# SCH_Scope_1014D_2022-05-10.net
KiCad netlist of a schematic drawn in EasyEDA
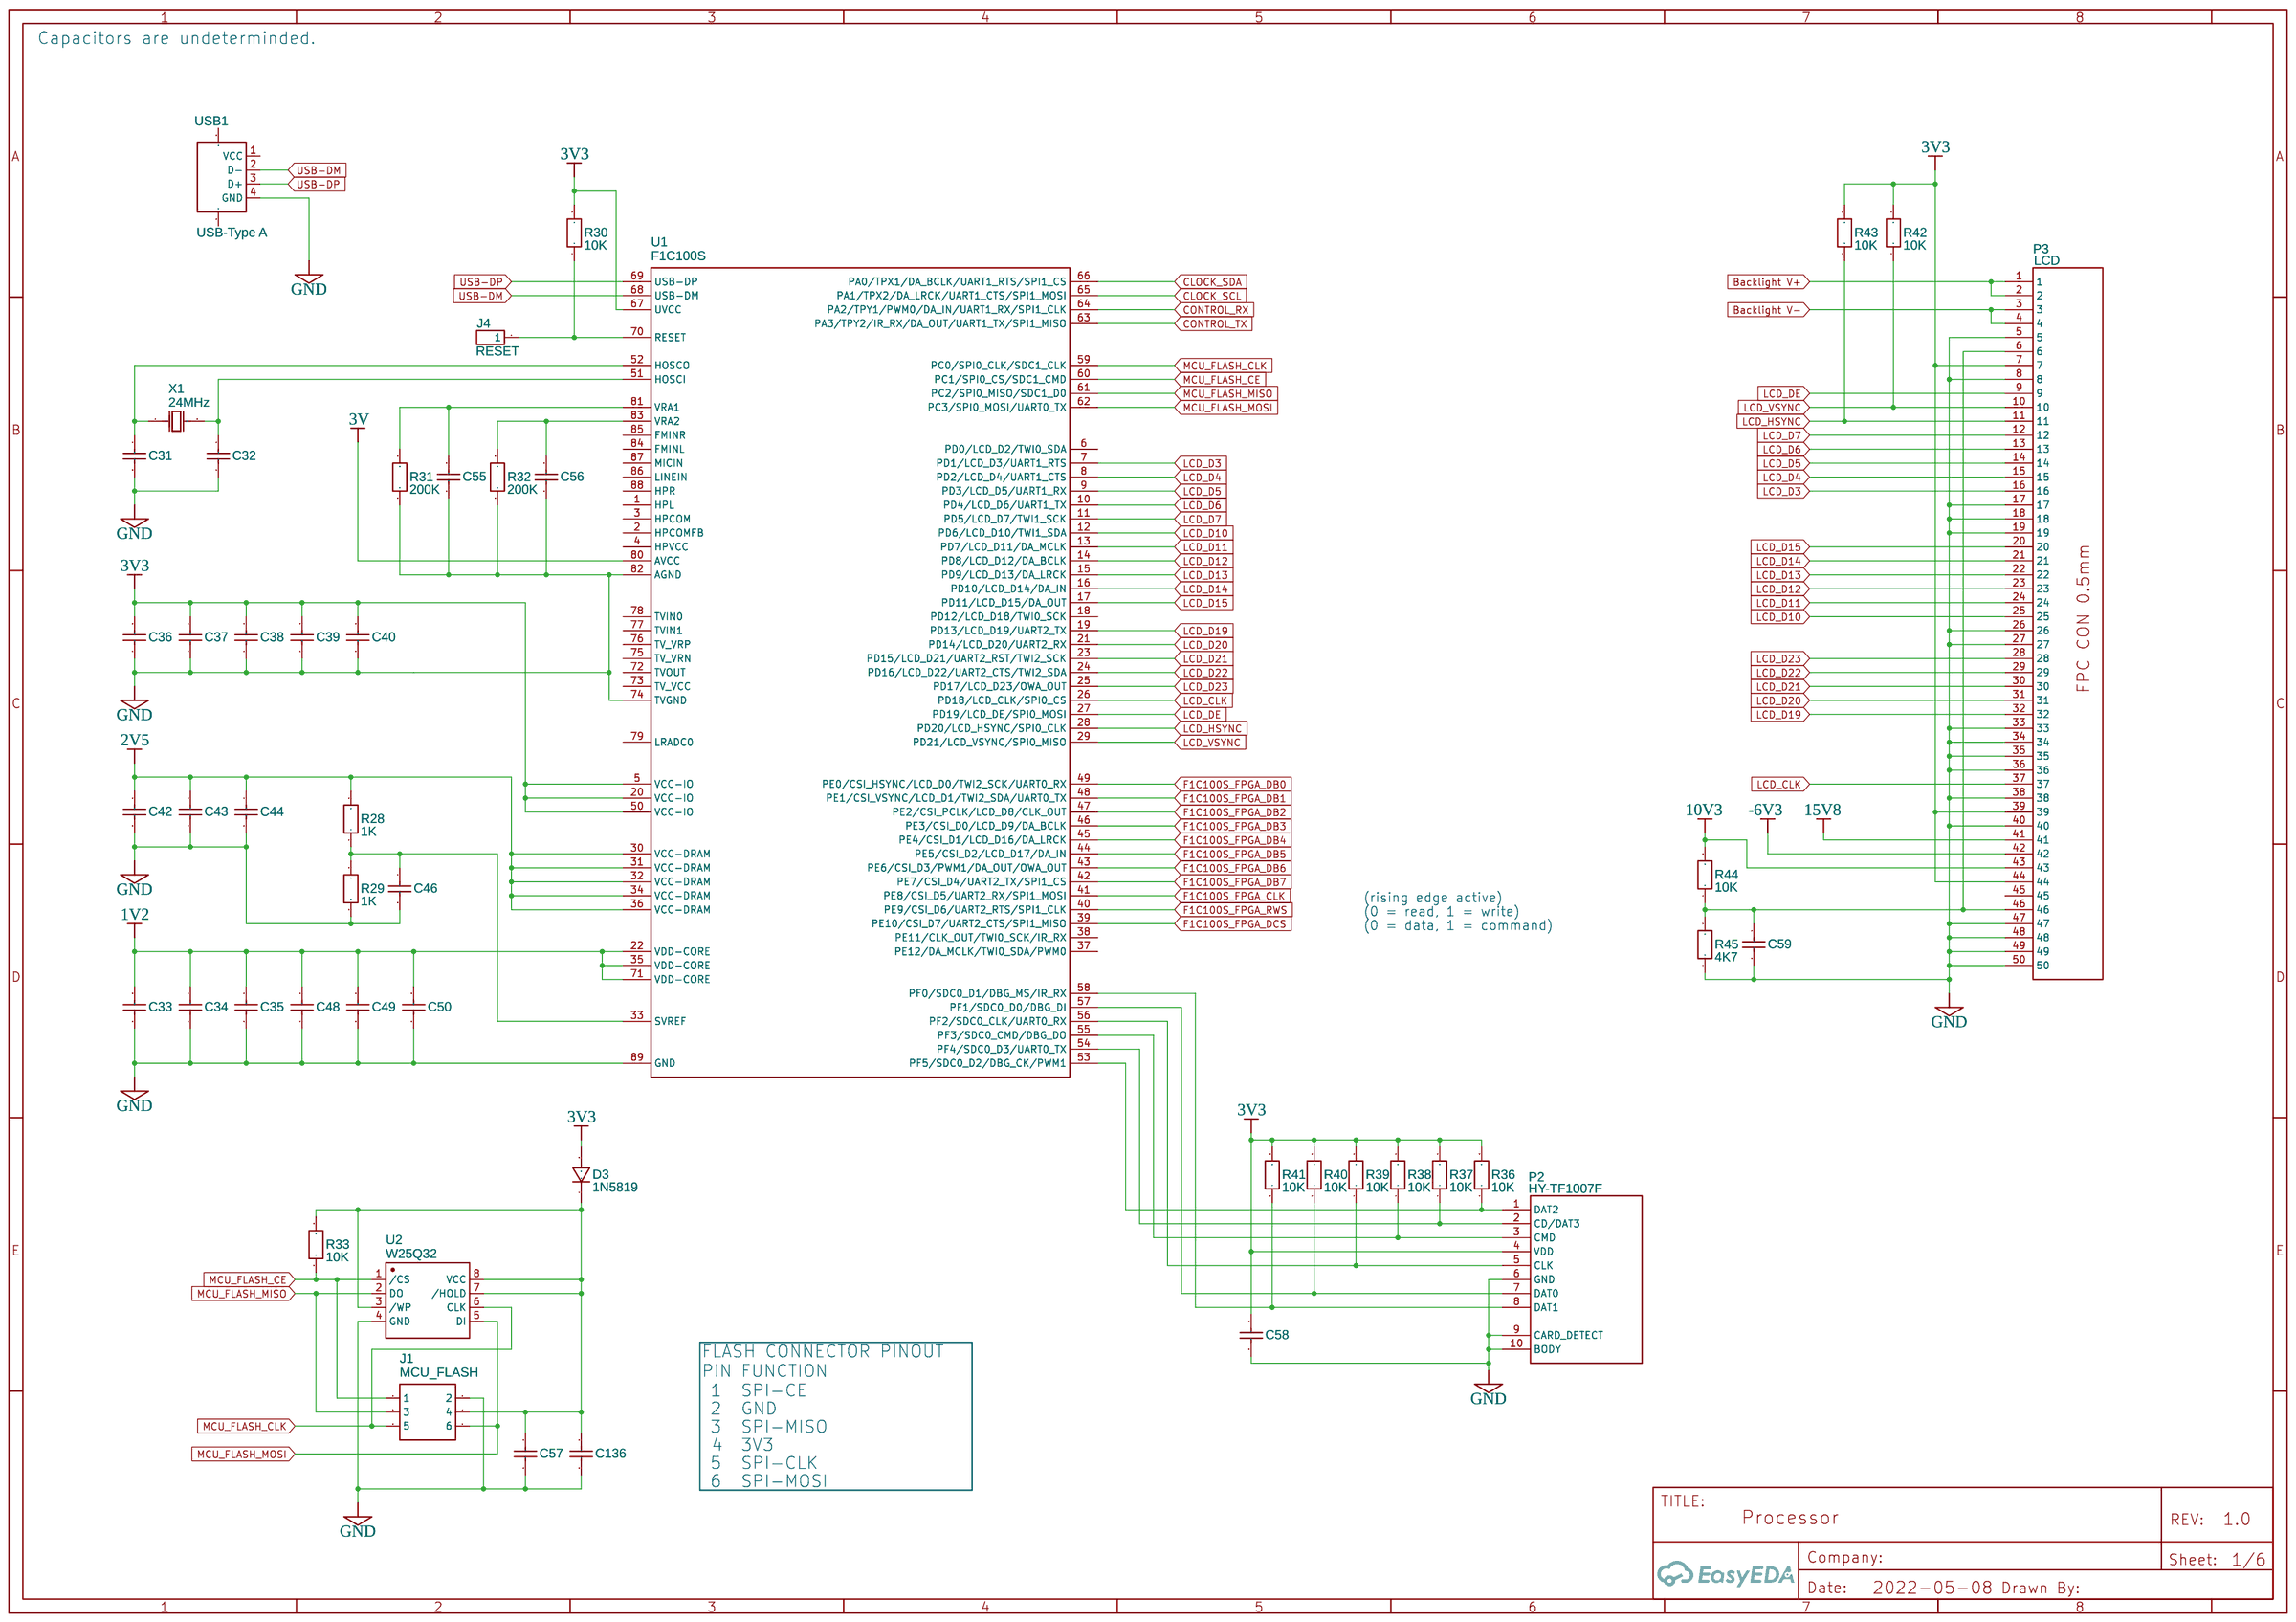
[diagram p0: Scope_1014D_Processor]
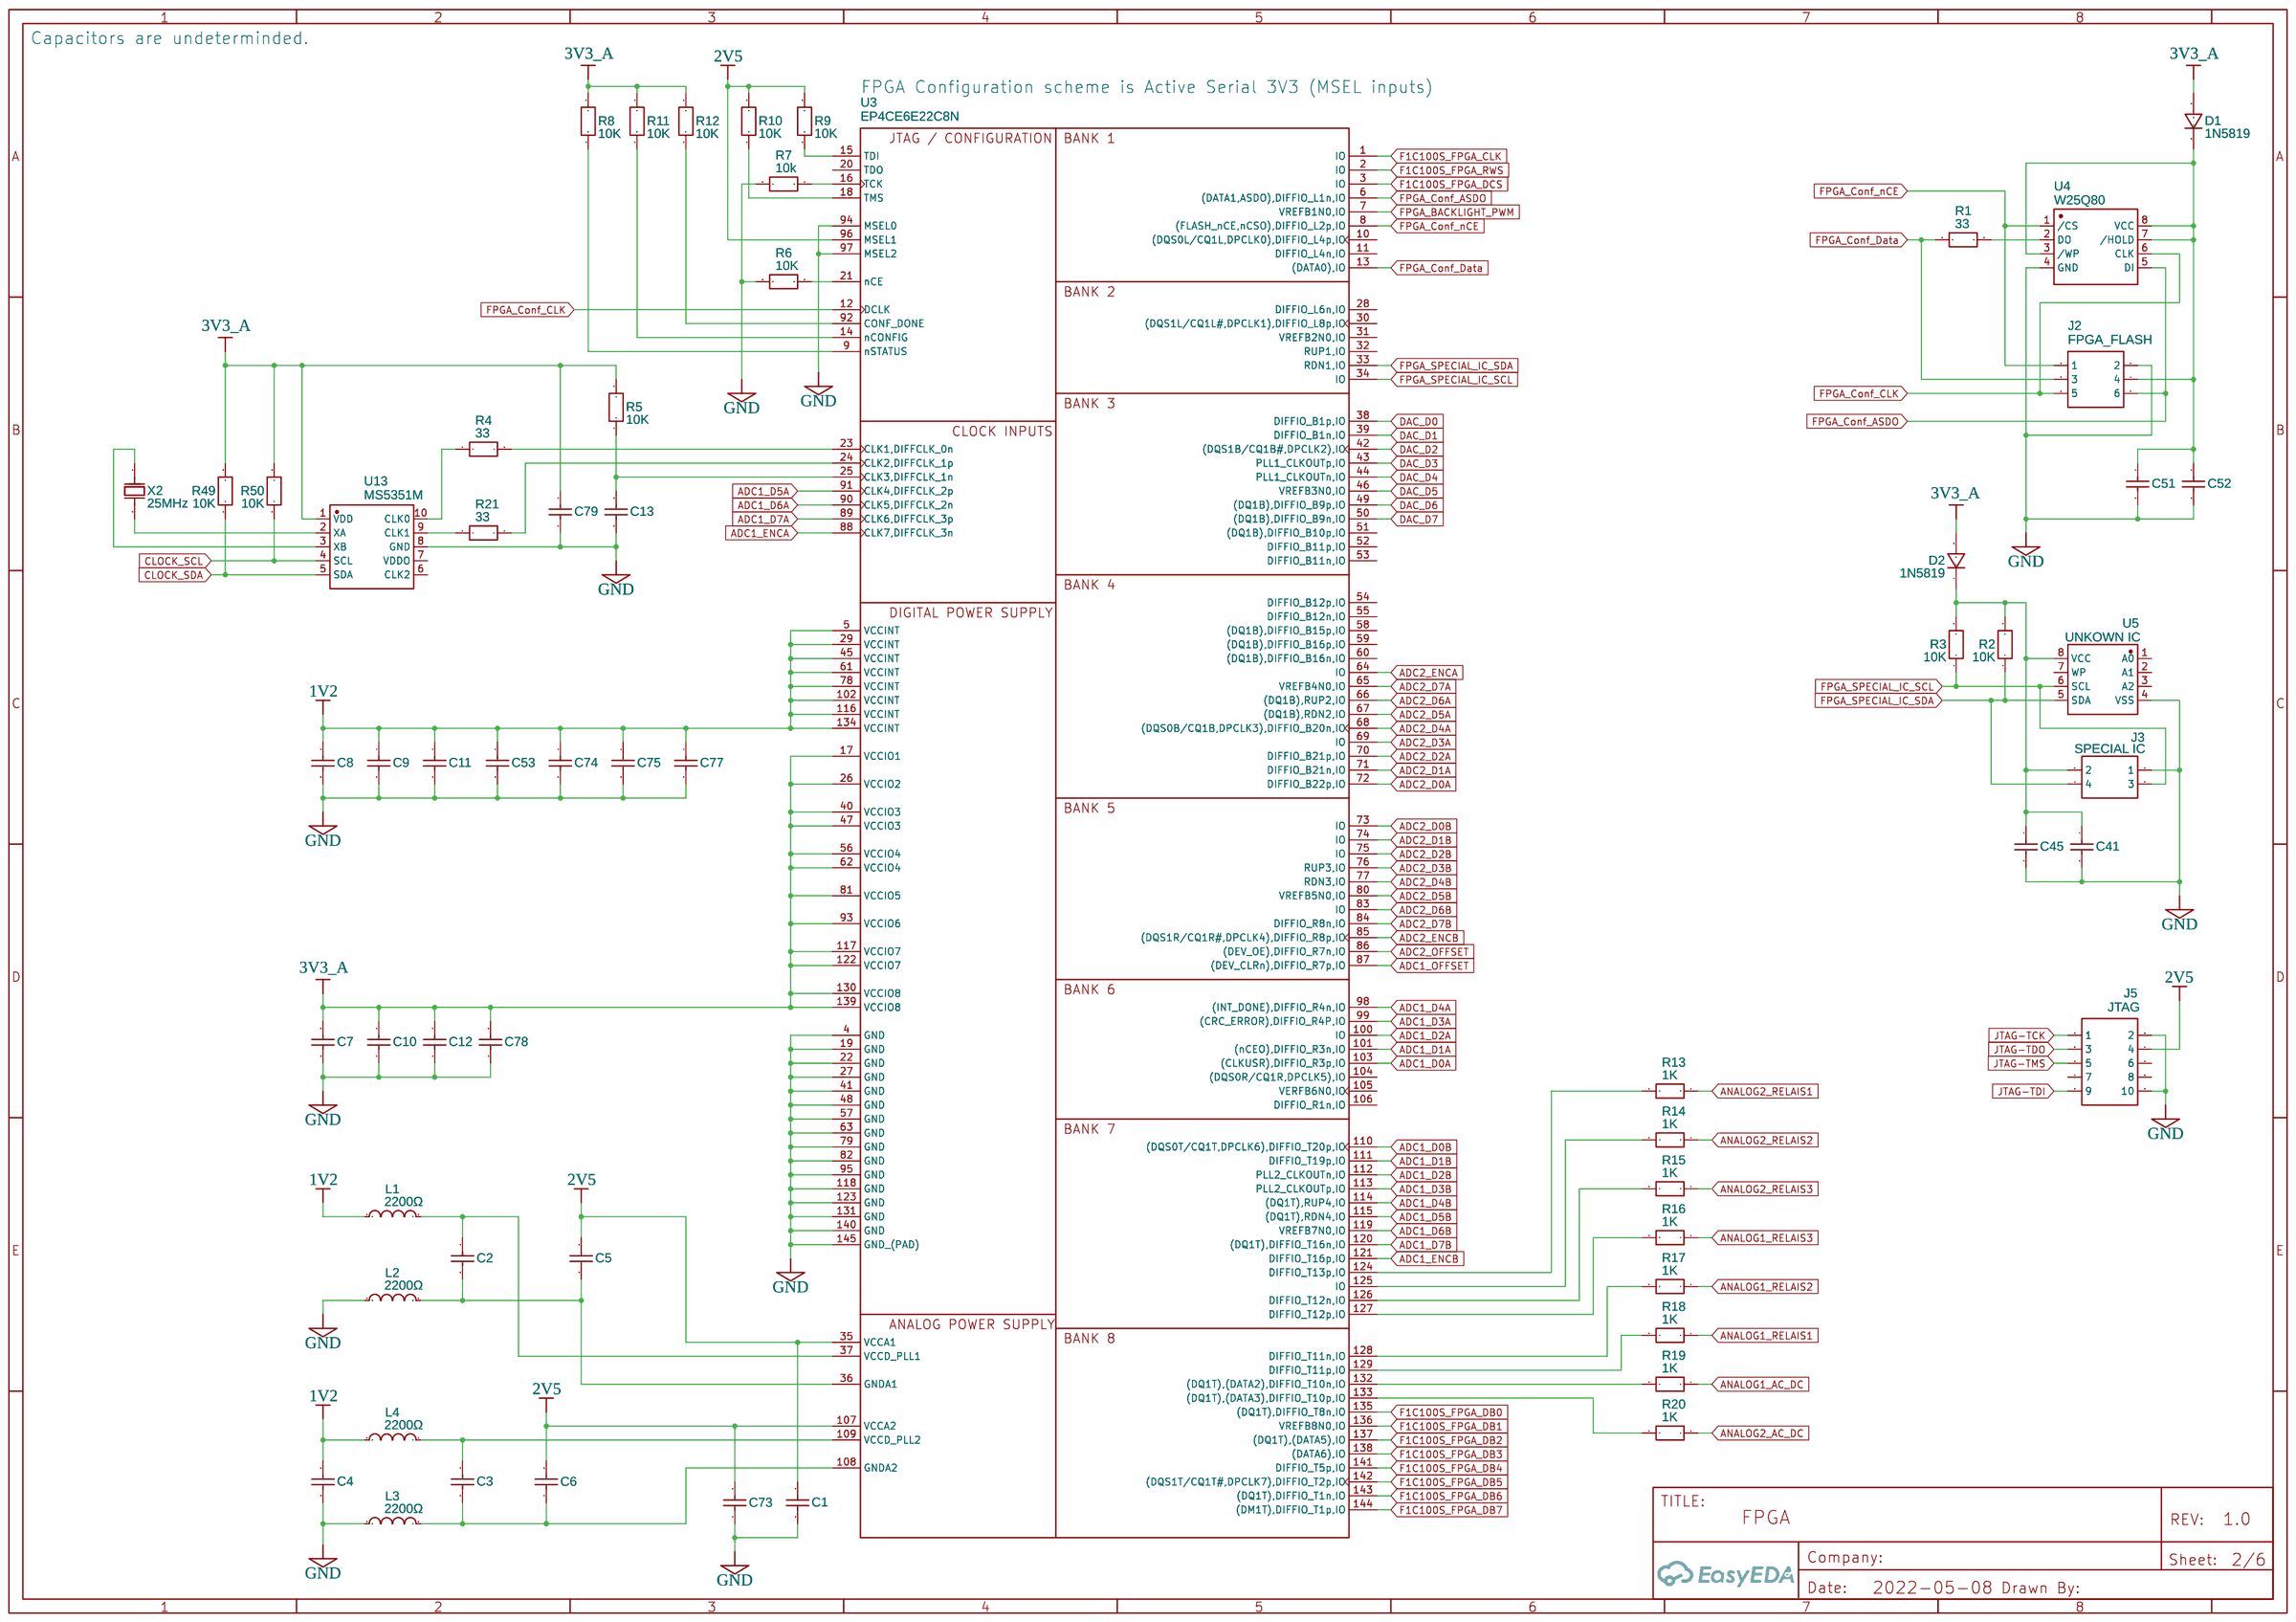
[diagram p1: Scope_1014D_Data_Acquisition]
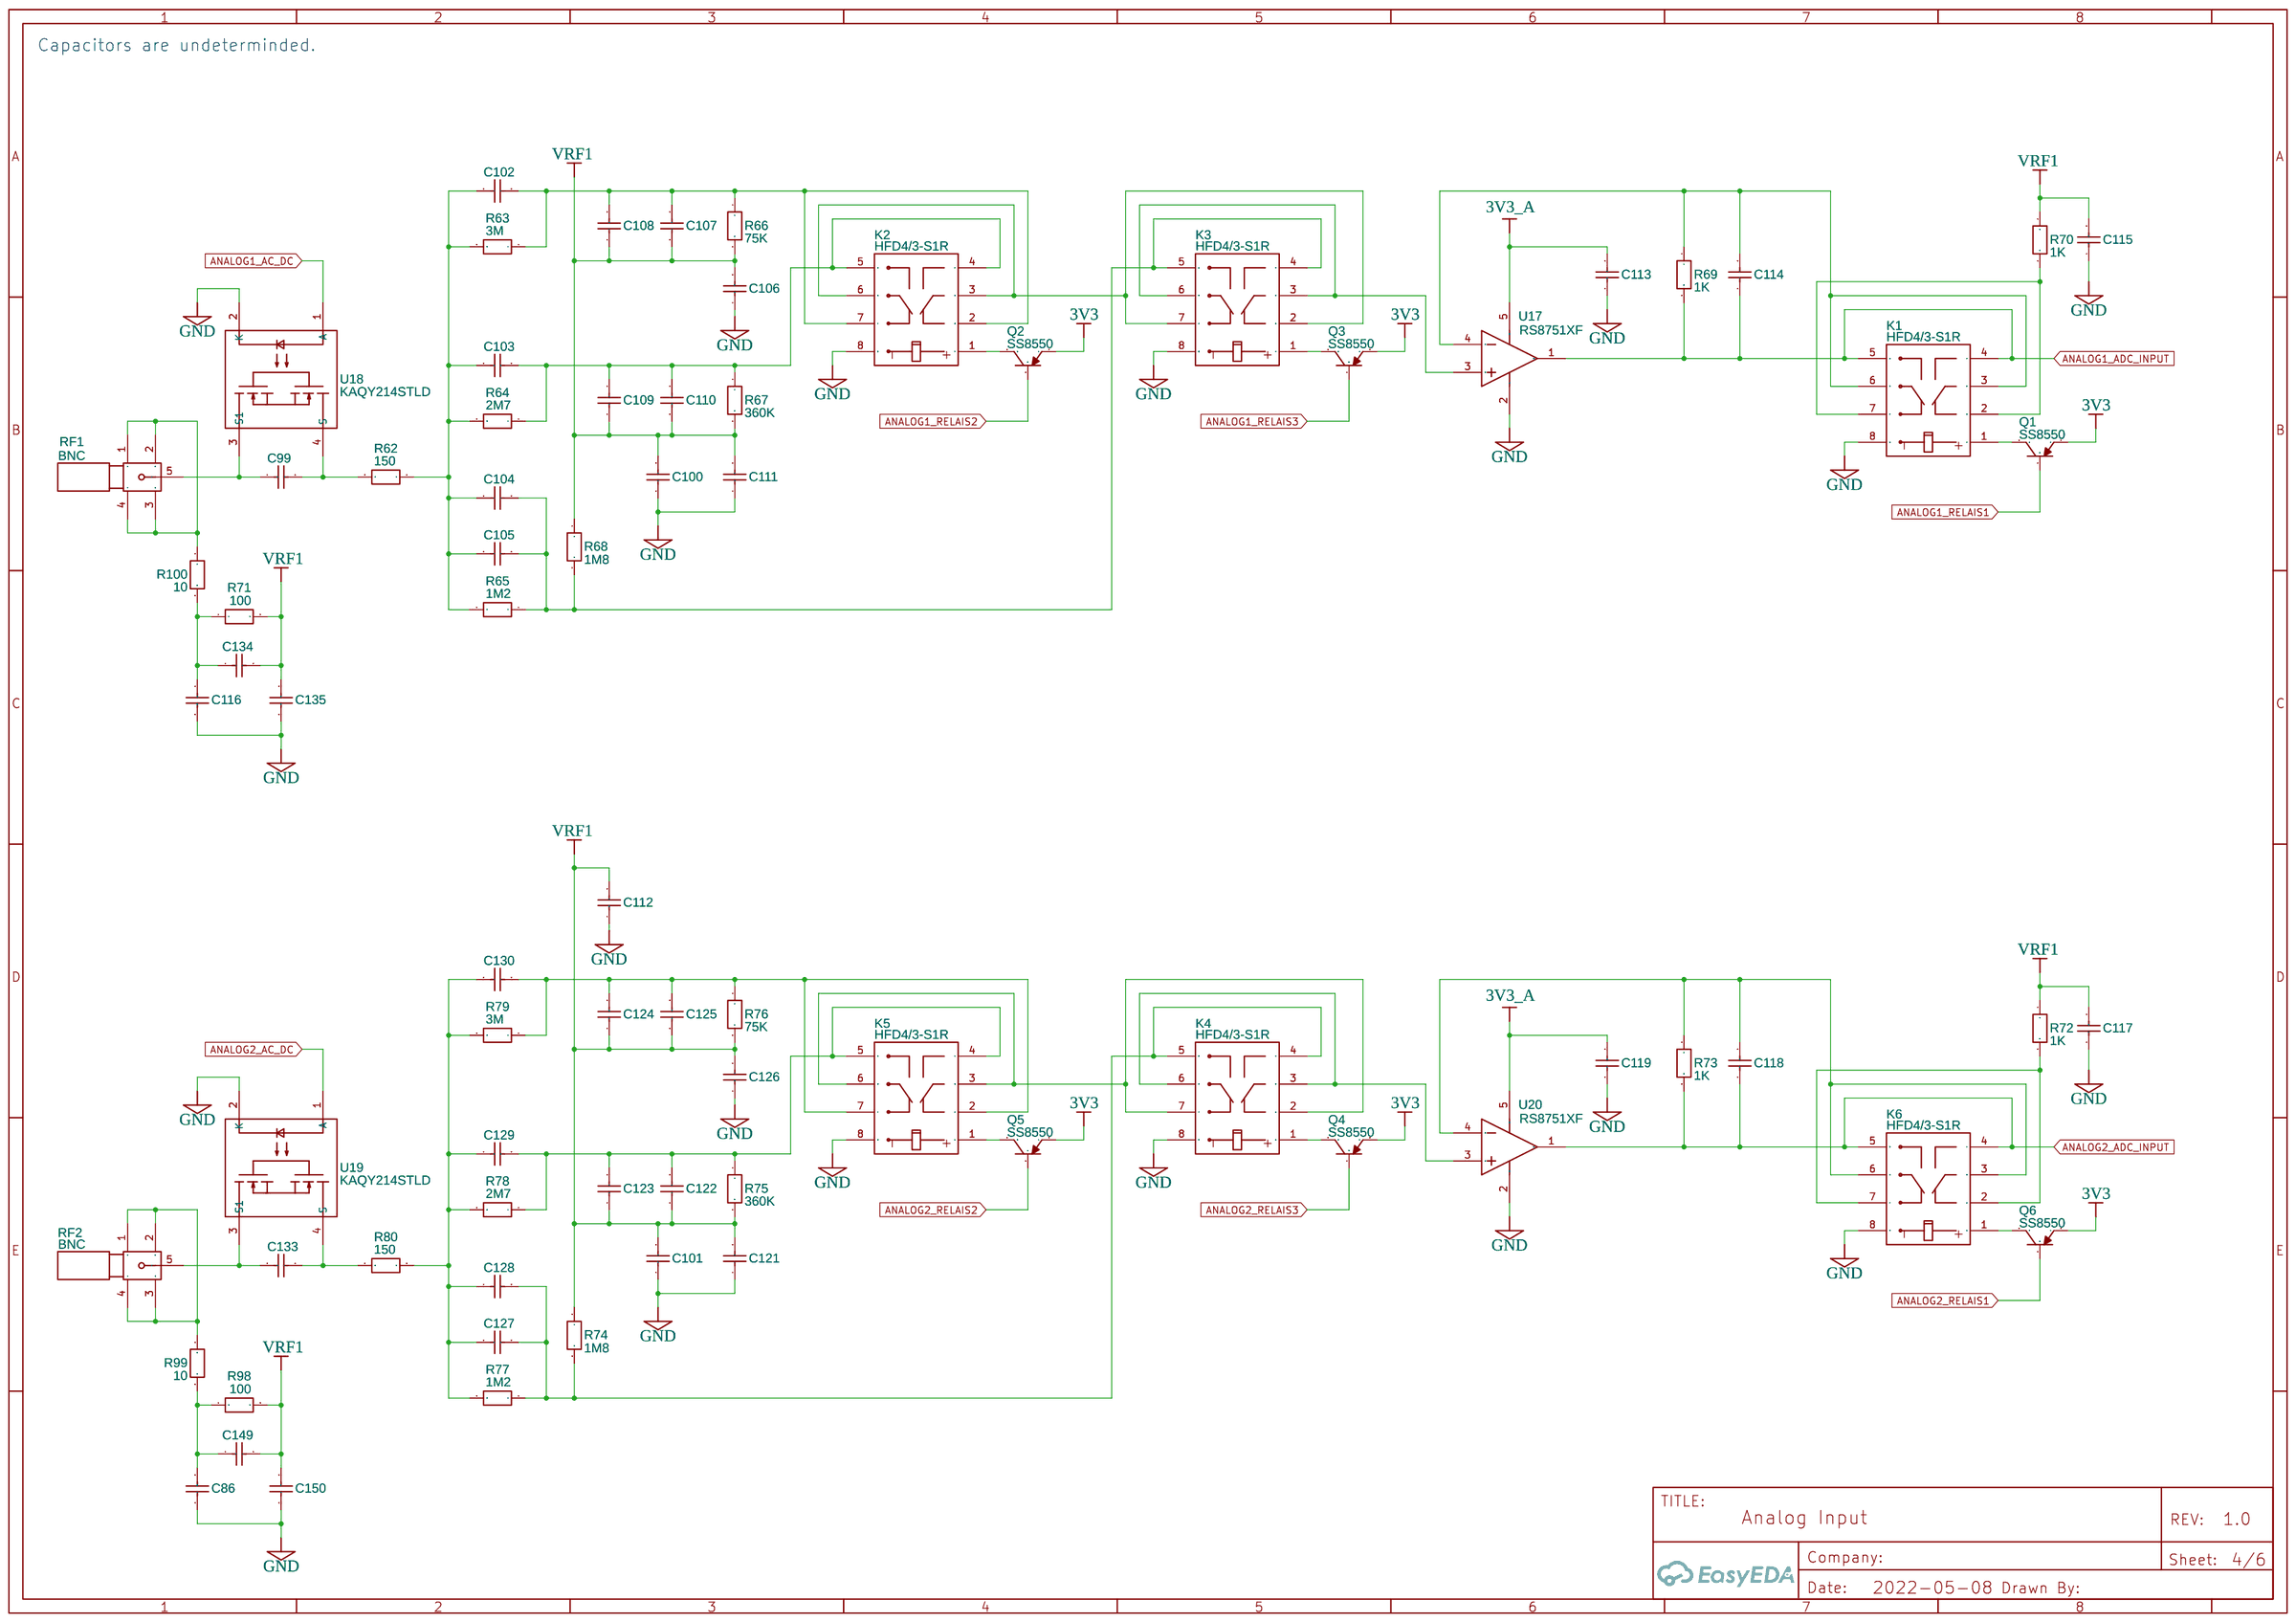
[diagram p2: Scope_1014D_Analog_Input]
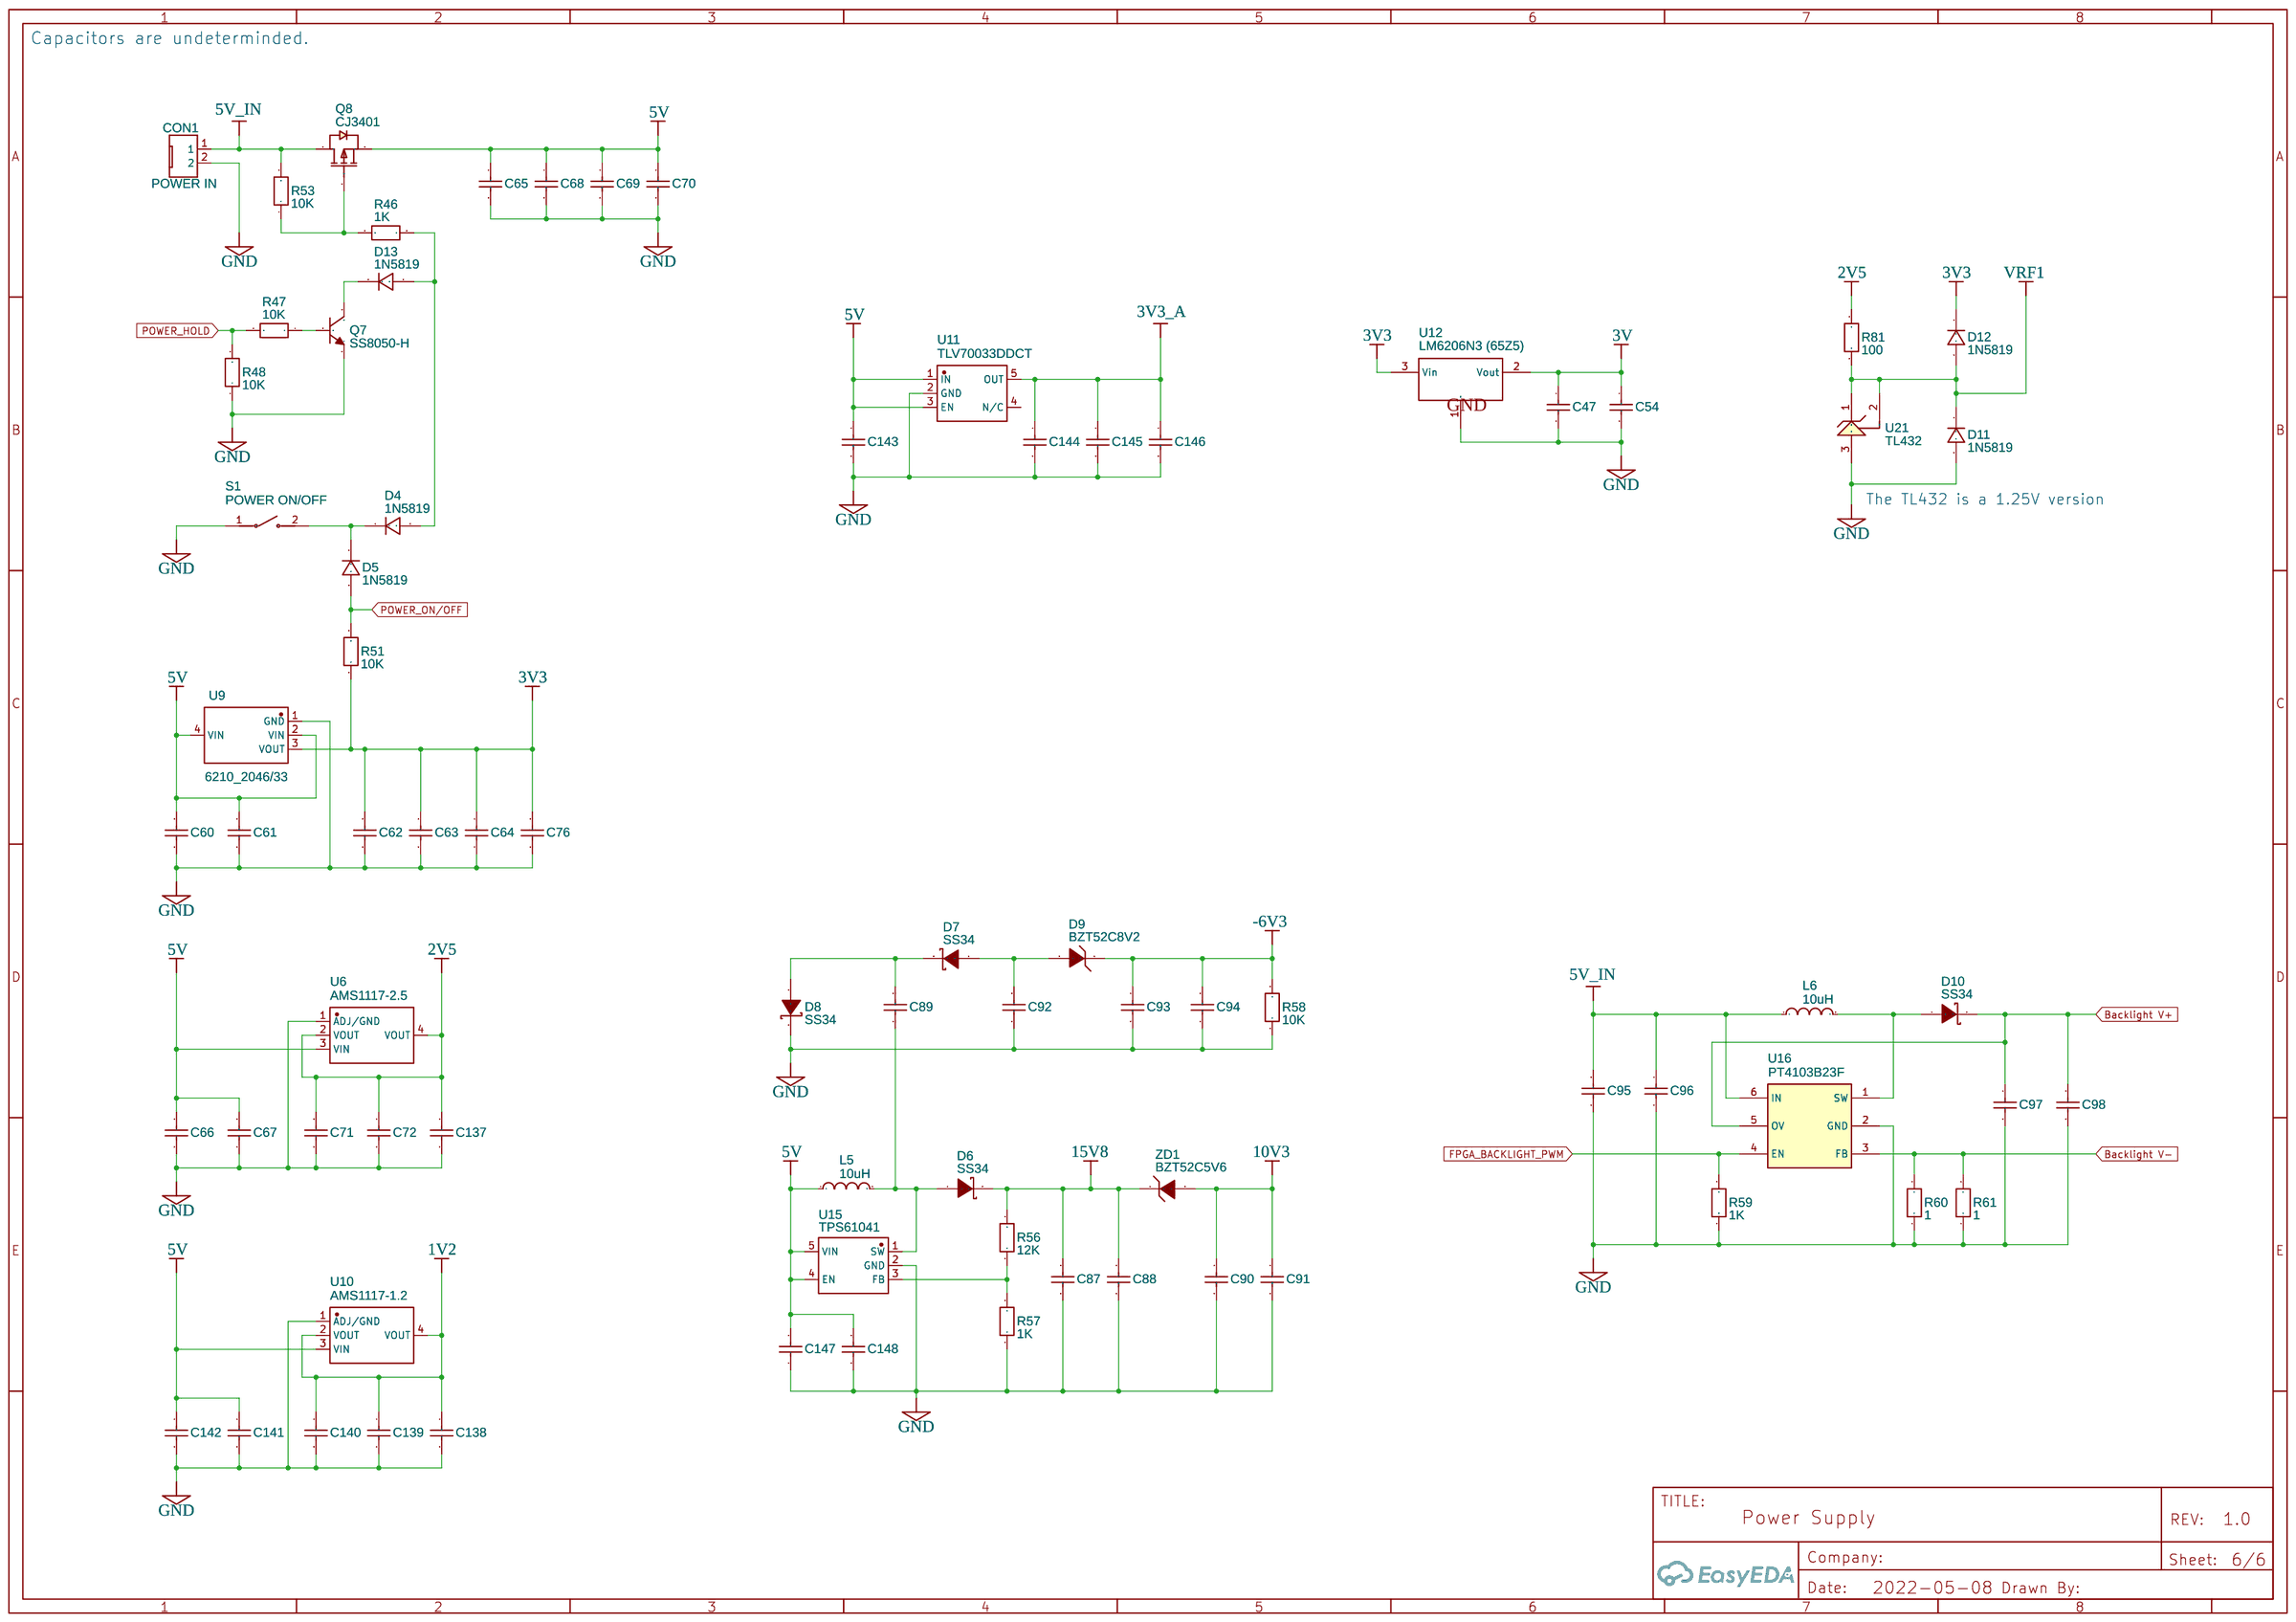
[diagram p3: Scope_1014D_Power_Supply]
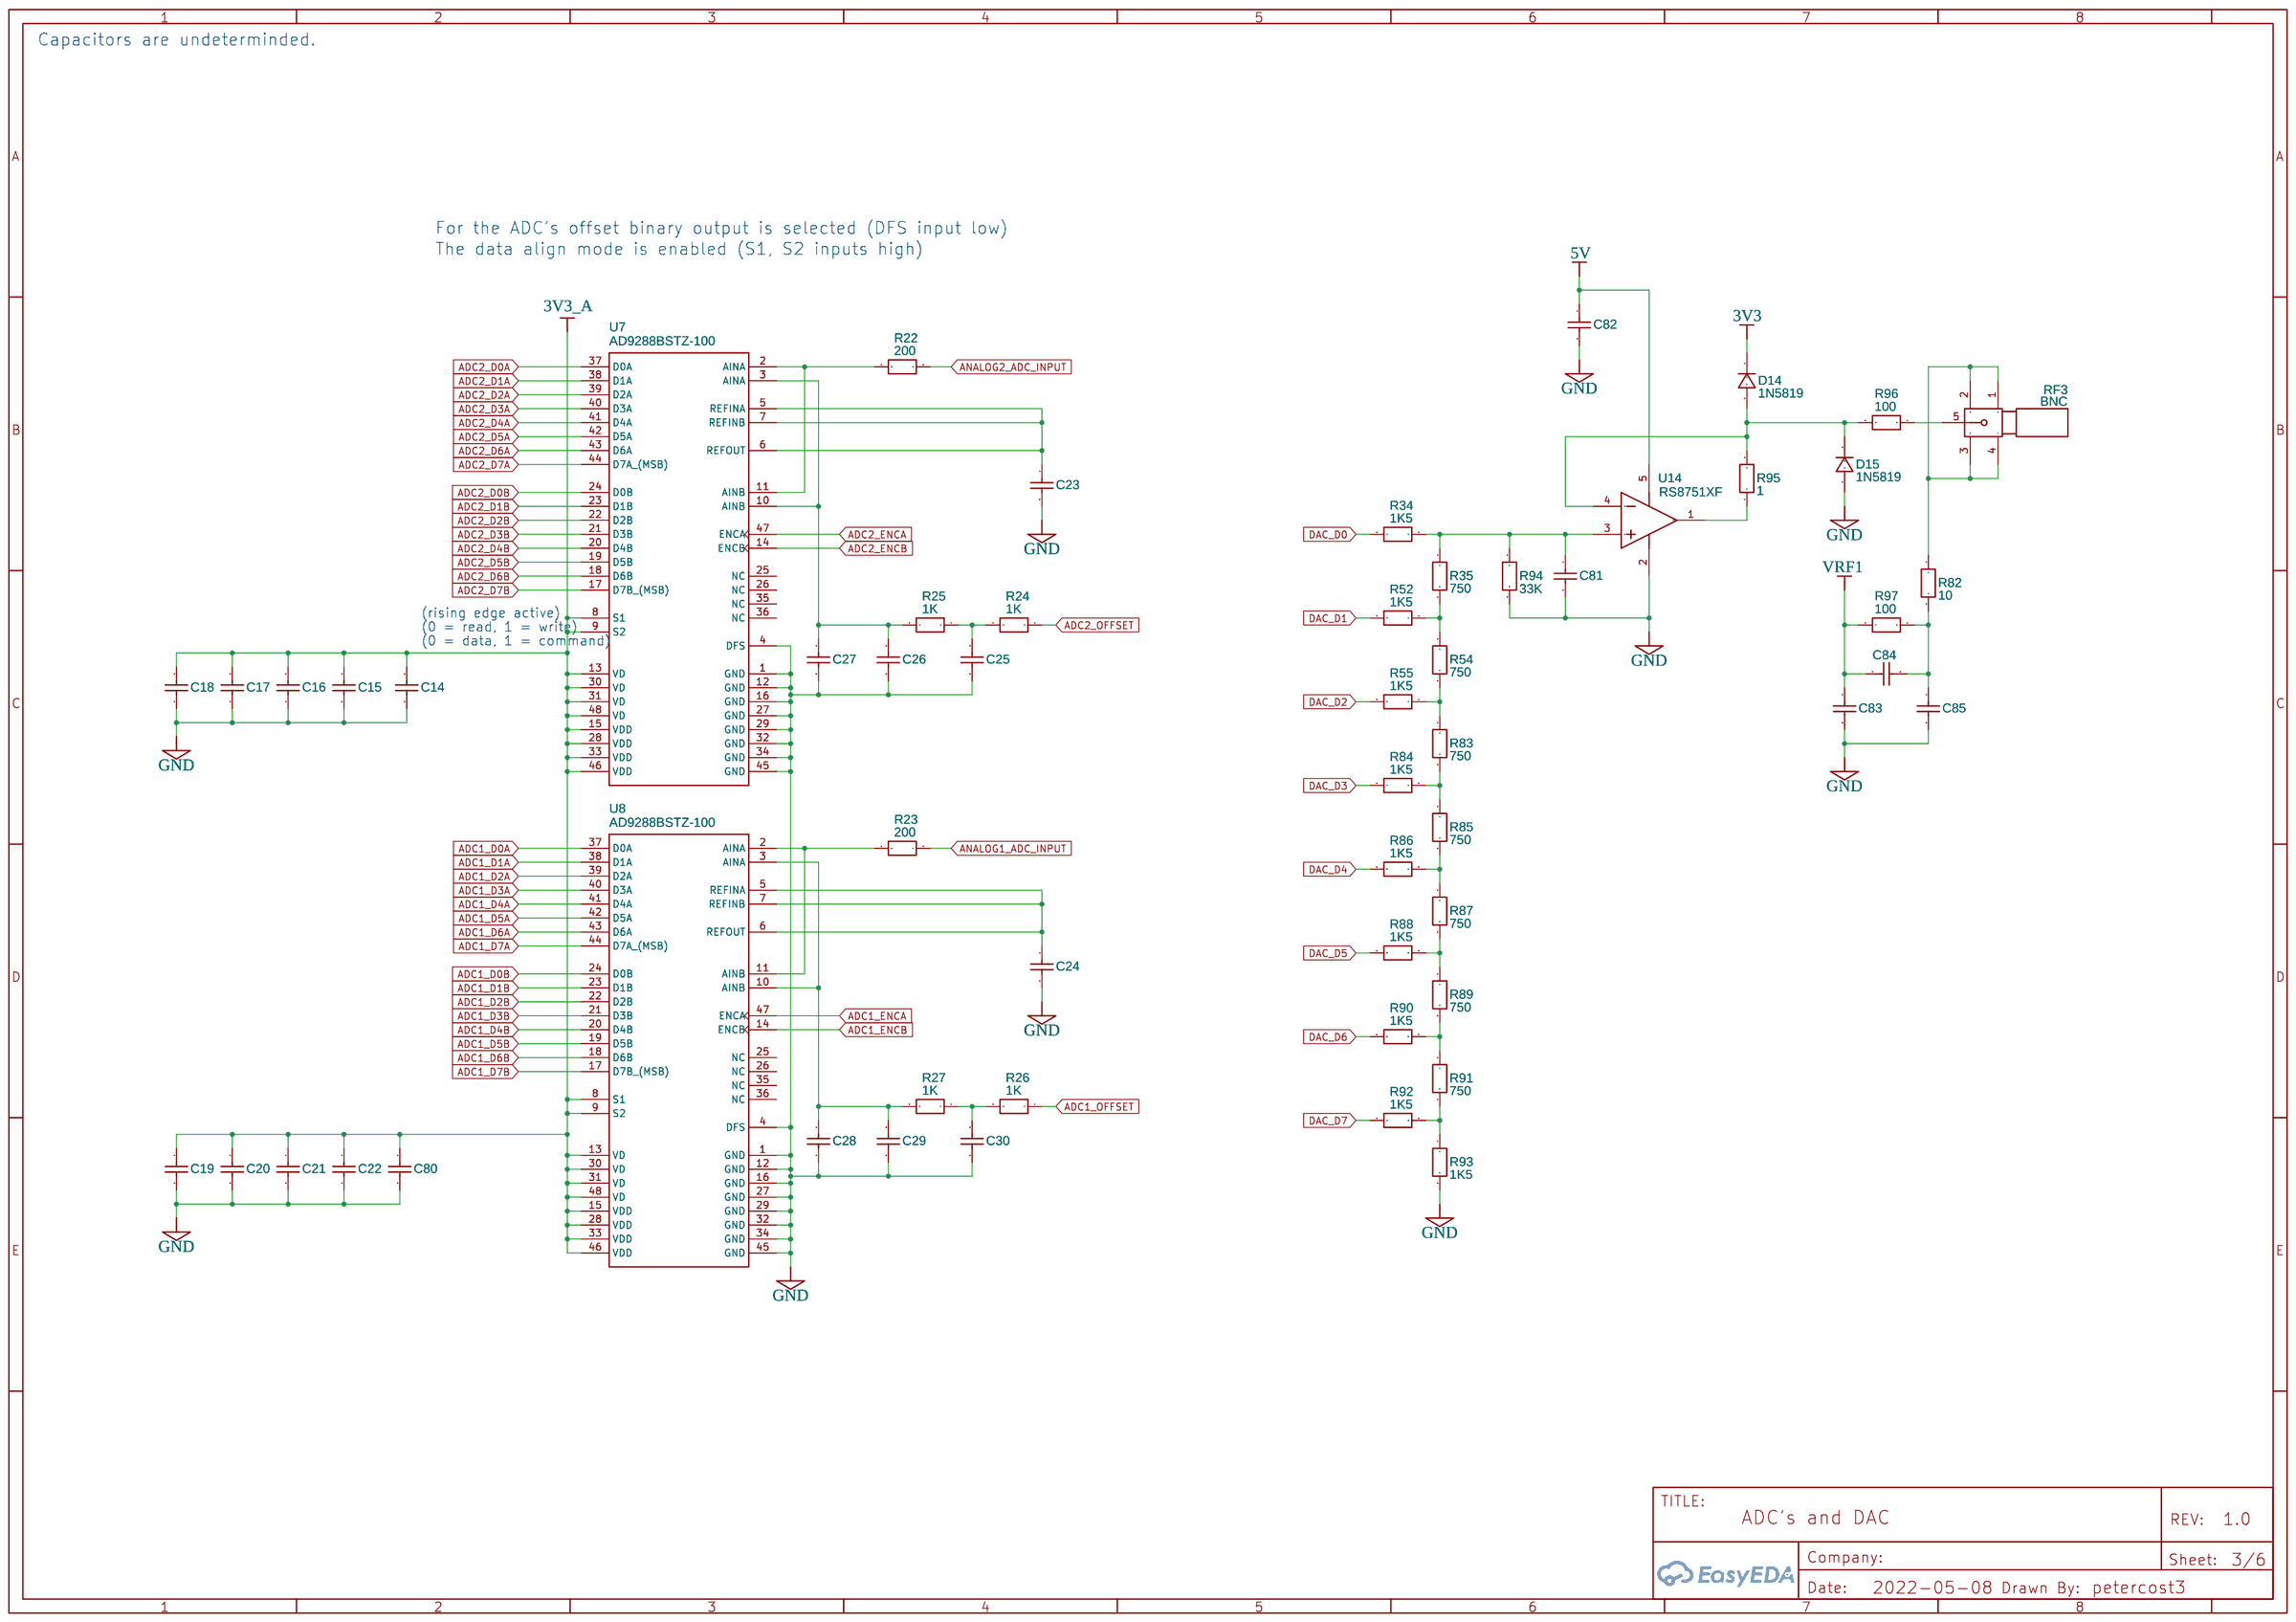
[diagram p4: Scope_1014D_ADC_DAC]
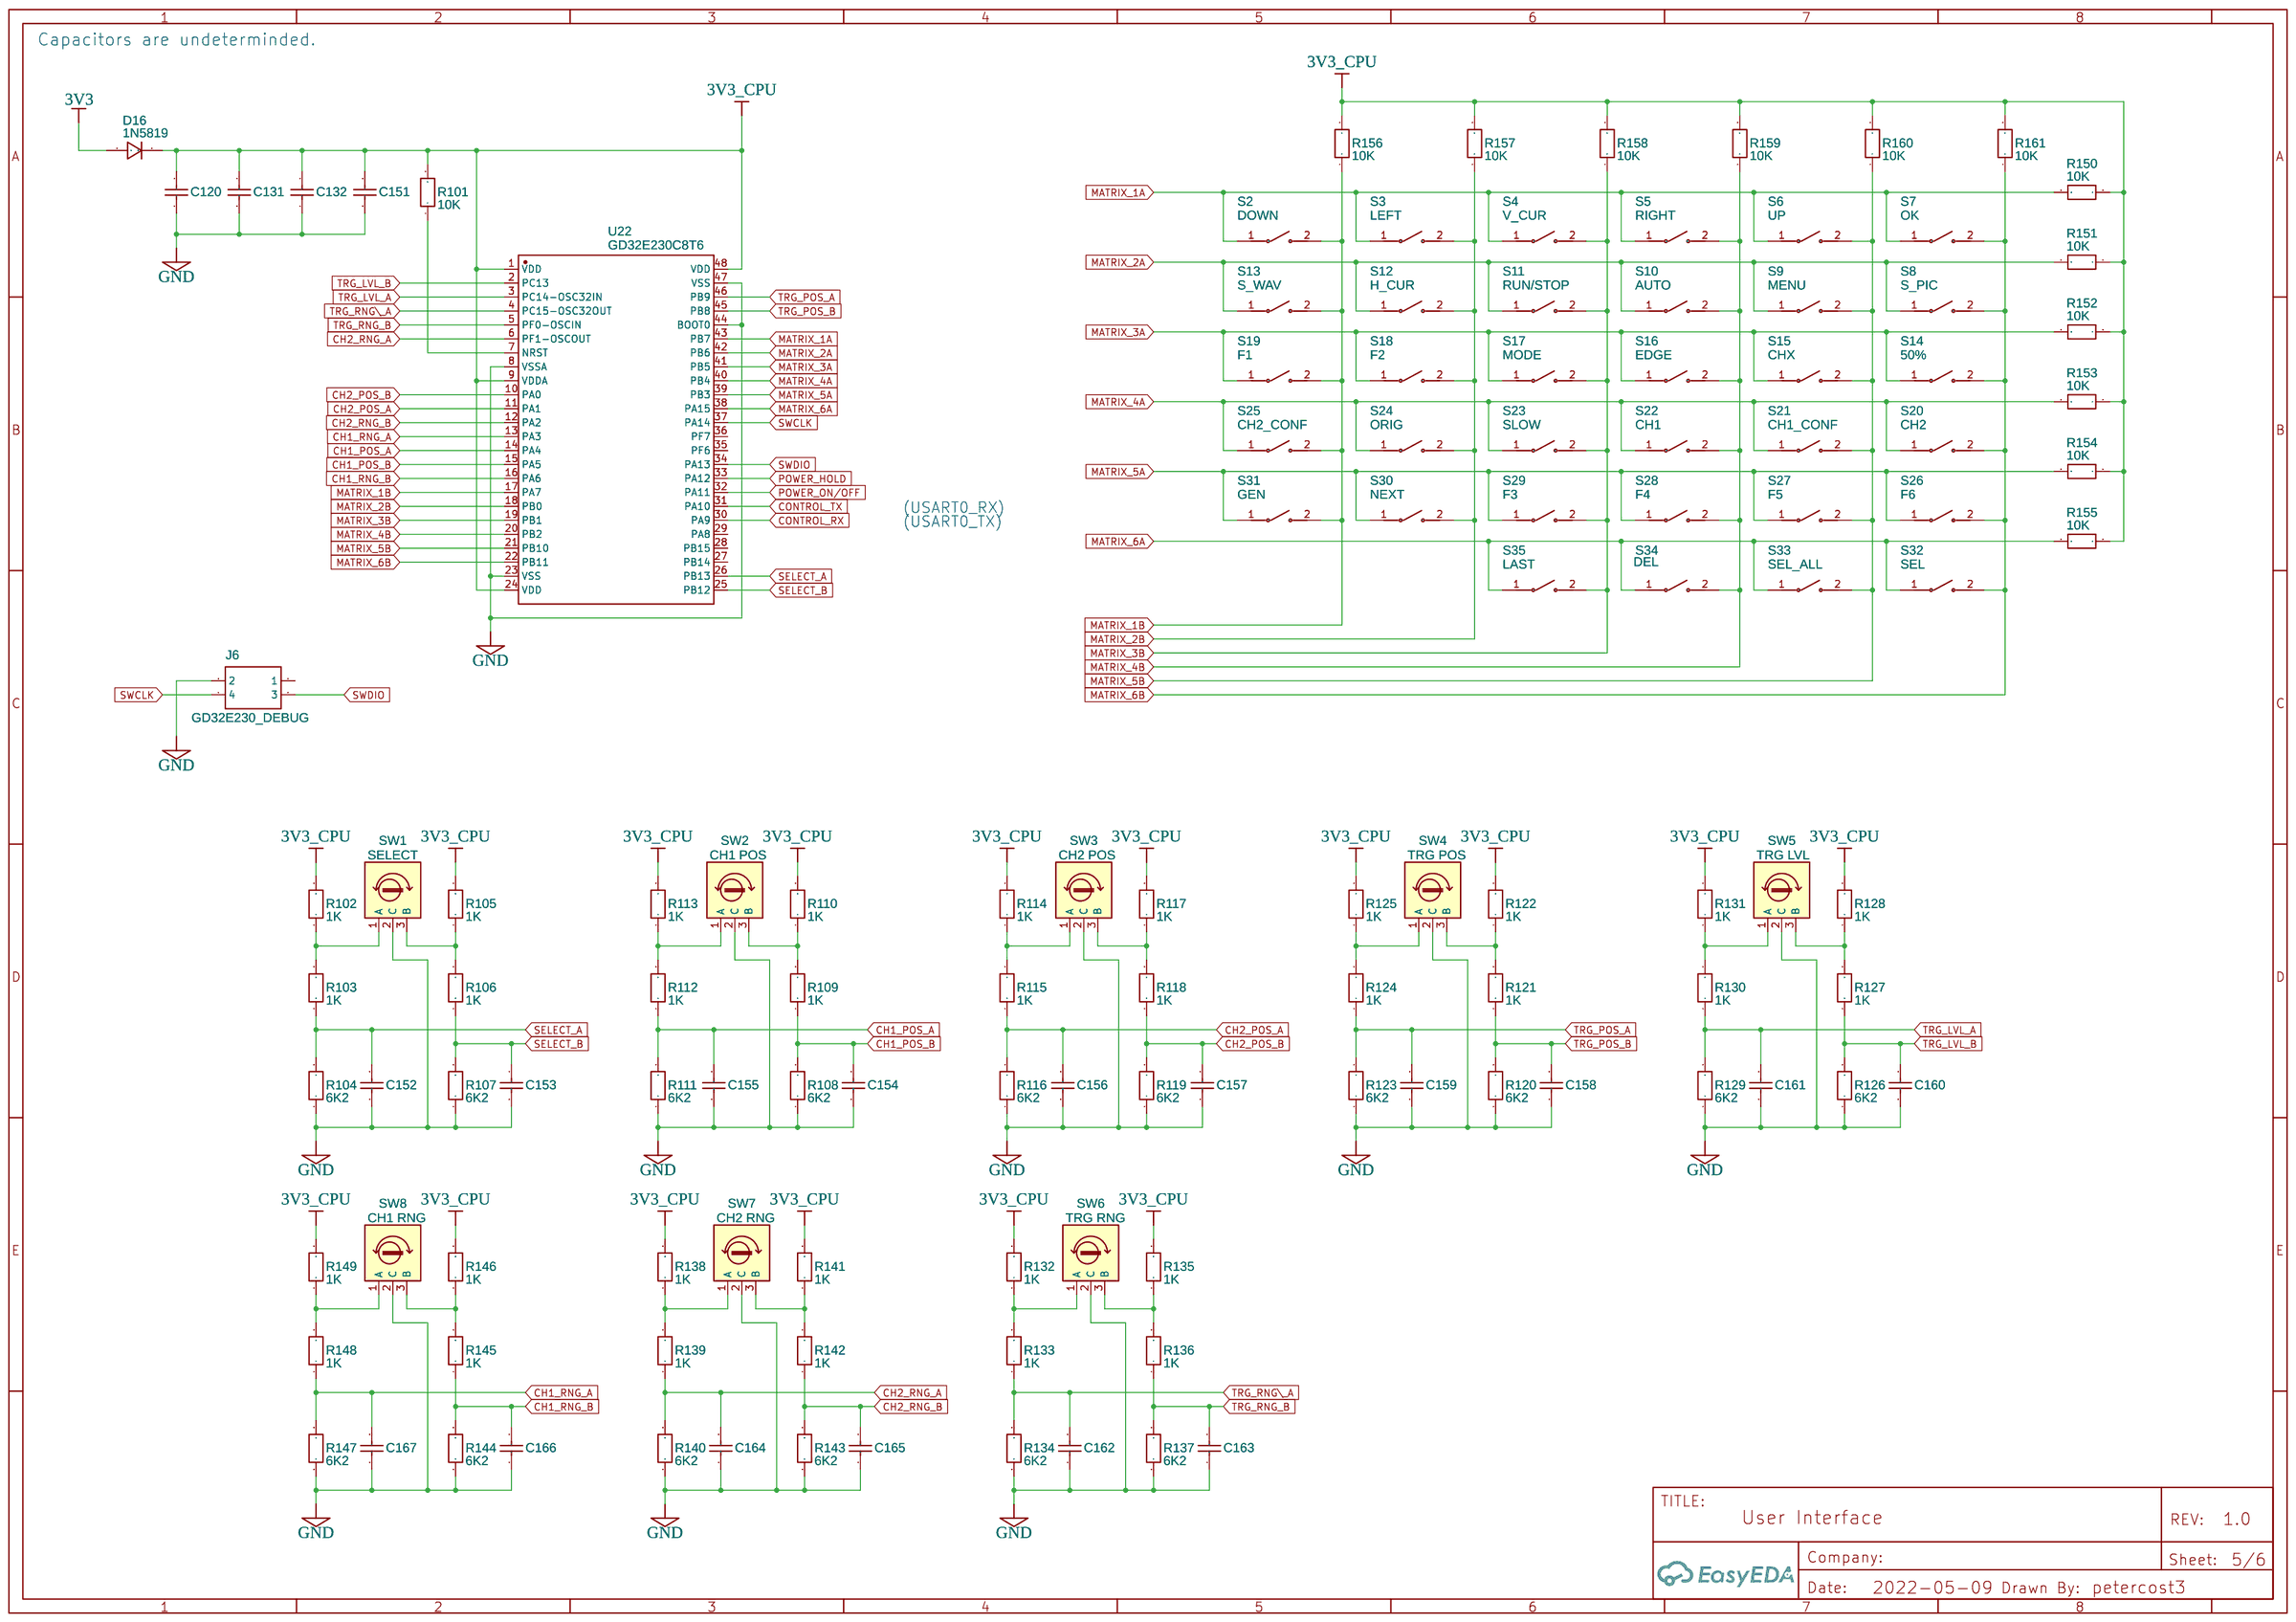
[diagram p5: Scope_1014D_User_Interface]

(export (version "E")
  (design (tool "Eeschema 10.0.6"))
  (components
    (comp (ref "C31")
      (value "1nF")
      (fields
        (field (name "BOM_Manufacturer Part") "GRM31B7U3A471JW31L")
        (field (name "BOM_Supplier Part") "C97936")
      )
      (libsource (lib "") (part "GRM31B7U3A471JW31L"))
    )
    (comp (ref "C32")
      (value "1nF")
      (fields
        (field (name "BOM_Manufacturer Part") "GRM31B7U3A471JW31L")
        (field (name "BOM_Supplier Part") "C97936")
      )
      (libsource (lib "") (part "GRM31B7U3A471JW31L"))
    )
    (comp (ref "C33")
      (value "1nF")
      (fields
        (field (name "BOM_Manufacturer Part") "GRM31B7U3A471JW31L")
        (field (name "BOM_Supplier Part") "C97936")
      )
      (libsource (lib "") (part "GRM31B7U3A471JW31L"))
    )
    (comp (ref "C34")
      (value "1nF")
      (fields
        (field (name "BOM_Manufacturer Part") "GRM31B7U3A471JW31L")
        (field (name "BOM_Supplier Part") "C97936")
      )
      (libsource (lib "") (part "GRM31B7U3A471JW31L"))
    )
    (comp (ref "C35")
      (value "1nF")
      (fields
        (field (name "BOM_Manufacturer Part") "GRM31B7U3A471JW31L")
        (field (name "BOM_Supplier Part") "C97936")
      )
      (libsource (lib "") (part "GRM31B7U3A471JW31L"))
    )
    (comp (ref "C36")
      (value "1nF")
      (fields
        (field (name "BOM_Manufacturer Part") "GRM31B7U3A471JW31L")
        (field (name "BOM_Supplier Part") "C97936")
      )
      (libsource (lib "") (part "GRM31B7U3A471JW31L"))
    )
    (comp (ref "C37")
      (value "1nF")
      (fields
        (field (name "BOM_Manufacturer Part") "GRM31B7U3A471JW31L")
        (field (name "BOM_Supplier Part") "C97936")
      )
      (libsource (lib "") (part "GRM31B7U3A471JW31L"))
    )
    (comp (ref "C38")
      (value "1nF")
      (fields
        (field (name "BOM_Manufacturer Part") "GRM31B7U3A471JW31L")
        (field (name "BOM_Supplier Part") "C97936")
      )
      (libsource (lib "") (part "GRM31B7U3A471JW31L"))
    )
    (comp (ref "C39")
      (value "1nF")
      (fields
        (field (name "BOM_Manufacturer Part") "GRM31B7U3A471JW31L")
        (field (name "BOM_Supplier Part") "C97936")
      )
      (libsource (lib "") (part "GRM31B7U3A471JW31L"))
    )
    (comp (ref "C40")
      (value "1nF")
      (fields
        (field (name "BOM_Manufacturer Part") "GRM31B7U3A471JW31L")
        (field (name "BOM_Supplier Part") "C97936")
      )
      (libsource (lib "") (part "GRM31B7U3A471JW31L"))
    )
    (comp (ref "C42")
      (value "1nF")
      (fields
        (field (name "BOM_Manufacturer Part") "GRM31B7U3A471JW31L")
        (field (name "BOM_Supplier Part") "C97936")
      )
      (libsource (lib "") (part "GRM31B7U3A471JW31L"))
    )
    (comp (ref "C43")
      (value "1nF")
      (fields
        (field (name "BOM_Manufacturer Part") "GRM31B7U3A471JW31L")
        (field (name "BOM_Supplier Part") "C97936")
      )
      (libsource (lib "") (part "GRM31B7U3A471JW31L"))
    )
    (comp (ref "C44")
      (value "1nF")
      (fields
        (field (name "BOM_Manufacturer Part") "GRM31B7U3A471JW31L")
        (field (name "BOM_Supplier Part") "C97936")
      )
      (libsource (lib "") (part "GRM31B7U3A471JW31L"))
    )
    (comp (ref "C46")
      (value "1nF")
      (fields
        (field (name "BOM_Manufacturer Part") "GRM31B7U3A471JW31L")
        (field (name "BOM_Supplier Part") "C97936")
      )
      (libsource (lib "") (part "GRM31B7U3A471JW31L"))
    )
    (comp (ref "C48")
      (value "1nF")
      (fields
        (field (name "BOM_Manufacturer Part") "GRM31B7U3A471JW31L")
        (field (name "BOM_Supplier Part") "C97936")
      )
      (libsource (lib "") (part "GRM31B7U3A471JW31L"))
    )
    (comp (ref "C49")
      (value "1nF")
      (fields
        (field (name "BOM_Manufacturer Part") "GRM31B7U3A471JW31L")
        (field (name "BOM_Supplier Part") "C97936")
      )
      (libsource (lib "") (part "GRM31B7U3A471JW31L"))
    )
    (comp (ref "C50")
      (value "1nF")
      (fields
        (field (name "BOM_Manufacturer Part") "GRM31B7U3A471JW31L")
        (field (name "BOM_Supplier Part") "C97936")
      )
      (libsource (lib "") (part "GRM31B7U3A471JW31L"))
    )
    (comp (ref "C55")
      (value "1nF")
      (fields
        (field (name "BOM_Manufacturer Part") "GRM31B7U3A471JW31L")
        (field (name "BOM_Supplier Part") "C97936")
      )
      (libsource (lib "") (part "GRM31B7U3A471JW31L"))
    )
    (comp (ref "C56")
      (value "1nF")
      (fields
        (field (name "BOM_Manufacturer Part") "GRM31B7U3A471JW31L")
        (field (name "BOM_Supplier Part") "C97936")
      )
      (libsource (lib "") (part "GRM31B7U3A471JW31L"))
    )
    (comp (ref "C57")
      (value "1nF")
      (fields
        (field (name "BOM_Manufacturer Part") "GRM31B7U3A471JW31L")
        (field (name "BOM_Supplier Part") "C97936")
      )
      (libsource (lib "") (part "GRM31B7U3A471JW31L"))
    )
    (comp (ref "C58")
      (value "1nF")
      (fields
        (field (name "BOM_Manufacturer Part") "GRM31B7U3A471JW31L")
        (field (name "BOM_Supplier Part") "C97936")
      )
      (libsource (lib "") (part "GRM31B7U3A471JW31L"))
    )
    (comp (ref "C59")
      (value "1nF")
      (fields
        (field (name "BOM_Manufacturer Part") "GRM31B7U3A471JW31L")
        (field (name "BOM_Supplier Part") "C97936")
      )
      (libsource (lib "") (part "GRM31B7U3A471JW31L"))
    )
    (comp (ref "C136")
      (value "1nF")
      (fields
        (field (name "BOM_Manufacturer Part") "GRM31B7U3A471JW31L")
        (field (name "BOM_Supplier Part") "C97936")
      )
      (libsource (lib "") (part "GRM31B7U3A471JW31L"))
    )
    (comp (ref "D3")
      (value "1N5819")
      (fields (field (name "BOM_Manufacturer Part") "1N4007") (field (name "BOM_Supplier Part") "C106903"))
      (libsource (lib "") (part "1N4007"))
    )
    (comp (ref "J1")
      (value "MCU_FLASH")
      (fields (field (name "BOM_Supplier Part") "C65114"))
      (libsource (lib "") (part "HDR-M-2.54_2x3"))
    )
    (comp (ref "J4")
      (value "RESET")
      (fields (field (name "BOM_Supplier Part") "C81276"))
      (libsource (lib "") (part "HDR-M-2.54_1x1"))
    )
    (comp (ref "P2")
      (value "HY-TF1007F")
      (fields (field (name "BOM_Supplier Part") "undefined"))
      (libsource (lib "") (part "HY-TF1007F"))
    )
    (comp (ref "P3") (value "LCD") (libsource (lib "") (part "FPC CONNECTOR 50P 0.5mm")))
    (comp (ref "R28") (value "1K") (libsource (lib "") (part "R_0805_EU")))
    (comp (ref "R29") (value "1K") (libsource (lib "") (part "R_0805_EU")))
    (comp (ref "R30") (value "10K") (libsource (lib "") (part "R_0805_EU")))
    (comp (ref "R31") (value "200K") (libsource (lib "") (part "R_0805_EU")))
    (comp (ref "R32") (value "200K") (libsource (lib "") (part "R_0805_EU")))
    (comp (ref "R33") (value "10K") (libsource (lib "") (part "R_0805_EU")))
    (comp (ref "R36") (value "10K") (libsource (lib "") (part "R_0805_EU")))
    (comp (ref "R37") (value "10K") (libsource (lib "") (part "R_0805_EU")))
    (comp (ref "R38") (value "10K") (libsource (lib "") (part "R_0805_EU")))
    (comp (ref "R39") (value "10K") (libsource (lib "") (part "R_0805_EU")))
    (comp (ref "R40") (value "10K") (libsource (lib "") (part "R_0805_EU")))
    (comp (ref "R41") (value "10K") (libsource (lib "") (part "R_0805_EU")))
    (comp (ref "R42") (value "10K") (libsource (lib "") (part "R_0805_EU")))
    (comp (ref "R43") (value "10K") (libsource (lib "") (part "R_0805_EU")))
    (comp (ref "R44") (value "10K") (libsource (lib "") (part "R_0805_EU")))
    (comp (ref "R45") (value "4K7") (libsource (lib "") (part "R_0805_EU")))
    (comp (ref "U1") (value "F1C100S") (libsource (lib "") (part "F1C100S")))
    (comp (ref "U2")
      (value "W25Q32")
      (fields
        (field (name "BOM_Manufacturer Part") "W25Q32FVSSIGTR")
        (field (name "BOM_Supplier Part") "C108057")
      )
      (libsource (lib "") (part "W25Q32FVSSIGTR"))
    )
    (comp (ref "USB1")
      (value "USB-Type A")
      (fields (field (name "BOM_Manufacturer Part") "USB-05") (field (name "BOM_Supplier Part") "C112454"))
      (libsource (lib "") (part "USB-Type A_Male"))
    )
    (comp (ref "X1")
      (value "24MHz")
      (fields
        (field (name "BOM_Manufacturer Part") "X503224MSD2GC")
        (field (name "BOM_Supplier Part") "C48304")
      )
      (libsource (lib "") (part "X503224MSD2GC"))
    )
    (comp (ref "C1")
      (value "1nF")
      (fields
        (field (name "BOM_Manufacturer Part") "GRM31B7U3A471JW31L")
        (field (name "BOM_Supplier Part") "C97936")
      )
      (libsource (lib "") (part "GRM31B7U3A471JW31L"))
    )
    (comp (ref "C2")
      (value "1nF")
      (fields
        (field (name "BOM_Manufacturer Part") "GRM31B7U3A471JW31L")
        (field (name "BOM_Supplier Part") "C97936")
      )
      (libsource (lib "") (part "GRM31B7U3A471JW31L"))
    )
    (comp (ref "C3")
      (value "1nF")
      (fields
        (field (name "BOM_Manufacturer Part") "GRM31B7U3A471JW31L")
        (field (name "BOM_Supplier Part") "C97936")
      )
      (libsource (lib "") (part "GRM31B7U3A471JW31L"))
    )
    (comp (ref "C4")
      (value "1nF")
      (fields
        (field (name "BOM_Manufacturer Part") "GRM31B7U3A471JW31L")
        (field (name "BOM_Supplier Part") "C97936")
      )
      (libsource (lib "") (part "GRM31B7U3A471JW31L"))
    )
    (comp (ref "C5")
      (value "1nF")
      (fields
        (field (name "BOM_Manufacturer Part") "GRM31B7U3A471JW31L")
        (field (name "BOM_Supplier Part") "C97936")
      )
      (libsource (lib "") (part "GRM31B7U3A471JW31L"))
    )
    (comp (ref "C6")
      (value "1nF")
      (fields
        (field (name "BOM_Manufacturer Part") "GRM31B7U3A471JW31L")
        (field (name "BOM_Supplier Part") "C97936")
      )
      (libsource (lib "") (part "GRM31B7U3A471JW31L_1"))
    )
    (comp (ref "C7")
      (value "1nF")
      (fields
        (field (name "BOM_Manufacturer Part") "GRM31B7U3A471JW31L")
        (field (name "BOM_Supplier Part") "C97936")
      )
      (libsource (lib "") (part "GRM31B7U3A471JW31L"))
    )
    (comp (ref "C8")
      (value "1nF")
      (fields
        (field (name "BOM_Manufacturer Part") "GRM31B7U3A471JW31L")
        (field (name "BOM_Supplier Part") "C97936")
      )
      (libsource (lib "") (part "GRM31B7U3A471JW31L"))
    )
    (comp (ref "C9")
      (value "1nF")
      (fields
        (field (name "BOM_Manufacturer Part") "GRM31B7U3A471JW31L")
        (field (name "BOM_Supplier Part") "C97936")
      )
      (libsource (lib "") (part "GRM31B7U3A471JW31L"))
    )
    (comp (ref "C10")
      (value "1nF")
      (fields
        (field (name "BOM_Manufacturer Part") "GRM31B7U3A471JW31L")
        (field (name "BOM_Supplier Part") "C97936")
      )
      (libsource (lib "") (part "GRM31B7U3A471JW31L"))
    )
    (comp (ref "C11")
      (value "1nF")
      (fields
        (field (name "BOM_Manufacturer Part") "GRM31B7U3A471JW31L")
        (field (name "BOM_Supplier Part") "C97936")
      )
      (libsource (lib "") (part "GRM31B7U3A471JW31L"))
    )
    (comp (ref "C12")
      (value "1nF")
      (fields
        (field (name "BOM_Manufacturer Part") "GRM31B7U3A471JW31L")
        (field (name "BOM_Supplier Part") "C97936")
      )
      (libsource (lib "") (part "GRM31B7U3A471JW31L"))
    )
    (comp (ref "C13")
      (value "1nF")
      (fields
        (field (name "BOM_Manufacturer Part") "GRM31B7U3A471JW31L")
        (field (name "BOM_Supplier Part") "C97936")
      )
      (libsource (lib "") (part "GRM31B7U3A471JW31L"))
    )
    (comp (ref "C41")
      (value "1nF")
      (fields
        (field (name "BOM_Manufacturer Part") "GRM31B7U3A471JW31L")
        (field (name "BOM_Supplier Part") "C97936")
      )
      (libsource (lib "") (part "GRM31B7U3A471JW31L"))
    )
    (comp (ref "C45")
      (value "1nF")
      (fields
        (field (name "BOM_Manufacturer Part") "GRM31B7U3A471JW31L")
        (field (name "BOM_Supplier Part") "C97936")
      )
      (libsource (lib "") (part "GRM31B7U3A471JW31L"))
    )
    (comp (ref "C51")
      (value "1nF")
      (fields
        (field (name "BOM_Manufacturer Part") "GRM31B7U3A471JW31L")
        (field (name "BOM_Supplier Part") "C97936")
      )
      (libsource (lib "") (part "GRM31B7U3A471JW31L"))
    )
    (comp (ref "C52")
      (value "1nF")
      (fields
        (field (name "BOM_Manufacturer Part") "GRM31B7U3A471JW31L")
        (field (name "BOM_Supplier Part") "C97936")
      )
      (libsource (lib "") (part "GRM31B7U3A471JW31L"))
    )
    (comp (ref "C53")
      (value "1nF")
      (fields
        (field (name "BOM_Manufacturer Part") "GRM31B7U3A471JW31L")
        (field (name "BOM_Supplier Part") "C97936")
      )
      (libsource (lib "") (part "GRM31B7U3A471JW31L"))
    )
    (comp (ref "C73")
      (value "1nF")
      (fields
        (field (name "BOM_Manufacturer Part") "GRM31B7U3A471JW31L")
        (field (name "BOM_Supplier Part") "C97936")
      )
      (libsource (lib "") (part "GRM31B7U3A471JW31L_1"))
    )
    (comp (ref "C74")
      (value "1nF")
      (fields
        (field (name "BOM_Manufacturer Part") "GRM31B7U3A471JW31L")
        (field (name "BOM_Supplier Part") "C97936")
      )
      (libsource (lib "") (part "GRM31B7U3A471JW31L"))
    )
    (comp (ref "C75")
      (value "1nF")
      (fields
        (field (name "BOM_Manufacturer Part") "GRM31B7U3A471JW31L")
        (field (name "BOM_Supplier Part") "C97936")
      )
      (libsource (lib "") (part "GRM31B7U3A471JW31L"))
    )
    (comp (ref "C77")
      (value "1nF")
      (fields
        (field (name "BOM_Manufacturer Part") "GRM31B7U3A471JW31L")
        (field (name "BOM_Supplier Part") "C97936")
      )
      (libsource (lib "") (part "GRM31B7U3A471JW31L"))
    )
    (comp (ref "C78")
      (value "1nF")
      (fields
        (field (name "BOM_Manufacturer Part") "GRM31B7U3A471JW31L")
        (field (name "BOM_Supplier Part") "C97936")
      )
      (libsource (lib "") (part "GRM31B7U3A471JW31L"))
    )
    (comp (ref "C79")
      (value "1nF")
      (fields
        (field (name "BOM_Manufacturer Part") "GRM31B7U3A471JW31L")
        (field (name "BOM_Supplier Part") "C97936")
      )
      (libsource (lib "") (part "GRM31B7U3A471JW31L"))
    )
    (comp (ref "D1")
      (value "1N5819")
      (fields (field (name "BOM_Manufacturer Part") "1N4007") (field (name "BOM_Supplier Part") "C106903"))
      (libsource (lib "") (part "1N4007_1"))
    )
    (comp (ref "D2")
      (value "1N5819")
      (fields (field (name "BOM_Manufacturer Part") "1N4007") (field (name "BOM_Supplier Part") "C106903"))
      (libsource (lib "") (part "1N4007"))
    )
    (comp (ref "J2")
      (value "FPGA_FLASH")
      (fields (field (name "BOM_Supplier Part") "C65114"))
      (libsource (lib "") (part "HDR-M-2.54_2x3"))
    )
    (comp (ref "J3")
      (value "SPECIAL IC")
      (fields (field (name "BOM_Supplier Part") "C66690"))
      (libsource (lib "") (part "HDR-M-2.54_2x2"))
    )
    (comp (ref "J5")
      (value "JTAG")
      (fields (field (name "BOM_Supplier Part") "C178292"))
      (libsource (lib "") (part "HDR-M-2.54_2x5"))
    )
    (comp (ref "L1")
      (value "2200Ω")
      (fields
        (field (name "BOM_Manufacturer Part") "BLM21PG221SN1D")
        (field (name "BOM_Supplier Part") "C85840")
      )
      (libsource (lib "") (part "BLM21PG221SN1D"))
    )
    (comp (ref "L2")
      (value "2200Ω")
      (fields
        (field (name "BOM_Manufacturer Part") "BLM21PG221SN1D")
        (field (name "BOM_Supplier Part") "C85840")
      )
      (libsource (lib "") (part "BLM21PG221SN1D"))
    )
    (comp (ref "L3")
      (value "2200Ω")
      (fields
        (field (name "BOM_Manufacturer Part") "BLM21PG221SN1D")
        (field (name "BOM_Supplier Part") "C85840")
      )
      (libsource (lib "") (part "BLM21PG221SN1D"))
    )
    (comp (ref "L4")
      (value "2200Ω")
      (fields
        (field (name "BOM_Manufacturer Part") "BLM21PG221SN1D")
        (field (name "BOM_Supplier Part") "C85840")
      )
      (libsource (lib "") (part "BLM21PG221SN1D"))
    )
    (comp (ref "R1") (value "33") (libsource (lib "") (part "R_0805_EU_3")))
    (comp (ref "R2") (value "10K") (libsource (lib "") (part "R_0805_EU")))
    (comp (ref "R3") (value "10K") (libsource (lib "") (part "R_0805_EU")))
    (comp (ref "R4") (value "33") (libsource (lib "") (part "R_0805_EU_1")))
    (comp (ref "R5") (value "10K") (libsource (lib "") (part "R_0805_EU")))
    (comp (ref "R6") (value "10K") (libsource (lib "") (part "R_0805_EU_1")))
    (comp (ref "R7") (value "10k") (libsource (lib "") (part "R_0805_EU_1")))
    (comp (ref "R8") (value "10K") (libsource (lib "") (part "R_0805_EU_2")))
    (comp (ref "R9") (value "10K") (libsource (lib "") (part "R_0805_EU_2")))
    (comp (ref "R10") (value "10K") (libsource (lib "") (part "R_0805_EU_2")))
    (comp (ref "R11") (value "10K") (libsource (lib "") (part "R_0805_EU_2")))
    (comp (ref "R12") (value "10K") (libsource (lib "") (part "R_0805_EU_2")))
    (comp (ref "R13") (value "1K") (libsource (lib "") (part "R_0805_EU_1")))
    (comp (ref "R14") (value "1K") (libsource (lib "") (part "R_0805_EU_1")))
    (comp (ref "R15") (value "1K") (libsource (lib "") (part "R_0805_EU_1")))
    (comp (ref "R16") (value "1K") (libsource (lib "") (part "R_0805_EU_1")))
    (comp (ref "R17") (value "1K") (libsource (lib "") (part "R_0805_EU_1")))
    (comp (ref "R18") (value "1K") (libsource (lib "") (part "R_0805_EU_1")))
    (comp (ref "R19") (value "1K") (libsource (lib "") (part "R_0805_EU_1")))
    (comp (ref "R20") (value "1K") (libsource (lib "") (part "R_0805_EU_1")))
    (comp (ref "R21") (value "33") (libsource (lib "") (part "R_0805_EU_1")))
    (comp (ref "R49") (value "10K") (libsource (lib "") (part "R_0805_EU")))
    (comp (ref "R50") (value "10K") (libsource (lib "") (part "R_0805_EU")))
    (comp (ref "U3") (value "EP4CE6E22C8N") (libsource (lib "") (part "EP4CE6E22C8N")))
    (comp (ref "U4")
      (value "W25Q80")
      (fields
        (field (name "BOM_Manufacturer Part") "W25Q32FVSSIGTR")
        (field (name "BOM_Supplier Part") "C108057")
      )
      (libsource (lib "") (part "W25Q32FVSSIGTR"))
    )
    (comp (ref "U5")
      (value "UNKOWN IC")
      (fields
        (field (name "BOM_Manufacturer Part") "24LC04BT-I/SN")
        (field (name "BOM_Supplier Part") "C511263")
      )
      (libsource (lib "") (part "24LC04BT-I/SN"))
    )
    (comp (ref "U13")
      (value "MS5351M")
      (fields (field (name "BOM_Supplier Part") "C1509083"))
      (libsource (lib "") (part "MS5351M"))
    )
    (comp (ref "X2")
      (value "25MHz")
      (fields
        (field (name "BOM_Manufacturer Part") "X503224MSD2GC")
        (field (name "BOM_Supplier Part") "C48304")
      )
      (libsource (lib "") (part "X503224MSD2GC"))
    )
    (comp (ref "C86")
      (value "1nF")
      (fields
        (field (name "BOM_Manufacturer Part") "GRM31B7U3A471JW31L")
        (field (name "BOM_Supplier Part") "C97936")
      )
      (libsource (lib "") (part "GRM31B7U3A471JW31L_2"))
    )
    (comp (ref "C99")
      (value "1nF")
      (fields
        (field (name "BOM_Manufacturer Part") "GRM31B7U3A471JW31L")
        (field (name "BOM_Supplier Part") "C97936")
      )
      (libsource (lib "") (part "GRM31B7U3A471JW31L_1"))
    )
    (comp (ref "C100")
      (value "1nF")
      (fields
        (field (name "BOM_Manufacturer Part") "GRM31B7U3A471JW31L")
        (field (name "BOM_Supplier Part") "C97936")
      )
      (libsource (lib "") (part "GRM31B7U3A471JW31L"))
    )
    (comp (ref "C101")
      (value "1nF")
      (fields
        (field (name "BOM_Manufacturer Part") "GRM31B7U3A471JW31L")
        (field (name "BOM_Supplier Part") "C97936")
      )
      (libsource (lib "") (part "GRM31B7U3A471JW31L"))
    )
    (comp (ref "C102")
      (value "1nF")
      (fields
        (field (name "BOM_Manufacturer Part") "GRM31B7U3A471JW31L")
        (field (name "BOM_Supplier Part") "C97936")
      )
      (libsource (lib "") (part "GRM31B7U3A471JW31L_1"))
    )
    (comp (ref "C103")
      (value "1nF")
      (fields
        (field (name "BOM_Manufacturer Part") "GRM31B7U3A471JW31L")
        (field (name "BOM_Supplier Part") "C97936")
      )
      (libsource (lib "") (part "GRM31B7U3A471JW31L_1"))
    )
    (comp (ref "C104")
      (value "1nF")
      (fields
        (field (name "BOM_Manufacturer Part") "GRM31B7U3A471JW31L")
        (field (name "BOM_Supplier Part") "C97936")
      )
      (libsource (lib "") (part "GRM31B7U3A471JW31L_1"))
    )
    (comp (ref "C105")
      (value "1nF")
      (fields
        (field (name "BOM_Manufacturer Part") "GRM31B7U3A471JW31L")
        (field (name "BOM_Supplier Part") "C97936")
      )
      (libsource (lib "") (part "GRM31B7U3A471JW31L_1"))
    )
    (comp (ref "C106")
      (value "1nF")
      (fields
        (field (name "BOM_Manufacturer Part") "GRM31B7U3A471JW31L")
        (field (name "BOM_Supplier Part") "C97936")
      )
      (libsource (lib "") (part "GRM31B7U3A471JW31L"))
    )
    (comp (ref "C107")
      (value "1nF")
      (fields
        (field (name "BOM_Manufacturer Part") "GRM31B7U3A471JW31L")
        (field (name "BOM_Supplier Part") "C97936")
      )
      (libsource (lib "") (part "GRM31B7U3A471JW31L"))
    )
    (comp (ref "C108")
      (value "1nF")
      (fields
        (field (name "BOM_Manufacturer Part") "GRM31B7U3A471JW31L")
        (field (name "BOM_Supplier Part") "C97936")
      )
      (libsource (lib "") (part "GRM31B7U3A471JW31L"))
    )
    (comp (ref "C109")
      (value "1nF")
      (fields
        (field (name "BOM_Manufacturer Part") "GRM31B7U3A471JW31L")
        (field (name "BOM_Supplier Part") "C97936")
      )
      (libsource (lib "") (part "GRM31B7U3A471JW31L"))
    )
    (comp (ref "C110")
      (value "1nF")
      (fields
        (field (name "BOM_Manufacturer Part") "GRM31B7U3A471JW31L")
        (field (name "BOM_Supplier Part") "C97936")
      )
      (libsource (lib "") (part "GRM31B7U3A471JW31L"))
    )
    (comp (ref "C111")
      (value "1nF")
      (fields
        (field (name "BOM_Manufacturer Part") "GRM31B7U3A471JW31L")
        (field (name "BOM_Supplier Part") "C97936")
      )
      (libsource (lib "") (part "GRM31B7U3A471JW31L"))
    )
    (comp (ref "C112")
      (value "1nF")
      (fields
        (field (name "BOM_Manufacturer Part") "GRM31B7U3A471JW31L")
        (field (name "BOM_Supplier Part") "C97936")
      )
      (libsource (lib "") (part "GRM31B7U3A471JW31L"))
    )
    (comp (ref "C113")
      (value "1nF")
      (fields
        (field (name "BOM_Manufacturer Part") "GRM31B7U3A471JW31L")
        (field (name "BOM_Supplier Part") "C97936")
      )
      (libsource (lib "") (part "GRM31B7U3A471JW31L"))
    )
    (comp (ref "C114")
      (value "1nF")
      (fields
        (field (name "BOM_Manufacturer Part") "GRM31B7U3A471JW31L")
        (field (name "BOM_Supplier Part") "C97936")
      )
      (libsource (lib "") (part "GRM31B7U3A471JW31L"))
    )
    (comp (ref "C115")
      (value "1nF")
      (fields
        (field (name "BOM_Manufacturer Part") "GRM31B7U3A471JW31L")
        (field (name "BOM_Supplier Part") "C97936")
      )
      (libsource (lib "") (part "GRM31B7U3A471JW31L"))
    )
    (comp (ref "C116")
      (value "1nF")
      (fields
        (field (name "BOM_Manufacturer Part") "GRM31B7U3A471JW31L")
        (field (name "BOM_Supplier Part") "C97936")
      )
      (libsource (lib "") (part "GRM31B7U3A471JW31L_2"))
    )
    (comp (ref "C117")
      (value "1nF")
      (fields
        (field (name "BOM_Manufacturer Part") "GRM31B7U3A471JW31L")
        (field (name "BOM_Supplier Part") "C97936")
      )
      (libsource (lib "") (part "GRM31B7U3A471JW31L"))
    )
    (comp (ref "C118")
      (value "1nF")
      (fields
        (field (name "BOM_Manufacturer Part") "GRM31B7U3A471JW31L")
        (field (name "BOM_Supplier Part") "C97936")
      )
      (libsource (lib "") (part "GRM31B7U3A471JW31L"))
    )
    (comp (ref "C119")
      (value "1nF")
      (fields
        (field (name "BOM_Manufacturer Part") "GRM31B7U3A471JW31L")
        (field (name "BOM_Supplier Part") "C97936")
      )
      (libsource (lib "") (part "GRM31B7U3A471JW31L"))
    )
    (comp (ref "C121")
      (value "1nF")
      (fields
        (field (name "BOM_Manufacturer Part") "GRM31B7U3A471JW31L")
        (field (name "BOM_Supplier Part") "C97936")
      )
      (libsource (lib "") (part "GRM31B7U3A471JW31L"))
    )
    (comp (ref "C122")
      (value "1nF")
      (fields
        (field (name "BOM_Manufacturer Part") "GRM31B7U3A471JW31L")
        (field (name "BOM_Supplier Part") "C97936")
      )
      (libsource (lib "") (part "GRM31B7U3A471JW31L"))
    )
    (comp (ref "C123")
      (value "1nF")
      (fields
        (field (name "BOM_Manufacturer Part") "GRM31B7U3A471JW31L")
        (field (name "BOM_Supplier Part") "C97936")
      )
      (libsource (lib "") (part "GRM31B7U3A471JW31L"))
    )
    (comp (ref "C124")
      (value "1nF")
      (fields
        (field (name "BOM_Manufacturer Part") "GRM31B7U3A471JW31L")
        (field (name "BOM_Supplier Part") "C97936")
      )
      (libsource (lib "") (part "GRM31B7U3A471JW31L"))
    )
    (comp (ref "C125")
      (value "1nF")
      (fields
        (field (name "BOM_Manufacturer Part") "GRM31B7U3A471JW31L")
        (field (name "BOM_Supplier Part") "C97936")
      )
      (libsource (lib "") (part "GRM31B7U3A471JW31L"))
    )
    (comp (ref "C126")
      (value "1nF")
      (fields
        (field (name "BOM_Manufacturer Part") "GRM31B7U3A471JW31L")
        (field (name "BOM_Supplier Part") "C97936")
      )
      (libsource (lib "") (part "GRM31B7U3A471JW31L"))
    )
    (comp (ref "C127")
      (value "1nF")
      (fields
        (field (name "BOM_Manufacturer Part") "GRM31B7U3A471JW31L")
        (field (name "BOM_Supplier Part") "C97936")
      )
      (libsource (lib "") (part "GRM31B7U3A471JW31L_1"))
    )
    (comp (ref "C128")
      (value "1nF")
      (fields
        (field (name "BOM_Manufacturer Part") "GRM31B7U3A471JW31L")
        (field (name "BOM_Supplier Part") "C97936")
      )
      (libsource (lib "") (part "GRM31B7U3A471JW31L_1"))
    )
    (comp (ref "C129")
      (value "1nF")
      (fields
        (field (name "BOM_Manufacturer Part") "GRM31B7U3A471JW31L")
        (field (name "BOM_Supplier Part") "C97936")
      )
      (libsource (lib "") (part "GRM31B7U3A471JW31L_1"))
    )
    (comp (ref "C130")
      (value "1nF")
      (fields
        (field (name "BOM_Manufacturer Part") "GRM31B7U3A471JW31L")
        (field (name "BOM_Supplier Part") "C97936")
      )
      (libsource (lib "") (part "GRM31B7U3A471JW31L_1"))
    )
    (comp (ref "C133")
      (value "1nF")
      (fields
        (field (name "BOM_Manufacturer Part") "GRM31B7U3A471JW31L")
        (field (name "BOM_Supplier Part") "C97936")
      )
      (libsource (lib "") (part "GRM31B7U3A471JW31L_1"))
    )
    (comp (ref "C134")
      (value "1nF")
      (fields
        (field (name "BOM_Manufacturer Part") "GRM31B7U3A471JW31L")
        (field (name "BOM_Supplier Part") "C97936")
      )
      (libsource (lib "") (part "GRM31B7U3A471JW31L_3"))
    )
    (comp (ref "C135")
      (value "1nF")
      (fields
        (field (name "BOM_Manufacturer Part") "GRM31B7U3A471JW31L")
        (field (name "BOM_Supplier Part") "C97936")
      )
      (libsource (lib "") (part "GRM31B7U3A471JW31L_2"))
    )
    (comp (ref "C149")
      (value "1nF")
      (fields
        (field (name "BOM_Manufacturer Part") "GRM31B7U3A471JW31L")
        (field (name "BOM_Supplier Part") "C97936")
      )
      (libsource (lib "") (part "GRM31B7U3A471JW31L_3"))
    )
    (comp (ref "C150")
      (value "1nF")
      (fields
        (field (name "BOM_Manufacturer Part") "GRM31B7U3A471JW31L")
        (field (name "BOM_Supplier Part") "C97936")
      )
      (libsource (lib "") (part "GRM31B7U3A471JW31L_2"))
    )
    (comp (ref "K1")
      (value "HFD4/3-S1R")
      (fields (field (name "BOM_Supplier Part") "C143232"))
      (libsource (lib "") (part "HFD4/3-S1R"))
    )
    (comp (ref "K2")
      (value "HFD4/3-S1R")
      (fields (field (name "BOM_Supplier Part") "C143232"))
      (libsource (lib "") (part "HFD4/3-S1R"))
    )
    (comp (ref "K3")
      (value "HFD4/3-S1R")
      (fields (field (name "BOM_Supplier Part") "C143232"))
      (libsource (lib "") (part "HFD4/3-S1R"))
    )
    (comp (ref "K4")
      (value "HFD4/3-S1R")
      (fields (field (name "BOM_Supplier Part") "C143232"))
      (libsource (lib "") (part "HFD4/3-S1R"))
    )
    (comp (ref "K5")
      (value "HFD4/3-S1R")
      (fields (field (name "BOM_Supplier Part") "C143232"))
      (libsource (lib "") (part "HFD4/3-S1R"))
    )
    (comp (ref "K6")
      (value "HFD4/3-S1R")
      (fields (field (name "BOM_Supplier Part") "C143232"))
      (libsource (lib "") (part "HFD4/3-S1R"))
    )
    (comp (ref "Q1")
      (value "SS8550")
      (fields (field (name "BOM_Supplier Part") "C909745"))
      (libsource (lib "") (part "SS8550"))
    )
    (comp (ref "Q2")
      (value "SS8550")
      (fields (field (name "BOM_Supplier Part") "C909745"))
      (libsource (lib "") (part "SS8550"))
    )
    (comp (ref "Q3")
      (value "SS8550")
      (fields (field (name "BOM_Supplier Part") "C909745"))
      (libsource (lib "") (part "SS8550"))
    )
    (comp (ref "Q4")
      (value "SS8550")
      (fields (field (name "BOM_Supplier Part") "C909745"))
      (libsource (lib "") (part "SS8550"))
    )
    (comp (ref "Q5")
      (value "SS8550")
      (fields (field (name "BOM_Supplier Part") "C909745"))
      (libsource (lib "") (part "SS8550"))
    )
    (comp (ref "Q6")
      (value "SS8550")
      (fields (field (name "BOM_Supplier Part") "C909745"))
      (libsource (lib "") (part "SS8550"))
    )
    (comp (ref "R62") (value "150") (libsource (lib "") (part "R_0805_EU")))
    (comp (ref "R63") (value "3M") (libsource (lib "") (part "R_0805_EU")))
    (comp (ref "R64") (value "2M7") (libsource (lib "") (part "R_0805_EU")))
    (comp (ref "R65") (value "1M2") (libsource (lib "") (part "R_0805_EU")))
    (comp (ref "R66") (value "75K") (libsource (lib "") (part "R_0805_EU_1")))
    (comp (ref "R67") (value "360K") (libsource (lib "") (part "R_0805_EU_1")))
    (comp (ref "R68") (value "1M8") (libsource (lib "") (part "R_0805_EU_1")))
    (comp (ref "R69") (value "1K") (libsource (lib "") (part "R_0805_EU_1")))
    (comp (ref "R70") (value "1K") (libsource (lib "") (part "R_0805_EU_1")))
    (comp (ref "R71") (value "100") (libsource (lib "") (part "R_0805_EU_2")))
    (comp (ref "R72") (value "1K") (libsource (lib "") (part "R_0805_EU_1")))
    (comp (ref "R73") (value "1K") (libsource (lib "") (part "R_0805_EU_1")))
    (comp (ref "R74") (value "1M8") (libsource (lib "") (part "R_0805_EU_1")))
    (comp (ref "R75") (value "360K") (libsource (lib "") (part "R_0805_EU_1")))
    (comp (ref "R76") (value "75K") (libsource (lib "") (part "R_0805_EU_1")))
    (comp (ref "R77") (value "1M2") (libsource (lib "") (part "R_0805_EU")))
    (comp (ref "R78") (value "2M7") (libsource (lib "") (part "R_0805_EU")))
    (comp (ref "R79") (value "3M") (libsource (lib "") (part "R_0805_EU")))
    (comp (ref "R80") (value "150") (libsource (lib "") (part "R_0805_EU")))
    (comp (ref "R98") (value "100") (libsource (lib "") (part "R_0805_EU_2")))
    (comp (ref "R99") (value "10") (libsource (lib "") (part "R_0805_EU_1")))
    (comp (ref "R100") (value "10") (libsource (lib "") (part "R_0805_EU_1")))
    (comp (ref "RF1")
      (value "BNC")
      (fields
        (field (name "BOM_Manufacturer Part") "DOSIN-801-0080")
        (field (name "BOM_Supplier Part") "C521219")
      )
      (libsource (lib "") (part "DOSIN-801-0080"))
    )
    (comp (ref "RF2")
      (value "BNC")
      (fields
        (field (name "BOM_Manufacturer Part") "DOSIN-801-0080")
        (field (name "BOM_Supplier Part") "C521219")
      )
      (libsource (lib "") (part "DOSIN-801-0080"))
    )
    (comp (ref "U17")
      (value "RS8751XF")
      (fields (field (name "BOM_Supplier Part") "C236995"))
      (libsource (lib "") (part "RS8751XF"))
    )
    (comp (ref "U18")
      (value "KAQY214STLD")
      (fields (field (name "BOM_Supplier Part") "C113331"))
      (libsource (lib "") (part "KAQY214STLD"))
    )
    (comp (ref "U19")
      (value "KAQY214STLD")
      (fields (field (name "BOM_Supplier Part") "C113331"))
      (libsource (lib "") (part "KAQY214STLD"))
    )
    (comp (ref "U20")
      (value "RS8751XF")
      (fields (field (name "BOM_Supplier Part") "C236995"))
      (libsource (lib "") (part "RS8751XF"))
    )
    (comp (ref "C47")
      (value "1nF")
      (fields
        (field (name "BOM_Manufacturer Part") "GRM31B7U3A471JW31L")
        (field (name "BOM_Supplier Part") "C97936")
      )
      (libsource (lib "") (part "GRM31B7U3A471JW31L"))
    )
    (comp (ref "C54")
      (value "1nF")
      (fields
        (field (name "BOM_Manufacturer Part") "GRM31B7U3A471JW31L")
        (field (name "BOM_Supplier Part") "C97936")
      )
      (libsource (lib "") (part "GRM31B7U3A471JW31L"))
    )
    (comp (ref "C60")
      (value "1nF")
      (fields
        (field (name "BOM_Manufacturer Part") "GRM31B7U3A471JW31L")
        (field (name "BOM_Supplier Part") "C97936")
      )
      (libsource (lib "") (part "GRM31B7U3A471JW31L"))
    )
    (comp (ref "C61")
      (value "1nF")
      (fields
        (field (name "BOM_Manufacturer Part") "GRM31B7U3A471JW31L")
        (field (name "BOM_Supplier Part") "C97936")
      )
      (libsource (lib "") (part "GRM31B7U3A471JW31L"))
    )
    (comp (ref "C62")
      (value "1nF")
      (fields
        (field (name "BOM_Manufacturer Part") "GRM31B7U3A471JW31L")
        (field (name "BOM_Supplier Part") "C97936")
      )
      (libsource (lib "") (part "GRM31B7U3A471JW31L"))
    )
    (comp (ref "C63")
      (value "1nF")
      (fields
        (field (name "BOM_Manufacturer Part") "GRM31B7U3A471JW31L")
        (field (name "BOM_Supplier Part") "C97936")
      )
      (libsource (lib "") (part "GRM31B7U3A471JW31L"))
    )
    (comp (ref "C64")
      (value "1nF")
      (fields
        (field (name "BOM_Manufacturer Part") "GRM31B7U3A471JW31L")
        (field (name "BOM_Supplier Part") "C97936")
      )
      (libsource (lib "") (part "GRM31B7U3A471JW31L"))
    )
    (comp (ref "C65")
      (value "1nF")
      (fields
        (field (name "BOM_Manufacturer Part") "GRM31B7U3A471JW31L")
        (field (name "BOM_Supplier Part") "C97936")
      )
      (libsource (lib "") (part "GRM31B7U3A471JW31L"))
    )
    (comp (ref "C66")
      (value "1nF")
      (fields
        (field (name "BOM_Manufacturer Part") "GRM31B7U3A471JW31L")
        (field (name "BOM_Supplier Part") "C97936")
      )
      (libsource (lib "") (part "GRM31B7U3A471JW31L"))
    )
    (comp (ref "C67")
      (value "1nF")
      (fields
        (field (name "BOM_Manufacturer Part") "GRM31B7U3A471JW31L")
        (field (name "BOM_Supplier Part") "C97936")
      )
      (libsource (lib "") (part "GRM31B7U3A471JW31L"))
    )
    (comp (ref "C68")
      (value "1nF")
      (fields
        (field (name "BOM_Manufacturer Part") "GRM31B7U3A471JW31L")
        (field (name "BOM_Supplier Part") "C97936")
      )
      (libsource (lib "") (part "GRM31B7U3A471JW31L"))
    )
    (comp (ref "C69")
      (value "1nF")
      (fields
        (field (name "BOM_Manufacturer Part") "GRM31B7U3A471JW31L")
        (field (name "BOM_Supplier Part") "C97936")
      )
      (libsource (lib "") (part "GRM31B7U3A471JW31L"))
    )
    (comp (ref "C70")
      (value "1nF")
      (fields
        (field (name "BOM_Manufacturer Part") "GRM31B7U3A471JW31L")
        (field (name "BOM_Supplier Part") "C97936")
      )
      (libsource (lib "") (part "GRM31B7U3A471JW31L"))
    )
    (comp (ref "C71")
      (value "1nF")
      (fields
        (field (name "BOM_Manufacturer Part") "GRM31B7U3A471JW31L")
        (field (name "BOM_Supplier Part") "C97936")
      )
      (libsource (lib "") (part "GRM31B7U3A471JW31L"))
    )
    (comp (ref "C72")
      (value "1nF")
      (fields
        (field (name "BOM_Manufacturer Part") "GRM31B7U3A471JW31L")
        (field (name "BOM_Supplier Part") "C97936")
      )
      (libsource (lib "") (part "GRM31B7U3A471JW31L"))
    )
    (comp (ref "C76")
      (value "1nF")
      (fields
        (field (name "BOM_Manufacturer Part") "GRM31B7U3A471JW31L")
        (field (name "BOM_Supplier Part") "C97936")
      )
      (libsource (lib "") (part "GRM31B7U3A471JW31L"))
    )
    (comp (ref "C87")
      (value "1nF")
      (fields
        (field (name "BOM_Manufacturer Part") "GRM31B7U3A471JW31L")
        (field (name "BOM_Supplier Part") "C97936")
      )
      (libsource (lib "") (part "GRM31B7U3A471JW31L"))
    )
    (comp (ref "C88")
      (value "1nF")
      (fields
        (field (name "BOM_Manufacturer Part") "GRM31B7U3A471JW31L")
        (field (name "BOM_Supplier Part") "C97936")
      )
      (libsource (lib "") (part "GRM31B7U3A471JW31L"))
    )
    (comp (ref "C89")
      (value "1nF")
      (fields
        (field (name "BOM_Manufacturer Part") "GRM31B7U3A471JW31L")
        (field (name "BOM_Supplier Part") "C97936")
      )
      (libsource (lib "") (part "GRM31B7U3A471JW31L"))
    )
    (comp (ref "C90")
      (value "1nF")
      (fields
        (field (name "BOM_Manufacturer Part") "GRM31B7U3A471JW31L")
        (field (name "BOM_Supplier Part") "C97936")
      )
      (libsource (lib "") (part "GRM31B7U3A471JW31L"))
    )
    (comp (ref "C91")
      (value "1nF")
      (fields
        (field (name "BOM_Manufacturer Part") "GRM31B7U3A471JW31L")
        (field (name "BOM_Supplier Part") "C97936")
      )
      (libsource (lib "") (part "GRM31B7U3A471JW31L"))
    )
    (comp (ref "C92")
      (value "1nF")
      (fields
        (field (name "BOM_Manufacturer Part") "GRM31B7U3A471JW31L")
        (field (name "BOM_Supplier Part") "C97936")
      )
      (libsource (lib "") (part "GRM31B7U3A471JW31L"))
    )
    (comp (ref "C93")
      (value "1nF")
      (fields
        (field (name "BOM_Manufacturer Part") "GRM31B7U3A471JW31L")
        (field (name "BOM_Supplier Part") "C97936")
      )
      (libsource (lib "") (part "GRM31B7U3A471JW31L"))
    )
    (comp (ref "C94")
      (value "1nF")
      (fields
        (field (name "BOM_Manufacturer Part") "GRM31B7U3A471JW31L")
        (field (name "BOM_Supplier Part") "C97936")
      )
      (libsource (lib "") (part "GRM31B7U3A471JW31L"))
    )
    (comp (ref "C95")
      (value "1nF")
      (fields
        (field (name "BOM_Manufacturer Part") "GRM31B7U3A471JW31L")
        (field (name "BOM_Supplier Part") "C97936")
      )
      (libsource (lib "") (part "GRM31B7U3A471JW31L"))
    )
    (comp (ref "C96")
      (value "1nF")
      (fields
        (field (name "BOM_Manufacturer Part") "GRM31B7U3A471JW31L")
        (field (name "BOM_Supplier Part") "C97936")
      )
      (libsource (lib "") (part "GRM31B7U3A471JW31L"))
    )
    (comp (ref "C97")
      (value "1nF")
      (fields
        (field (name "BOM_Manufacturer Part") "GRM31B7U3A471JW31L")
        (field (name "BOM_Supplier Part") "C97936")
      )
      (libsource (lib "") (part "GRM31B7U3A471JW31L"))
    )
    (comp (ref "C98")
      (value "1nF")
      (fields
        (field (name "BOM_Manufacturer Part") "GRM31B7U3A471JW31L")
        (field (name "BOM_Supplier Part") "C97936")
      )
      (libsource (lib "") (part "GRM31B7U3A471JW31L"))
    )
    (comp (ref "C137")
      (value "1nF")
      (fields
        (field (name "BOM_Manufacturer Part") "GRM31B7U3A471JW31L")
        (field (name "BOM_Supplier Part") "C97936")
      )
      (libsource (lib "") (part "GRM31B7U3A471JW31L"))
    )
    (comp (ref "C138")
      (value "1nF")
      (fields
        (field (name "BOM_Manufacturer Part") "GRM31B7U3A471JW31L")
        (field (name "BOM_Supplier Part") "C97936")
      )
      (libsource (lib "") (part "GRM31B7U3A471JW31L"))
    )
    (comp (ref "C139")
      (value "1nF")
      (fields
        (field (name "BOM_Manufacturer Part") "GRM31B7U3A471JW31L")
        (field (name "BOM_Supplier Part") "C97936")
      )
      (libsource (lib "") (part "GRM31B7U3A471JW31L"))
    )
    (comp (ref "C140")
      (value "1nF")
      (fields
        (field (name "BOM_Manufacturer Part") "GRM31B7U3A471JW31L")
        (field (name "BOM_Supplier Part") "C97936")
      )
      (libsource (lib "") (part "GRM31B7U3A471JW31L"))
    )
    (comp (ref "C141")
      (value "1nF")
      (fields
        (field (name "BOM_Manufacturer Part") "GRM31B7U3A471JW31L")
        (field (name "BOM_Supplier Part") "C97936")
      )
      (libsource (lib "") (part "GRM31B7U3A471JW31L"))
    )
    (comp (ref "C142")
      (value "1nF")
      (fields
        (field (name "BOM_Manufacturer Part") "GRM31B7U3A471JW31L")
        (field (name "BOM_Supplier Part") "C97936")
      )
      (libsource (lib "") (part "GRM31B7U3A471JW31L"))
    )
    (comp (ref "C143")
      (value "1nF")
      (fields
        (field (name "BOM_Manufacturer Part") "GRM31B7U3A471JW31L")
        (field (name "BOM_Supplier Part") "C97936")
      )
      (libsource (lib "") (part "GRM31B7U3A471JW31L"))
    )
    (comp (ref "C144")
      (value "1nF")
      (fields
        (field (name "BOM_Manufacturer Part") "GRM31B7U3A471JW31L")
        (field (name "BOM_Supplier Part") "C97936")
      )
      (libsource (lib "") (part "GRM31B7U3A471JW31L"))
    )
    (comp (ref "C145")
      (value "1nF")
      (fields
        (field (name "BOM_Manufacturer Part") "GRM31B7U3A471JW31L")
        (field (name "BOM_Supplier Part") "C97936")
      )
      (libsource (lib "") (part "GRM31B7U3A471JW31L"))
    )
    (comp (ref "C146")
      (value "1nF")
      (fields
        (field (name "BOM_Manufacturer Part") "GRM31B7U3A471JW31L")
        (field (name "BOM_Supplier Part") "C97936")
      )
      (libsource (lib "") (part "GRM31B7U3A471JW31L"))
    )
    (comp (ref "C147")
      (value "1nF")
      (fields
        (field (name "BOM_Manufacturer Part") "GRM31B7U3A471JW31L")
        (field (name "BOM_Supplier Part") "C97936")
      )
      (libsource (lib "") (part "GRM31B7U3A471JW31L"))
    )
    (comp (ref "C148")
      (value "1nF")
      (fields
        (field (name "BOM_Manufacturer Part") "GRM31B7U3A471JW31L")
        (field (name "BOM_Supplier Part") "C97936")
      )
      (libsource (lib "") (part "GRM31B7U3A471JW31L"))
    )
    (comp (ref "CON1") (value "POWER IN") (libsource (lib "") (part "XH2.54-2P")))
    (comp (ref "D4")
      (value "1N5819")
      (fields (field (name "BOM_Manufacturer Part") "1N4007") (field (name "BOM_Supplier Part") "C106903"))
      (libsource (lib "") (part "1N4007_1"))
    )
    (comp (ref "D5")
      (value "1N5819")
      (fields (field (name "BOM_Manufacturer Part") "1N4007") (field (name "BOM_Supplier Part") "C106903"))
      (libsource (lib "") (part "1N4007"))
    )
    (comp (ref "D6")
      (value "SS34")
      (fields (field (name "BOM_Supplier Part") "C13763"))
      (libsource (lib "") (part "SS34_1"))
    )
    (comp (ref "D7")
      (value "SS34")
      (fields (field (name "BOM_Supplier Part") "C13763"))
      (libsource (lib "") (part "SS34"))
    )
    (comp (ref "D8")
      (value "SS34")
      (fields (field (name "BOM_Supplier Part") "C13763"))
      (libsource (lib "") (part "SS34_2"))
    )
    (comp (ref "D9")
      (value "BZT52C8V2")
      (fields (field (name "BOM_Supplier Part") "C2122"))
      (libsource (lib "") (part "BZT52C8V2"))
    )
    (comp (ref "D10")
      (value "SS34")
      (fields (field (name "BOM_Supplier Part") "C13763"))
      (libsource (lib "") (part "SS34_1"))
    )
    (comp (ref "D11")
      (value "1N5819")
      (fields (field (name "BOM_Manufacturer Part") "1N4007") (field (name "BOM_Supplier Part") "C106903"))
      (libsource (lib "") (part "1N4007"))
    )
    (comp (ref "D12")
      (value "1N5819")
      (fields (field (name "BOM_Manufacturer Part") "1N4007") (field (name "BOM_Supplier Part") "C106903"))
      (libsource (lib "") (part "1N4007"))
    )
    (comp (ref "D13")
      (value "1N5819")
      (fields (field (name "BOM_Manufacturer Part") "1N4007") (field (name "BOM_Supplier Part") "C106903"))
      (libsource (lib "") (part "1N4007_1"))
    )
    (comp (ref "L5")
      (value "10uH")
      (fields
        (field (name "BOM_Manufacturer Part") "SMDRI74-101MT")
        (field (name "BOM_Supplier Part") "C36970")
      )
      (libsource (lib "") (part "SMDRI74-101MT_1"))
    )
    (comp (ref "L6")
      (value "10uH")
      (fields
        (field (name "BOM_Manufacturer Part") "SMDRI74-101MT")
        (field (name "BOM_Supplier Part") "C36970")
      )
      (libsource (lib "") (part "SMDRI74-101MT"))
    )
    (comp (ref "Q7")
      (value "SS8050-H")
      (fields (field (name "BOM_Supplier Part") "C699255"))
      (libsource (lib "") (part "SS8050-H"))
    )
    (comp (ref "Q8")
      (value "CJ3401")
      (fields (field (name "BOM_Supplier Part") "C13799"))
      (libsource (lib "") (part "CJ3401"))
    )
    (comp (ref "R46") (value "1K") (libsource (lib "") (part "R_0805_EU_1")))
    (comp (ref "R47") (value "10K") (libsource (lib "") (part "R_0805_EU_3")))
    (comp (ref "R48") (value "10K") (libsource (lib "") (part "R_0805_EU")))
    (comp (ref "R51") (value "10K") (libsource (lib "") (part "R_0805_EU")))
    (comp (ref "R53") (value "10K") (libsource (lib "") (part "R_0805_EU")))
    (comp (ref "R56") (value "12K") (libsource (lib "") (part "R_0805_EU")))
    (comp (ref "R57") (value "1K") (libsource (lib "") (part "R_0805_EU")))
    (comp (ref "R58") (value "10K") (libsource (lib "") (part "R_0805_EU")))
    (comp (ref "R59") (value "1K") (libsource (lib "") (part "R_0805_EU")))
    (comp (ref "R60") (value "1") (libsource (lib "") (part "R_0805_EU")))
    (comp (ref "R61") (value "1") (libsource (lib "") (part "R_0805_EU")))
    (comp (ref "R81") (value "100") (libsource (lib "") (part "R_0805_EU_2")))
    (comp (ref "S1")
      (value "POWER ON/OFF")
      (fields
        (field (name "BOM_Manufacturer Part") "BUTTON")
        (field (name "BOM_Supplier Part") "C9900015607")
      )
      (libsource (lib "") (part "BUTTON"))
    )
    (comp (ref "U6")
      (value "AMS1117-2.5")
      (fields (field (name "BOM_Supplier Part") "C963405"))
      (libsource (lib "") (part "AMS1117-2.5_C963405"))
    )
    (comp (ref "U9")
      (value "6210_2046/33")
      (fields
        (field (name "BOM_Manufacturer Part") "TC1108-3.3VDBTR")
        (field (name "BOM_Supplier Part") "C622711")
      )
      (libsource (lib "") (part "6210_2046/33"))
    )
    (comp (ref "U10")
      (value "AMS1117-1.2")
      (fields
        (field (name "BOM_Manufacturer Part") "AMS1117-2.5")
        (field (name "BOM_Supplier Part") "C963405")
      )
      (libsource (lib "") (part "AMS1117-2.5_C963405"))
    )
    (comp (ref "U11")
      (value "TLV70033DDCT")
      (fields (field (name "BOM_Supplier Part") "C2877582"))
      (libsource (lib "") (part "TLV70033DDCT"))
    )
    (comp (ref "U12")
      (value "LM6206N3 (65Z5)")
      (fields
        (field (name "BOM_Manufacturer Part") "LM6206N3")
        (field (name "BOM_Supplier Part") "LM6206N3 (662K)")
      )
      (libsource (lib "") (part "LM6206N3"))
    )
    (comp (ref "U15")
      (value "TPS61041")
      (fields
        (field (name "BOM_Manufacturer Part") "TPS61040DBVR")
        (field (name "BOM_Supplier Part") "C7722")
      )
      (libsource (lib "") (part "TPS61040DBVR"))
    )
    (comp (ref "U16")
      (value "PT4103B23F")
      (fields (field (name "BOM_Supplier Part") "C19861"))
      (libsource (lib "") (part "PT4103B23F"))
    )
    (comp (ref "U21") (value "TL432") (libsource (lib "") (part "TL431AIDBZTG4")))
    (comp (ref "ZD1")
      (value "BZT52C5V6")
      (fields (field (name "BOM_Supplier Part") "C2119"))
      (libsource (lib "") (part "BZT52C5V6"))
    )
    (comp (ref "C14")
      (value "1nF")
      (fields
        (field (name "BOM_Manufacturer Part") "GRM31B7U3A471JW31L")
        (field (name "BOM_Supplier Part") "C97936")
      )
      (libsource (lib "") (part "GRM31B7U3A471JW31L"))
    )
    (comp (ref "C15")
      (value "1nF")
      (fields
        (field (name "BOM_Manufacturer Part") "GRM31B7U3A471JW31L")
        (field (name "BOM_Supplier Part") "C97936")
      )
      (libsource (lib "") (part "GRM31B7U3A471JW31L"))
    )
    (comp (ref "C16")
      (value "1nF")
      (fields
        (field (name "BOM_Manufacturer Part") "GRM31B7U3A471JW31L")
        (field (name "BOM_Supplier Part") "C97936")
      )
      (libsource (lib "") (part "GRM31B7U3A471JW31L"))
    )
    (comp (ref "C17")
      (value "1nF")
      (fields
        (field (name "BOM_Manufacturer Part") "GRM31B7U3A471JW31L")
        (field (name "BOM_Supplier Part") "C97936")
      )
      (libsource (lib "") (part "GRM31B7U3A471JW31L"))
    )
    (comp (ref "C18")
      (value "1nF")
      (fields
        (field (name "BOM_Manufacturer Part") "GRM31B7U3A471JW31L")
        (field (name "BOM_Supplier Part") "C97936")
      )
      (libsource (lib "") (part "GRM31B7U3A471JW31L"))
    )
    (comp (ref "C19")
      (value "1nF")
      (fields
        (field (name "BOM_Manufacturer Part") "GRM31B7U3A471JW31L")
        (field (name "BOM_Supplier Part") "C97936")
      )
      (libsource (lib "") (part "GRM31B7U3A471JW31L"))
    )
    (comp (ref "C20")
      (value "1nF")
      (fields
        (field (name "BOM_Manufacturer Part") "GRM31B7U3A471JW31L")
        (field (name "BOM_Supplier Part") "C97936")
      )
      (libsource (lib "") (part "GRM31B7U3A471JW31L"))
    )
    (comp (ref "C21")
      (value "1nF")
      (fields
        (field (name "BOM_Manufacturer Part") "GRM31B7U3A471JW31L")
        (field (name "BOM_Supplier Part") "C97936")
      )
      (libsource (lib "") (part "GRM31B7U3A471JW31L"))
    )
    (comp (ref "C22")
      (value "1nF")
      (fields
        (field (name "BOM_Manufacturer Part") "GRM31B7U3A471JW31L")
        (field (name "BOM_Supplier Part") "C97936")
      )
      (libsource (lib "") (part "GRM31B7U3A471JW31L"))
    )
    (comp (ref "C23")
      (value "1nF")
      (fields
        (field (name "BOM_Manufacturer Part") "GRM31B7U3A471JW31L")
        (field (name "BOM_Supplier Part") "C97936")
      )
      (libsource (lib "") (part "GRM31B7U3A471JW31L"))
    )
    (comp (ref "C24")
      (value "1nF")
      (fields
        (field (name "BOM_Manufacturer Part") "GRM31B7U3A471JW31L")
        (field (name "BOM_Supplier Part") "C97936")
      )
      (libsource (lib "") (part "GRM31B7U3A471JW31L"))
    )
    (comp (ref "C25")
      (value "1nF")
      (fields
        (field (name "BOM_Manufacturer Part") "GRM31B7U3A471JW31L")
        (field (name "BOM_Supplier Part") "C97936")
      )
      (libsource (lib "") (part "GRM31B7U3A471JW31L"))
    )
    (comp (ref "C26")
      (value "1nF")
      (fields
        (field (name "BOM_Manufacturer Part") "GRM31B7U3A471JW31L")
        (field (name "BOM_Supplier Part") "C97936")
      )
      (libsource (lib "") (part "GRM31B7U3A471JW31L"))
    )
    (comp (ref "C27")
      (value "1nF")
      (fields
        (field (name "BOM_Manufacturer Part") "GRM31B7U3A471JW31L")
        (field (name "BOM_Supplier Part") "C97936")
      )
      (libsource (lib "") (part "GRM31B7U3A471JW31L"))
    )
    (comp (ref "C28")
      (value "1nF")
      (fields
        (field (name "BOM_Manufacturer Part") "GRM31B7U3A471JW31L")
        (field (name "BOM_Supplier Part") "C97936")
      )
      (libsource (lib "") (part "GRM31B7U3A471JW31L"))
    )
    (comp (ref "C29")
      (value "1nF")
      (fields
        (field (name "BOM_Manufacturer Part") "GRM31B7U3A471JW31L")
        (field (name "BOM_Supplier Part") "C97936")
      )
      (libsource (lib "") (part "GRM31B7U3A471JW31L"))
    )
    (comp (ref "C30")
      (value "1nF")
      (fields
        (field (name "BOM_Manufacturer Part") "GRM31B7U3A471JW31L")
        (field (name "BOM_Supplier Part") "C97936")
      )
      (libsource (lib "") (part "GRM31B7U3A471JW31L"))
    )
    (comp (ref "C80")
      (value "1nF")
      (fields
        (field (name "BOM_Manufacturer Part") "GRM31B7U3A471JW31L")
        (field (name "BOM_Supplier Part") "C97936")
      )
      (libsource (lib "") (part "GRM31B7U3A471JW31L"))
    )
    (comp (ref "C81")
      (value "1nF")
      (fields
        (field (name "BOM_Manufacturer Part") "GRM31B7U3A471JW31L")
        (field (name "BOM_Supplier Part") "C97936")
      )
      (libsource (lib "") (part "GRM31B7U3A471JW31L"))
    )
    (comp (ref "C82")
      (value "1nF")
      (fields
        (field (name "BOM_Manufacturer Part") "GRM31B7U3A471JW31L")
        (field (name "BOM_Supplier Part") "C97936")
      )
      (libsource (lib "") (part "GRM31B7U3A471JW31L"))
    )
    (comp (ref "C83")
      (value "1nF")
      (fields
        (field (name "BOM_Manufacturer Part") "GRM31B7U3A471JW31L")
        (field (name "BOM_Supplier Part") "C97936")
      )
      (libsource (lib "") (part "GRM31B7U3A471JW31L"))
    )
    (comp (ref "C84")
      (value "1nF")
      (fields
        (field (name "BOM_Manufacturer Part") "GRM31B7U3A471JW31L")
        (field (name "BOM_Supplier Part") "C97936")
      )
      (libsource (lib "") (part "GRM31B7U3A471JW31L_1"))
    )
    (comp (ref "C85")
      (value "1nF")
      (fields
        (field (name "BOM_Manufacturer Part") "GRM31B7U3A471JW31L")
        (field (name "BOM_Supplier Part") "C97936")
      )
      (libsource (lib "") (part "GRM31B7U3A471JW31L"))
    )
    (comp (ref "D14")
      (value "1N5819")
      (fields (field (name "BOM_Manufacturer Part") "1N4007") (field (name "BOM_Supplier Part") "C106903"))
      (libsource (lib "") (part "1N4007"))
    )
    (comp (ref "D15")
      (value "1N5819")
      (fields (field (name "BOM_Manufacturer Part") "1N4007") (field (name "BOM_Supplier Part") "C106903"))
      (libsource (lib "") (part "1N4007"))
    )
    (comp (ref "R22") (value "200") (libsource (lib "") (part "R_0805_EU_1")))
    (comp (ref "R23") (value "200") (libsource (lib "") (part "R_0805_EU_1")))
    (comp (ref "R24") (value "1K") (libsource (lib "") (part "R_0805_EU_1")))
    (comp (ref "R25") (value "1K") (libsource (lib "") (part "R_0805_EU_1")))
    (comp (ref "R26") (value "1K") (libsource (lib "") (part "R_0805_EU_1")))
    (comp (ref "R27") (value "1K") (libsource (lib "") (part "R_0805_EU_1")))
    (comp (ref "R34") (value "1K5") (libsource (lib "") (part "R_0805_EU_1")))
    (comp (ref "R35") (value "750") (libsource (lib "") (part "R_0805_EU")))
    (comp (ref "R52") (value "1K5") (libsource (lib "") (part "R_0805_EU_1")))
    (comp (ref "R54") (value "750") (libsource (lib "") (part "R_0805_EU")))
    (comp (ref "R55") (value "1K5") (libsource (lib "") (part "R_0805_EU_1")))
    (comp (ref "R82") (value "10") (libsource (lib "") (part "R_0805_EU")))
    (comp (ref "R83") (value "750") (libsource (lib "") (part "R_0805_EU")))
    (comp (ref "R84") (value "1K5") (libsource (lib "") (part "R_0805_EU_1")))
    (comp (ref "R85") (value "750") (libsource (lib "") (part "R_0805_EU")))
    (comp (ref "R86") (value "1K5") (libsource (lib "") (part "R_0805_EU_1")))
    (comp (ref "R87") (value "750") (libsource (lib "") (part "R_0805_EU")))
    (comp (ref "R88") (value "1K5") (libsource (lib "") (part "R_0805_EU_1")))
    (comp (ref "R89") (value "750") (libsource (lib "") (part "R_0805_EU")))
    (comp (ref "R90") (value "1K5") (libsource (lib "") (part "R_0805_EU_1")))
    (comp (ref "R91") (value "750") (libsource (lib "") (part "R_0805_EU")))
    (comp (ref "R92") (value "1K5") (libsource (lib "") (part "R_0805_EU_1")))
    (comp (ref "R93") (value "1K5") (libsource (lib "") (part "R_0805_EU")))
    (comp (ref "R94") (value "33K") (libsource (lib "") (part "R_0805_EU")))
    (comp (ref "R95") (value "1") (libsource (lib "") (part "R_0805_EU_2")))
    (comp (ref "R96") (value "100") (libsource (lib "") (part "R_0805_EU_1")))
    (comp (ref "R97") (value "100") (libsource (lib "") (part "R_0805_EU_1")))
    (comp (ref "RF3")
      (value "BNC")
      (fields
        (field (name "BOM_Manufacturer Part") "DOSIN-801-0080")
        (field (name "BOM_Supplier Part") "C521219")
      )
      (libsource (lib "") (part "DOSIN-801-0080"))
    )
    (comp (ref "U7") (value "AD9288BSTZ-100") (libsource (lib "") (part "AD9288BSTZ-100")))
    (comp (ref "U8") (value "AD9288BSTZ-100") (libsource (lib "") (part "AD9288BSTZ-100")))
    (comp (ref "U14")
      (value "RS8751XF")
      (fields (field (name "BOM_Supplier Part") "C236995"))
      (libsource (lib "") (part "RS8751XF"))
    )
    (comp (ref "C120")
      (value "1nF")
      (fields
        (field (name "BOM_Manufacturer Part") "GRM31B7U3A471JW31L")
        (field (name "BOM_Supplier Part") "C97936")
      )
      (libsource (lib "") (part "GRM31B7U3A471JW31L"))
    )
    (comp (ref "C131")
      (value "1nF")
      (fields
        (field (name "BOM_Manufacturer Part") "GRM31B7U3A471JW31L")
        (field (name "BOM_Supplier Part") "C97936")
      )
      (libsource (lib "") (part "GRM31B7U3A471JW31L"))
    )
    (comp (ref "C132")
      (value "1nF")
      (fields
        (field (name "BOM_Manufacturer Part") "GRM31B7U3A471JW31L")
        (field (name "BOM_Supplier Part") "C97936")
      )
      (libsource (lib "") (part "GRM31B7U3A471JW31L"))
    )
    (comp (ref "C151")
      (value "1nF")
      (fields
        (field (name "BOM_Manufacturer Part") "GRM31B7U3A471JW31L")
        (field (name "BOM_Supplier Part") "C97936")
      )
      (libsource (lib "") (part "GRM31B7U3A471JW31L"))
    )
    (comp (ref "C152")
      (value "1nF")
      (fields
        (field (name "BOM_Manufacturer Part") "GRM31B7U3A471JW31L")
        (field (name "BOM_Supplier Part") "C97936")
      )
      (libsource (lib "") (part "GRM31B7U3A471JW31L"))
    )
    (comp (ref "C153")
      (value "1nF")
      (fields
        (field (name "BOM_Manufacturer Part") "GRM31B7U3A471JW31L")
        (field (name "BOM_Supplier Part") "C97936")
      )
      (libsource (lib "") (part "GRM31B7U3A471JW31L"))
    )
    (comp (ref "C154")
      (value "1nF")
      (fields
        (field (name "BOM_Manufacturer Part") "GRM31B7U3A471JW31L")
        (field (name "BOM_Supplier Part") "C97936")
      )
      (libsource (lib "") (part "GRM31B7U3A471JW31L"))
    )
    (comp (ref "C155")
      (value "1nF")
      (fields
        (field (name "BOM_Manufacturer Part") "GRM31B7U3A471JW31L")
        (field (name "BOM_Supplier Part") "C97936")
      )
      (libsource (lib "") (part "GRM31B7U3A471JW31L"))
    )
    (comp (ref "C156")
      (value "1nF")
      (fields
        (field (name "BOM_Manufacturer Part") "GRM31B7U3A471JW31L")
        (field (name "BOM_Supplier Part") "C97936")
      )
      (libsource (lib "") (part "GRM31B7U3A471JW31L"))
    )
    (comp (ref "C157")
      (value "1nF")
      (fields
        (field (name "BOM_Manufacturer Part") "GRM31B7U3A471JW31L")
        (field (name "BOM_Supplier Part") "C97936")
      )
      (libsource (lib "") (part "GRM31B7U3A471JW31L"))
    )
    (comp (ref "C158")
      (value "1nF")
      (fields
        (field (name "BOM_Manufacturer Part") "GRM31B7U3A471JW31L")
        (field (name "BOM_Supplier Part") "C97936")
      )
      (libsource (lib "") (part "GRM31B7U3A471JW31L"))
    )
    (comp (ref "C159")
      (value "1nF")
      (fields
        (field (name "BOM_Manufacturer Part") "GRM31B7U3A471JW31L")
        (field (name "BOM_Supplier Part") "C97936")
      )
      (libsource (lib "") (part "GRM31B7U3A471JW31L"))
    )
    (comp (ref "C160")
      (value "1nF")
      (fields
        (field (name "BOM_Manufacturer Part") "GRM31B7U3A471JW31L")
        (field (name "BOM_Supplier Part") "C97936")
      )
      (libsource (lib "") (part "GRM31B7U3A471JW31L"))
    )
    (comp (ref "C161")
      (value "1nF")
      (fields
        (field (name "BOM_Manufacturer Part") "GRM31B7U3A471JW31L")
        (field (name "BOM_Supplier Part") "C97936")
      )
      (libsource (lib "") (part "GRM31B7U3A471JW31L"))
    )
    (comp (ref "C162")
      (value "1nF")
      (fields
        (field (name "BOM_Manufacturer Part") "GRM31B7U3A471JW31L")
        (field (name "BOM_Supplier Part") "C97936")
      )
      (libsource (lib "") (part "GRM31B7U3A471JW31L"))
    )
    (comp (ref "C163")
      (value "1nF")
      (fields
        (field (name "BOM_Manufacturer Part") "GRM31B7U3A471JW31L")
        (field (name "BOM_Supplier Part") "C97936")
      )
      (libsource (lib "") (part "GRM31B7U3A471JW31L"))
    )
    (comp (ref "C164")
      (value "1nF")
      (fields
        (field (name "BOM_Manufacturer Part") "GRM31B7U3A471JW31L")
        (field (name "BOM_Supplier Part") "C97936")
      )
      (libsource (lib "") (part "GRM31B7U3A471JW31L"))
    )
    (comp (ref "C165")
      (value "1nF")
      (fields
        (field (name "BOM_Manufacturer Part") "GRM31B7U3A471JW31L")
        (field (name "BOM_Supplier Part") "C97936")
      )
      (libsource (lib "") (part "GRM31B7U3A471JW31L"))
    )
    (comp (ref "C166")
      (value "1nF")
      (fields
        (field (name "BOM_Manufacturer Part") "GRM31B7U3A471JW31L")
        (field (name "BOM_Supplier Part") "C97936")
      )
      (libsource (lib "") (part "GRM31B7U3A471JW31L"))
    )
    (comp (ref "C167")
      (value "1nF")
      (fields
        (field (name "BOM_Manufacturer Part") "GRM31B7U3A471JW31L")
        (field (name "BOM_Supplier Part") "C97936")
      )
      (libsource (lib "") (part "GRM31B7U3A471JW31L"))
    )
    (comp (ref "D16")
      (value "1N5819")
      (fields (field (name "BOM_Manufacturer Part") "1N4007") (field (name "BOM_Supplier Part") "C106903"))
      (libsource (lib "") (part "1N4007"))
    )
    (comp (ref "J6")
      (value "GD32E230_DEBUG")
      (fields (field (name "BOM_Supplier Part") "C66690"))
      (libsource (lib "") (part "HDR-M-2.54_2x2"))
    )
    (comp (ref "R101") (value "10K") (libsource (lib "") (part "R_0805_EU")))
    (comp (ref "R102") (value "1K") (libsource (lib "") (part "R_0805_EU")))
    (comp (ref "R103") (value "1K") (libsource (lib "") (part "R_0805_EU")))
    (comp (ref "R104") (value "6K2") (libsource (lib "") (part "R_0805_EU")))
    (comp (ref "R105") (value "1K") (libsource (lib "") (part "R_0805_EU")))
    (comp (ref "R106") (value "1K") (libsource (lib "") (part "R_0805_EU")))
    (comp (ref "R107") (value "6K2") (libsource (lib "") (part "R_0805_EU")))
    (comp (ref "R108") (value "6K2") (libsource (lib "") (part "R_0805_EU")))
    (comp (ref "R109") (value "1K") (libsource (lib "") (part "R_0805_EU")))
    (comp (ref "R110") (value "1K") (libsource (lib "") (part "R_0805_EU")))
    (comp (ref "R111") (value "6K2") (libsource (lib "") (part "R_0805_EU")))
    (comp (ref "R112") (value "1K") (libsource (lib "") (part "R_0805_EU")))
    (comp (ref "R113") (value "1K") (libsource (lib "") (part "R_0805_EU")))
    (comp (ref "R114") (value "1K") (libsource (lib "") (part "R_0805_EU")))
    (comp (ref "R115") (value "1K") (libsource (lib "") (part "R_0805_EU")))
    (comp (ref "R116") (value "6K2") (libsource (lib "") (part "R_0805_EU")))
    (comp (ref "R117") (value "1K") (libsource (lib "") (part "R_0805_EU")))
    (comp (ref "R118") (value "1K") (libsource (lib "") (part "R_0805_EU")))
    (comp (ref "R119") (value "6K2") (libsource (lib "") (part "R_0805_EU")))
    (comp (ref "R120") (value "6K2") (libsource (lib "") (part "R_0805_EU")))
    (comp (ref "R121") (value "1K") (libsource (lib "") (part "R_0805_EU")))
    (comp (ref "R122") (value "1K") (libsource (lib "") (part "R_0805_EU")))
    (comp (ref "R123") (value "6K2") (libsource (lib "") (part "R_0805_EU")))
    (comp (ref "R124") (value "1K") (libsource (lib "") (part "R_0805_EU")))
    (comp (ref "R125") (value "1K") (libsource (lib "") (part "R_0805_EU")))
    (comp (ref "R126") (value "6K2") (libsource (lib "") (part "R_0805_EU")))
    (comp (ref "R127") (value "1K") (libsource (lib "") (part "R_0805_EU")))
    (comp (ref "R128") (value "1K") (libsource (lib "") (part "R_0805_EU")))
    (comp (ref "R129") (value "6K2") (libsource (lib "") (part "R_0805_EU")))
    (comp (ref "R130") (value "1K") (libsource (lib "") (part "R_0805_EU")))
    (comp (ref "R131") (value "1K") (libsource (lib "") (part "R_0805_EU")))
    (comp (ref "R132") (value "1K") (libsource (lib "") (part "R_0805_EU")))
    (comp (ref "R133") (value "1K") (libsource (lib "") (part "R_0805_EU")))
    (comp (ref "R134") (value "6K2") (libsource (lib "") (part "R_0805_EU")))
    (comp (ref "R135") (value "1K") (libsource (lib "") (part "R_0805_EU")))
    (comp (ref "R136") (value "1K") (libsource (lib "") (part "R_0805_EU")))
    (comp (ref "R137") (value "6K2") (libsource (lib "") (part "R_0805_EU")))
    (comp (ref "R138") (value "1K") (libsource (lib "") (part "R_0805_EU")))
    (comp (ref "R139") (value "1K") (libsource (lib "") (part "R_0805_EU")))
    (comp (ref "R140") (value "6K2") (libsource (lib "") (part "R_0805_EU")))
    (comp (ref "R141") (value "1K") (libsource (lib "") (part "R_0805_EU")))
    (comp (ref "R142") (value "1K") (libsource (lib "") (part "R_0805_EU")))
    (comp (ref "R143") (value "6K2") (libsource (lib "") (part "R_0805_EU")))
    (comp (ref "R144") (value "6K2") (libsource (lib "") (part "R_0805_EU")))
    (comp (ref "R145") (value "1K") (libsource (lib "") (part "R_0805_EU")))
    (comp (ref "R146") (value "1K") (libsource (lib "") (part "R_0805_EU")))
    (comp (ref "R147") (value "6K2") (libsource (lib "") (part "R_0805_EU")))
    (comp (ref "R148") (value "1K") (libsource (lib "") (part "R_0805_EU")))
    (comp (ref "R149") (value "1K") (libsource (lib "") (part "R_0805_EU")))
    (comp (ref "R150") (value "10K") (libsource (lib "") (part "R_0805_EU_1")))
    (comp (ref "R151") (value "10K") (libsource (lib "") (part "R_0805_EU_1")))
    (comp (ref "R152") (value "10K") (libsource (lib "") (part "R_0805_EU_1")))
    (comp (ref "R153") (value "10K") (libsource (lib "") (part "R_0805_EU_1")))
    (comp (ref "R154") (value "10K") (libsource (lib "") (part "R_0805_EU_1")))
    (comp (ref "R155") (value "10K") (libsource (lib "") (part "R_0805_EU_1")))
    (comp (ref "R156") (value "10K") (libsource (lib "") (part "R_0805_EU")))
    (comp (ref "R157") (value "10K") (libsource (lib "") (part "R_0805_EU")))
    (comp (ref "R158") (value "10K") (libsource (lib "") (part "R_0805_EU")))
    (comp (ref "R159") (value "10K") (libsource (lib "") (part "R_0805_EU")))
    (comp (ref "R160") (value "10K") (libsource (lib "") (part "R_0805_EU")))
    (comp (ref "R161") (value "10K") (libsource (lib "") (part "R_0805_EU")))
    (comp (ref "S2")
      (value "DOWN")
      (fields
        (field (name "BOM_Manufacturer Part") "BUTTON")
        (field (name "BOM_Supplier Part") "C9900015607")
      )
      (libsource (lib "") (part "BUTTON"))
    )
    (comp (ref "S3")
      (value "LEFT")
      (fields
        (field (name "BOM_Manufacturer Part") "BUTTON")
        (field (name "BOM_Supplier Part") "C9900015607")
      )
      (libsource (lib "") (part "BUTTON"))
    )
    (comp (ref "S4")
      (value "V_CUR")
      (fields
        (field (name "BOM_Manufacturer Part") "BUTTON")
        (field (name "BOM_Supplier Part") "C9900015607")
      )
      (libsource (lib "") (part "BUTTON"))
    )
    (comp (ref "S5")
      (value "RIGHT")
      (fields
        (field (name "BOM_Manufacturer Part") "BUTTON")
        (field (name "BOM_Supplier Part") "C9900015607")
      )
      (libsource (lib "") (part "BUTTON"))
    )
    (comp (ref "S6")
      (value "UP")
      (fields
        (field (name "BOM_Manufacturer Part") "BUTTON")
        (field (name "BOM_Supplier Part") "C9900015607")
      )
      (libsource (lib "") (part "BUTTON"))
    )
    (comp (ref "S7")
      (value "OK")
      (fields
        (field (name "BOM_Manufacturer Part") "BUTTON")
        (field (name "BOM_Supplier Part") "C9900015607")
      )
      (libsource (lib "") (part "BUTTON"))
    )
    (comp (ref "S8")
      (value "S_PIC")
      (fields
        (field (name "BOM_Manufacturer Part") "BUTTON")
        (field (name "BOM_Supplier Part") "C9900015607")
      )
      (libsource (lib "") (part "BUTTON"))
    )
    (comp (ref "S9")
      (value "MENU")
      (fields
        (field (name "BOM_Manufacturer Part") "BUTTON")
        (field (name "BOM_Supplier Part") "C9900015607")
      )
      (libsource (lib "") (part "BUTTON"))
    )
    (comp (ref "S10")
      (value "AUTO")
      (fields
        (field (name "BOM_Manufacturer Part") "BUTTON")
        (field (name "BOM_Supplier Part") "C9900015607")
      )
      (libsource (lib "") (part "BUTTON"))
    )
    (comp (ref "S11")
      (value "RUN/STOP")
      (fields
        (field (name "BOM_Manufacturer Part") "BUTTON")
        (field (name "BOM_Supplier Part") "C9900015607")
      )
      (libsource (lib "") (part "BUTTON"))
    )
    (comp (ref "S12")
      (value "H_CUR")
      (fields
        (field (name "BOM_Manufacturer Part") "BUTTON")
        (field (name "BOM_Supplier Part") "C9900015607")
      )
      (libsource (lib "") (part "BUTTON"))
    )
    (comp (ref "S13")
      (value "S_WAV")
      (fields
        (field (name "BOM_Manufacturer Part") "BUTTON")
        (field (name "BOM_Supplier Part") "C9900015607")
      )
      (libsource (lib "") (part "BUTTON"))
    )
    (comp (ref "S14")
      (value "50%")
      (fields
        (field (name "BOM_Manufacturer Part") "BUTTON")
        (field (name "BOM_Supplier Part") "C9900015607")
      )
      (libsource (lib "") (part "BUTTON"))
    )
    (comp (ref "S15")
      (value "CHX")
      (fields
        (field (name "BOM_Manufacturer Part") "BUTTON")
        (field (name "BOM_Supplier Part") "C9900015607")
      )
      (libsource (lib "") (part "BUTTON"))
    )
    (comp (ref "S16")
      (value "EDGE")
      (fields
        (field (name "BOM_Manufacturer Part") "BUTTON")
        (field (name "BOM_Supplier Part") "C9900015607")
      )
      (libsource (lib "") (part "BUTTON"))
    )
    (comp (ref "S17")
      (value "MODE")
      (fields
        (field (name "BOM_Manufacturer Part") "BUTTON")
        (field (name "BOM_Supplier Part") "C9900015607")
      )
      (libsource (lib "") (part "BUTTON"))
    )
    (comp (ref "S18")
      (value "F2")
      (fields
        (field (name "BOM_Manufacturer Part") "BUTTON")
        (field (name "BOM_Supplier Part") "C9900015607")
      )
      (libsource (lib "") (part "BUTTON"))
    )
    (comp (ref "S19")
      (value "F1")
      (fields
        (field (name "BOM_Manufacturer Part") "BUTTON")
        (field (name "BOM_Supplier Part") "C9900015607")
      )
      (libsource (lib "") (part "BUTTON"))
    )
    (comp (ref "S20")
      (value "CH2")
      (fields
        (field (name "BOM_Manufacturer Part") "BUTTON")
        (field (name "BOM_Supplier Part") "C9900015607")
      )
      (libsource (lib "") (part "BUTTON"))
    )
    (comp (ref "S21")
      (value "CH1_CONF")
      (fields
        (field (name "BOM_Manufacturer Part") "BUTTON")
        (field (name "BOM_Supplier Part") "C9900015607")
      )
      (libsource (lib "") (part "BUTTON"))
    )
    (comp (ref "S22")
      (value "CH1")
      (fields
        (field (name "BOM_Manufacturer Part") "BUTTON")
        (field (name "BOM_Supplier Part") "C9900015607")
      )
      (libsource (lib "") (part "BUTTON"))
    )
    (comp (ref "S23")
      (value "SLOW")
      (fields
        (field (name "BOM_Manufacturer Part") "BUTTON")
        (field (name "BOM_Supplier Part") "C9900015607")
      )
      (libsource (lib "") (part "BUTTON"))
    )
    (comp (ref "S24")
      (value "ORIG")
      (fields
        (field (name "BOM_Manufacturer Part") "BUTTON")
        (field (name "BOM_Supplier Part") "C9900015607")
      )
      (libsource (lib "") (part "BUTTON"))
    )
    (comp (ref "S25")
      (value "CH2_CONF")
      (fields
        (field (name "BOM_Manufacturer Part") "BUTTON")
        (field (name "BOM_Supplier Part") "C9900015607")
      )
      (libsource (lib "") (part "BUTTON"))
    )
    (comp (ref "S26")
      (value "F6")
      (fields
        (field (name "BOM_Manufacturer Part") "BUTTON")
        (field (name "BOM_Supplier Part") "C9900015607")
      )
      (libsource (lib "") (part "BUTTON"))
    )
    (comp (ref "S27")
      (value "F5")
      (fields
        (field (name "BOM_Manufacturer Part") "BUTTON")
        (field (name "BOM_Supplier Part") "C9900015607")
      )
      (libsource (lib "") (part "BUTTON"))
    )
    (comp (ref "S28")
      (value "F4")
      (fields
        (field (name "BOM_Manufacturer Part") "BUTTON")
        (field (name "BOM_Supplier Part") "C9900015607")
      )
      (libsource (lib "") (part "BUTTON"))
    )
    (comp (ref "S29")
      (value "F3")
      (fields
        (field (name "BOM_Manufacturer Part") "BUTTON")
        (field (name "BOM_Supplier Part") "C9900015607")
      )
      (libsource (lib "") (part "BUTTON"))
    )
    (comp (ref "S30")
      (value "NEXT")
      (fields
        (field (name "BOM_Manufacturer Part") "BUTTON")
        (field (name "BOM_Supplier Part") "C9900015607")
      )
      (libsource (lib "") (part "BUTTON"))
    )
    (comp (ref "S31")
      (value "GEN")
      (fields
        (field (name "BOM_Manufacturer Part") "BUTTON")
        (field (name "BOM_Supplier Part") "C9900015607")
      )
      (libsource (lib "") (part "BUTTON"))
    )
    (comp (ref "S32")
      (value "SEL")
      (fields
        (field (name "BOM_Manufacturer Part") "BUTTON")
        (field (name "BOM_Supplier Part") "C9900015607")
      )
      (libsource (lib "") (part "BUTTON"))
    )
    (comp (ref "S33")
      (value "SEL_ALL")
      (fields
        (field (name "BOM_Manufacturer Part") "BUTTON")
        (field (name "BOM_Supplier Part") "C9900015607")
      )
      (libsource (lib "") (part "BUTTON"))
    )
    (comp (ref "S34")
      (value "DEL")
      (fields
        (field (name "BOM_Manufacturer Part") "BUTTON")
        (field (name "BOM_Supplier Part") "C9900015607")
      )
      (libsource (lib "") (part "BUTTON"))
    )
    (comp (ref "S35")
      (value "LAST")
      (fields
        (field (name "BOM_Manufacturer Part") "BUTTON")
        (field (name "BOM_Supplier Part") "C9900015607")
      )
      (libsource (lib "") (part "BUTTON"))
    )
    (comp (ref "SW1") (value "SELECT") (libsource (lib "") (part "Rotary_Encoder")))
    (comp (ref "SW2") (value "CH1 POS") (libsource (lib "") (part "Rotary_Encoder")))
    (comp (ref "SW3") (value "CH2 POS") (libsource (lib "") (part "Rotary_Encoder")))
    (comp (ref "SW4") (value "TRG POS") (libsource (lib "") (part "Rotary_Encoder")))
    (comp (ref "SW5") (value "TRG LVL") (libsource (lib "") (part "Rotary_Encoder")))
    (comp (ref "SW6") (value "TRG RNG") (libsource (lib "") (part "Rotary_Encoder")))
    (comp (ref "SW7") (value "CH2 RNG") (libsource (lib "") (part "Rotary_Encoder")))
    (comp (ref "SW8") (value "CH1 RNG") (libsource (lib "") (part "Rotary_Encoder")))
    (comp (ref "U22")
      (value "GD32E230C8T6")
      (fields (field (name "BOM_Supplier Part") "C380535"))
      (libsource (lib "") (part "GD32E230C8T6"))
    )
  )
  (nets
    (net (code "1") (name "-6V3") (class "Default")
      (node (ref "C93") (pin "1") (pinfunction "1_1") (pintype "input"))
      (node (ref "C94") (pin "1") (pinfunction "1_1") (pintype "input"))
      (node (ref "D9") (pin "1") (pinfunction "K_1") (pintype "unspecified"))
      (node (ref "P3") (pin "42") (pinfunction "42_42") (pintype "unspecified"))
      (node (ref "R58") (pin "2") (pinfunction "2_2") (pintype "unspecified"))
    )
    (net (code "2") (name "1V2") (class "Default")
      (node (ref "C11") (pin "1") (pinfunction "1_1") (pintype "input"))
      (node (ref "C138") (pin "1") (pinfunction "1_1") (pintype "input"))
      (node (ref "C139") (pin "1") (pinfunction "1_1") (pintype "input"))
      (node (ref "C140") (pin "1") (pinfunction "1_1") (pintype "input"))
      (node (ref "C33") (pin "1") (pinfunction "1_1") (pintype "input"))
      (node (ref "C34") (pin "1") (pinfunction "1_1") (pintype "input"))
      (node (ref "C35") (pin "1") (pinfunction "1_1") (pintype "input"))
      (node (ref "C4") (pin "1") (pinfunction "1_1") (pintype "input"))
      (node (ref "C48") (pin "1") (pinfunction "1_1") (pintype "input"))
      (node (ref "C49") (pin "1") (pinfunction "1_1") (pintype "input"))
      (node (ref "C50") (pin "1") (pinfunction "1_1") (pintype "input"))
      (node (ref "C53") (pin "1") (pinfunction "1_1") (pintype "input"))
      (node (ref "C74") (pin "1") (pinfunction "1_1") (pintype "input"))
      (node (ref "C75") (pin "1") (pinfunction "1_1") (pintype "input"))
      (node (ref "C77") (pin "1") (pinfunction "1_1") (pintype "input"))
      (node (ref "C8") (pin "1") (pinfunction "1_1") (pintype "input"))
      (node (ref "C9") (pin "1") (pinfunction "1_1") (pintype "input"))
      (node (ref "L1") (pin "1") (pinfunction "1_1") (pintype "unspecified"))
      (node (ref "L4") (pin "1") (pinfunction "1_1") (pintype "unspecified"))
      (node (ref "U1") (pin "22") (pinfunction "VDD-CORE_22") (pintype "unspecified"))
      (node (ref "U1") (pin "35") (pinfunction "VDD-CORE_35") (pintype "unspecified"))
      (node (ref "U1") (pin "71") (pinfunction "VDD-CORE_71") (pintype "unspecified"))
      (node (ref "U10") (pin "2") (pinfunction "VOUT_2") (pintype "unspecified"))
      (node (ref "U10") (pin "4") (pinfunction "VOUT_4") (pintype "unspecified"))
      (node (ref "U3") (pin "102") (pinfunction "VCCINT_102") (pintype "input"))
      (node (ref "U3") (pin "116") (pinfunction "VCCINT_116") (pintype "input"))
      (node (ref "U3") (pin "134") (pinfunction "VCCINT_134") (pintype "input"))
      (node (ref "U3") (pin "29") (pinfunction "VCCINT_29") (pintype "input"))
      (node (ref "U3") (pin "45") (pinfunction "VCCINT_45") (pintype "input"))
      (node (ref "U3") (pin "5") (pinfunction "VCCINT_5") (pintype "input"))
      (node (ref "U3") (pin "61") (pinfunction "VCCINT_61") (pintype "input"))
      (node (ref "U3") (pin "78") (pinfunction "VCCINT_78") (pintype "input"))
    )
    (net (code "3") (name "2V5") (class "Default")
      (node (ref "C1") (pin "1") (pinfunction "1_1") (pintype "input"))
      (node (ref "C137") (pin "1") (pinfunction "1_1") (pintype "input"))
      (node (ref "C42") (pin "1") (pinfunction "1_1") (pintype "input"))
      (node (ref "C43") (pin "1") (pinfunction "1_1") (pintype "input"))
      (node (ref "C44") (pin "1") (pinfunction "1_1") (pintype "input"))
      (node (ref "C5") (pin "1") (pinfunction "1_1") (pintype "input"))
      (node (ref "C6") (pin "2") (pinfunction "2_2") (pintype "input"))
      (node (ref "C71") (pin "1") (pinfunction "1_1") (pintype "input"))
      (node (ref "C72") (pin "1") (pinfunction "1_1") (pintype "input"))
      (node (ref "C73") (pin "2") (pinfunction "2_2") (pintype "input"))
      (node (ref "J5") (pin "4") (pinfunction "4_4") (pintype "unspecified"))
      (node (ref "R10") (pin "1") (pinfunction "1_1") (pintype "unspecified"))
      (node (ref "R28") (pin "2") (pinfunction "2_2") (pintype "unspecified"))
      (node (ref "R81") (pin "1") (pinfunction "1_1") (pintype "unspecified"))
      (node (ref "R9") (pin "1") (pinfunction "1_1") (pintype "unspecified"))
      (node (ref "U1") (pin "30") (pinfunction "VCC-DRAM_30") (pintype "unspecified"))
      (node (ref "U1") (pin "31") (pinfunction "VCC-DRAM_31") (pintype "unspecified"))
      (node (ref "U1") (pin "32") (pinfunction "VCC-DRAM_32") (pintype "unspecified"))
      (node (ref "U1") (pin "34") (pinfunction "VCC-DRAM_34") (pintype "unspecified"))
      (node (ref "U1") (pin "36") (pinfunction "VCC-DRAM_36") (pintype "unspecified"))
      (node (ref "U3") (pin "107") (pinfunction "VCCA2_107") (pintype "input"))
      (node (ref "U3") (pin "35") (pinfunction "VCCA1_35") (pintype "input"))
      (node (ref "U3") (pin "96") (pinfunction "MSEL1_96") (pintype "input"))
      (node (ref "U6") (pin "2") (pinfunction "VOUT_2") (pintype "unspecified"))
      (node (ref "U6") (pin "4") (pinfunction "VOUT_4") (pintype "unspecified"))
    )
    (net (code "4") (name "3V") (class "Default")
      (node (ref "C47") (pin "1") (pinfunction "1_1") (pintype "input"))
      (node (ref "C54") (pin "1") (pinfunction "1_1") (pintype "input"))
      (node (ref "U1") (pin "80") (pinfunction "AVCC_80") (pintype "unspecified"))
      (node (ref "U12") (pin "2") (pinfunction "Vout_2") (pintype "output"))
    )
    (net (code "5") (name "3V3") (class "Default")
      (node (ref "C36") (pin "1") (pinfunction "1_1") (pintype "input"))
      (node (ref "C37") (pin "1") (pinfunction "1_1") (pintype "input"))
      (node (ref "C38") (pin "1") (pinfunction "1_1") (pintype "input"))
      (node (ref "C39") (pin "1") (pinfunction "1_1") (pintype "input"))
      (node (ref "C40") (pin "1") (pinfunction "1_1") (pintype "input"))
      (node (ref "C58") (pin "1") (pinfunction "1_1") (pintype "input"))
      (node (ref "C62") (pin "1") (pinfunction "1_1") (pintype "input"))
      (node (ref "C63") (pin "1") (pinfunction "1_1") (pintype "input"))
      (node (ref "C64") (pin "1") (pinfunction "1_1") (pintype "input"))
      (node (ref "C76") (pin "1") (pinfunction "1_1") (pintype "input"))
      (node (ref "D12") (pin "1") (pinfunction "1_1") (pintype "unspecified"))
      (node (ref "D14") (pin "1") (pinfunction "1_1") (pintype "unspecified"))
      (node (ref "D16") (pin "2") (pinfunction "2_2") (pintype "unspecified"))
      (node (ref "D3") (pin "2") (pinfunction "2_2") (pintype "unspecified"))
      (node (ref "P2") (pin "4") (pinfunction "VDD_4") (pintype "unspecified"))
      (node (ref "P3") (pin "39") (pinfunction "39_39") (pintype "unspecified"))
      (node (ref "P3") (pin "44") (pinfunction "44_44") (pintype "unspecified"))
      (node (ref "P3") (pin "7") (pinfunction "7_7") (pintype "unspecified"))
      (node (ref "Q1") (pin "2") (pinfunction "E_2") (pintype "input"))
      (node (ref "Q2") (pin "2") (pinfunction "E_2") (pintype "input"))
      (node (ref "Q3") (pin "2") (pinfunction "E_2") (pintype "input"))
      (node (ref "Q4") (pin "2") (pinfunction "E_2") (pintype "input"))
      (node (ref "Q5") (pin "2") (pinfunction "E_2") (pintype "input"))
      (node (ref "Q6") (pin "2") (pinfunction "E_2") (pintype "input"))
      (node (ref "R30") (pin "2") (pinfunction "2_2") (pintype "unspecified"))
      (node (ref "R36") (pin "2") (pinfunction "2_2") (pintype "unspecified"))
      (node (ref "R37") (pin "2") (pinfunction "2_2") (pintype "unspecified"))
      (node (ref "R38") (pin "2") (pinfunction "2_2") (pintype "unspecified"))
      (node (ref "R39") (pin "2") (pinfunction "2_2") (pintype "unspecified"))
      (node (ref "R40") (pin "2") (pinfunction "2_2") (pintype "unspecified"))
      (node (ref "R41") (pin "2") (pinfunction "2_2") (pintype "unspecified"))
      (node (ref "R42") (pin "2") (pinfunction "2_2") (pintype "unspecified"))
      (node (ref "R43") (pin "2") (pinfunction "2_2") (pintype "unspecified"))
      (node (ref "R51") (pin "1") (pinfunction "1_1") (pintype "unspecified"))
      (node (ref "U1") (pin "20") (pinfunction "VCC-IO_20") (pintype "unspecified"))
      (node (ref "U1") (pin "5") (pinfunction "VCC-IO_5") (pintype "unspecified"))
      (node (ref "U1") (pin "50") (pinfunction "VCC-IO_50") (pintype "unspecified"))
      (node (ref "U1") (pin "67") (pinfunction "UVCC_67") (pintype "unspecified"))
      (node (ref "U12") (pin "3") (pinfunction "Vin_3") (pintype "unspecified"))
      (node (ref "U9") (pin "3") (pinfunction "VOUT_3") (pintype "unspecified"))
    )
    (net (code "6") (name "3V3_A") (class "Default")
      (node (ref "C10") (pin "1") (pinfunction "1_1") (pintype "input"))
      (node (ref "C113") (pin "2") (pinfunction "2_2") (pintype "input"))
      (node (ref "C119") (pin "2") (pinfunction "2_2") (pintype "input"))
      (node (ref "C12") (pin "1") (pinfunction "1_1") (pintype "input"))
      (node (ref "C14") (pin "1") (pinfunction "1_1") (pintype "input"))
      (node (ref "C144") (pin "1") (pinfunction "1_1") (pintype "input"))
      (node (ref "C145") (pin "1") (pinfunction "1_1") (pintype "input"))
      (node (ref "C146") (pin "1") (pinfunction "1_1") (pintype "input"))
      (node (ref "C15") (pin "1") (pinfunction "1_1") (pintype "input"))
      (node (ref "C16") (pin "1") (pinfunction "1_1") (pintype "input"))
      (node (ref "C17") (pin "1") (pinfunction "1_1") (pintype "input"))
      (node (ref "C18") (pin "1") (pinfunction "1_1") (pintype "input"))
      (node (ref "C19") (pin "1") (pinfunction "1_1") (pintype "input"))
      (node (ref "C20") (pin "1") (pinfunction "1_1") (pintype "input"))
      (node (ref "C21") (pin "1") (pinfunction "1_1") (pintype "input"))
      (node (ref "C22") (pin "1") (pinfunction "1_1") (pintype "input"))
      (node (ref "C7") (pin "1") (pinfunction "1_1") (pintype "input"))
      (node (ref "C78") (pin "1") (pinfunction "1_1") (pintype "input"))
      (node (ref "C79") (pin "1") (pinfunction "1_1") (pintype "input"))
      (node (ref "C80") (pin "1") (pinfunction "1_1") (pintype "input"))
      (node (ref "D1") (pin "2") (pinfunction "2_2") (pintype "unspecified"))
      (node (ref "D2") (pin "2") (pinfunction "2_2") (pintype "unspecified"))
      (node (ref "R11") (pin "1") (pinfunction "1_1") (pintype "unspecified"))
      (node (ref "R12") (pin "1") (pinfunction "1_1") (pintype "unspecified"))
      (node (ref "R49") (pin "2") (pinfunction "2_2") (pintype "unspecified"))
      (node (ref "R5") (pin "2") (pinfunction "2_2") (pintype "unspecified"))
      (node (ref "R50") (pin "2") (pinfunction "2_2") (pintype "unspecified"))
      (node (ref "R8") (pin "1") (pinfunction "1_1") (pintype "unspecified"))
      (node (ref "U11") (pin "5") (pinfunction "OUT_5") (pintype "unspecified"))
      (node (ref "U13") (pin "1") (pinfunction "VDD_1") (pintype "unspecified"))
      (node (ref "U17") (pin "5") (pinfunction "+V_5") (pintype "passive"))
      (node (ref "U20") (pin "5") (pinfunction "+V_5") (pintype "passive"))
      (node (ref "U3") (pin "117") (pinfunction "VCCIO7_117") (pintype "input"))
      (node (ref "U3") (pin "122") (pinfunction "VCCIO7_122") (pintype "input"))
      (node (ref "U3") (pin "130") (pinfunction "VCCIO8_130") (pintype "input"))
      (node (ref "U3") (pin "139") (pinfunction "VCCIO8_139") (pintype "input"))
      (node (ref "U3") (pin "17") (pinfunction "VCCIO1_17") (pintype "input"))
      (node (ref "U3") (pin "26") (pinfunction "VCCIO2_26") (pintype "input"))
      (node (ref "U3") (pin "40") (pinfunction "VCCIO3_40") (pintype "input"))
      (node (ref "U3") (pin "47") (pinfunction "VCCIO3_47") (pintype "input"))
      (node (ref "U3") (pin "56") (pinfunction "VCCIO4_56") (pintype "input"))
      (node (ref "U3") (pin "62") (pinfunction "VCCIO4_62") (pintype "input"))
      (node (ref "U3") (pin "81") (pinfunction "VCCIO5_81") (pintype "input"))
      (node (ref "U3") (pin "93") (pinfunction "VCCIO6_93") (pintype "input"))
      (node (ref "U7") (pin "13") (pinfunction "VD_13") (pintype "passive"))
      (node (ref "U7") (pin "15") (pinfunction "VDD_15") (pintype "passive"))
      (node (ref "U7") (pin "28") (pinfunction "VDD_28") (pintype "passive"))
      (node (ref "U7") (pin "30") (pinfunction "VD_30") (pintype "passive"))
      (node (ref "U7") (pin "31") (pinfunction "VD_31") (pintype "passive"))
      (node (ref "U7") (pin "33") (pinfunction "VDD_33") (pintype "passive"))
      (node (ref "U7") (pin "46") (pinfunction "VDD_46") (pintype "passive"))
      (node (ref "U7") (pin "48") (pinfunction "VD_48") (pintype "passive"))
      (node (ref "U7") (pin "8") (pinfunction "S1_8") (pintype "unspecified"))
      (node (ref "U7") (pin "9") (pinfunction "S2_9") (pintype "unspecified"))
      (node (ref "U8") (pin "13") (pinfunction "VD_13") (pintype "passive"))
      (node (ref "U8") (pin "15") (pinfunction "VDD_15") (pintype "passive"))
      (node (ref "U8") (pin "28") (pinfunction "VDD_28") (pintype "passive"))
      (node (ref "U8") (pin "30") (pinfunction "VD_30") (pintype "passive"))
      (node (ref "U8") (pin "31") (pinfunction "VD_31") (pintype "passive"))
      (node (ref "U8") (pin "33") (pinfunction "VDD_33") (pintype "passive"))
      (node (ref "U8") (pin "46") (pinfunction "VDD_46") (pintype "passive"))
      (node (ref "U8") (pin "48") (pinfunction "VD_48") (pintype "passive"))
      (node (ref "U8") (pin "8") (pinfunction "S1_8") (pintype "unspecified"))
      (node (ref "U8") (pin "9") (pinfunction "S2_9") (pintype "unspecified"))
    )
    (net (code "7") (name "3V3_CPU") (class "Default")
      (node (ref "C120") (pin "1") (pinfunction "1_1") (pintype "input"))
      (node (ref "C131") (pin "1") (pinfunction "1_1") (pintype "input"))
      (node (ref "C132") (pin "1") (pinfunction "1_1") (pintype "input"))
      (node (ref "C151") (pin "1") (pinfunction "1_1") (pintype "input"))
      (node (ref "D16") (pin "1") (pinfunction "1_1") (pintype "unspecified"))
      (node (ref "R101") (pin "2") (pinfunction "2_2") (pintype "unspecified"))
      (node (ref "R102") (pin "2") (pinfunction "2_2") (pintype "unspecified"))
      (node (ref "R105") (pin "2") (pinfunction "2_2") (pintype "unspecified"))
      (node (ref "R110") (pin "2") (pinfunction "2_2") (pintype "unspecified"))
      (node (ref "R113") (pin "2") (pinfunction "2_2") (pintype "unspecified"))
      (node (ref "R114") (pin "2") (pinfunction "2_2") (pintype "unspecified"))
      (node (ref "R117") (pin "2") (pinfunction "2_2") (pintype "unspecified"))
      (node (ref "R122") (pin "2") (pinfunction "2_2") (pintype "unspecified"))
      (node (ref "R125") (pin "2") (pinfunction "2_2") (pintype "unspecified"))
      (node (ref "R128") (pin "2") (pinfunction "2_2") (pintype "unspecified"))
      (node (ref "R131") (pin "2") (pinfunction "2_2") (pintype "unspecified"))
      (node (ref "R132") (pin "2") (pinfunction "2_2") (pintype "unspecified"))
      (node (ref "R135") (pin "2") (pinfunction "2_2") (pintype "unspecified"))
      (node (ref "R138") (pin "2") (pinfunction "2_2") (pintype "unspecified"))
      (node (ref "R141") (pin "2") (pinfunction "2_2") (pintype "unspecified"))
      (node (ref "R146") (pin "2") (pinfunction "2_2") (pintype "unspecified"))
      (node (ref "R149") (pin "2") (pinfunction "2_2") (pintype "unspecified"))
      (node (ref "R150") (pin "1") (pinfunction "1_1") (pintype "unspecified"))
      (node (ref "R151") (pin "1") (pinfunction "1_1") (pintype "unspecified"))
      (node (ref "R152") (pin "1") (pinfunction "1_1") (pintype "unspecified"))
      (node (ref "R153") (pin "1") (pinfunction "1_1") (pintype "unspecified"))
      (node (ref "R154") (pin "1") (pinfunction "1_1") (pintype "unspecified"))
      (node (ref "R155") (pin "1") (pinfunction "1_1") (pintype "unspecified"))
      (node (ref "R156") (pin "2") (pinfunction "2_2") (pintype "unspecified"))
      (node (ref "R157") (pin "2") (pinfunction "2_2") (pintype "unspecified"))
      (node (ref "R158") (pin "2") (pinfunction "2_2") (pintype "unspecified"))
      (node (ref "R159") (pin "2") (pinfunction "2_2") (pintype "unspecified"))
      (node (ref "R160") (pin "2") (pinfunction "2_2") (pintype "unspecified"))
      (node (ref "R161") (pin "2") (pinfunction "2_2") (pintype "unspecified"))
      (node (ref "U22") (pin "1") (pinfunction "VDD_1") (pintype "unspecified"))
      (node (ref "U22") (pin "24") (pinfunction "VDD_24") (pintype "unspecified"))
      (node (ref "U22") (pin "48") (pinfunction "VDD_48") (pintype "unspecified"))
      (node (ref "U22") (pin "9") (pinfunction "VDDA_9") (pintype "unspecified"))
    )
    (net (code "8") (name "5V") (class "Default")
      (node (ref "C141") (pin "1") (pinfunction "1_1") (pintype "input"))
      (node (ref "C142") (pin "1") (pinfunction "1_1") (pintype "input"))
      (node (ref "C143") (pin "1") (pinfunction "1_1") (pintype "input"))
      (node (ref "C147") (pin "1") (pinfunction "1_1") (pintype "input"))
      (node (ref "C148") (pin "1") (pinfunction "1_1") (pintype "input"))
      (node (ref "C60") (pin "1") (pinfunction "1_1") (pintype "input"))
      (node (ref "C61") (pin "1") (pinfunction "1_1") (pintype "input"))
      (node (ref "C65") (pin "1") (pinfunction "1_1") (pintype "input"))
      (node (ref "C66") (pin "1") (pinfunction "1_1") (pintype "input"))
      (node (ref "C67") (pin "1") (pinfunction "1_1") (pintype "input"))
      (node (ref "C68") (pin "1") (pinfunction "1_1") (pintype "input"))
      (node (ref "C69") (pin "1") (pinfunction "1_1") (pintype "input"))
      (node (ref "C70") (pin "1") (pinfunction "1_1") (pintype "input"))
      (node (ref "C82") (pin "1") (pinfunction "1_1") (pintype "input"))
      (node (ref "L5") (pin "1") (pinfunction "1_1") (pintype "unspecified"))
      (node (ref "Q8") (pin "2") (pinfunction "S_2") (pintype "unspecified"))
      (node (ref "U10") (pin "3") (pinfunction "VIN_3") (pintype "unspecified"))
      (node (ref "U11") (pin "1") (pinfunction "IN_1") (pintype "unspecified"))
      (node (ref "U11") (pin "3") (pinfunction "EN_3") (pintype "unspecified"))
      (node (ref "U14") (pin "5") (pinfunction "+V_5") (pintype "passive"))
      (node (ref "U15") (pin "4") (pinfunction "EN_4") (pintype "unspecified"))
      (node (ref "U15") (pin "5") (pinfunction "VIN_5") (pintype "unspecified"))
      (node (ref "U6") (pin "3") (pinfunction "VIN_3") (pintype "unspecified"))
      (node (ref "U9") (pin "2") (pinfunction "VIN_2") (pintype "unspecified"))
      (node (ref "U9") (pin "4") (pinfunction "VIN_4") (pintype "unspecified"))
    )
    (net (code "9") (name "5V_IN") (class "Default")
      (node (ref "C95") (pin "1") (pinfunction "1_1") (pintype "input"))
      (node (ref "C96") (pin "1") (pinfunction "1_1") (pintype "input"))
      (node (ref "CON1") (pin "1") (pinfunction "1_1") (pintype "bidirectional"))
      (node (ref "L6") (pin "1") (pinfunction "1_1") (pintype "unspecified"))
      (node (ref "Q8") (pin "3") (pinfunction "D_3") (pintype "unspecified"))
      (node (ref "R53") (pin "2") (pinfunction "2_2") (pintype "unspecified"))
      (node (ref "U16") (pin "6") (pinfunction "IN_6") (pintype "unspecified"))
    )
    (net (code "10") (name "10V3") (class "Default")
      (node (ref "C90") (pin "1") (pinfunction "1_1") (pintype "input"))
      (node (ref "C91") (pin "1") (pinfunction "1_1") (pintype "input"))
      (node (ref "P3") (pin "43") (pinfunction "43_43") (pintype "unspecified"))
      (node (ref "R44") (pin "2") (pinfunction "2_2") (pintype "unspecified"))
      (node (ref "ZD1") (pin "2") (pinfunction "A_2") (pintype "unspecified"))
    )
    (net (code "11") (name "15V8") (class "Default")
      (node (ref "C87") (pin "1") (pinfunction "1_1") (pintype "input"))
      (node (ref "C88") (pin "1") (pinfunction "1_1") (pintype "input"))
      (node (ref "D6") (pin "2") (pinfunction "K_2") (pintype "unspecified"))
      (node (ref "P3") (pin "41") (pinfunction "41_41") (pintype "unspecified"))
      (node (ref "R56") (pin "2") (pinfunction "2_2") (pintype "unspecified"))
      (node (ref "ZD1") (pin "1") (pinfunction "K_1") (pintype "unspecified"))
    )
    (net (code "12") (name "ADC1_D0A") (class "Default")
      (node (ref "U3") (pin "103") (pinfunction "(CLKUSR),DIFFIO_R3p,IO_103") (pintype "input"))
      (node (ref "U8") (pin "37") (pinfunction "D0A_37") (pintype "unspecified"))
    )
    (net (code "13") (name "ADC1_D0B") (class "Default")
      (node (ref "U3") (pin "110") (pinfunction "(DQS0T/CQ1T,DPCLK6),DIFFIO_T20p,IO_110") (pintype "input"))
      (node (ref "U8") (pin "24") (pinfunction "D0B_24") (pintype "unspecified"))
    )
    (net (code "14") (name "ADC1_D1A") (class "Default")
      (node (ref "U3") (pin "101") (pinfunction "(nCEO),DIFFIO_R3n,IO_101") (pintype "input"))
      (node (ref "U8") (pin "38") (pinfunction "D1A_38") (pintype "unspecified"))
    )
    (net (code "15") (name "ADC1_D1B") (class "Default")
      (node (ref "U3") (pin "111") (pinfunction "DIFFIO_T19p,IO_111") (pintype "input"))
      (node (ref "U8") (pin "23") (pinfunction "D1B_23") (pintype "unspecified"))
    )
    (net (code "16") (name "ADC1_D2A") (class "Default")
      (node (ref "U3") (pin "100") (pinfunction "IO_100") (pintype "input"))
      (node (ref "U8") (pin "39") (pinfunction "D2A_39") (pintype "unspecified"))
    )
    (net (code "17") (name "ADC1_D2B") (class "Default")
      (node (ref "U3") (pin "112") (pinfunction "PLL2_CLKOUTn,IO_112") (pintype "input"))
      (node (ref "U8") (pin "22") (pinfunction "D2B_22") (pintype "unspecified"))
    )
    (net (code "18") (name "ADC1_D3A") (class "Default")
      (node (ref "U3") (pin "99") (pinfunction "(CRC_ERROR),DIFFIO_R4P,IO_99") (pintype "input"))
      (node (ref "U8") (pin "40") (pinfunction "D3A_40") (pintype "unspecified"))
    )
    (net (code "19") (name "ADC1_D3B") (class "Default")
      (node (ref "U3") (pin "113") (pinfunction "PLL2_CLKOUTp,IO_113") (pintype "input"))
      (node (ref "U8") (pin "21") (pinfunction "D3B_21") (pintype "unspecified"))
    )
    (net (code "20") (name "ADC1_D4A") (class "Default")
      (node (ref "U3") (pin "98") (pinfunction "(INT_DONE),DIFFIO_R4n,IO_98") (pintype "input"))
      (node (ref "U8") (pin "41") (pinfunction "D4A_41") (pintype "unspecified"))
    )
    (net (code "21") (name "ADC1_D4B") (class "Default")
      (node (ref "U3") (pin "114") (pinfunction "(DQ1T),RUP4,IO_114") (pintype "input"))
      (node (ref "U8") (pin "20") (pinfunction "D4B_20") (pintype "unspecified"))
    )
    (net (code "22") (name "ADC1_D5A") (class "Default")
      (node (ref "U3") (pin "91") (pinfunction "CLK4,DIFFCLK_2p_91") (pintype "input"))
      (node (ref "U8") (pin "42") (pinfunction "D5A_42") (pintype "unspecified"))
    )
    (net (code "23") (name "ADC1_D5B") (class "Default")
      (node (ref "U3") (pin "115") (pinfunction "(DQ1T),RDN4,IO_115") (pintype "input"))
      (node (ref "U8") (pin "19") (pinfunction "D5B_19") (pintype "unspecified"))
    )
    (net (code "24") (name "ADC1_D6A") (class "Default")
      (node (ref "U3") (pin "90") (pinfunction "CLK5,DIFFCLK_2n_90") (pintype "input"))
      (node (ref "U8") (pin "43") (pinfunction "D6A_43") (pintype "unspecified"))
    )
    (net (code "25") (name "ADC1_D6B") (class "Default")
      (node (ref "U3") (pin "119") (pinfunction "VREFB7N0,IO_119") (pintype "input"))
      (node (ref "U8") (pin "18") (pinfunction "D6B_18") (pintype "unspecified"))
    )
    (net (code "26") (name "ADC1_D7A") (class "Default")
      (node (ref "U3") (pin "89") (pinfunction "CLK6,DIFFCLK_3p_89") (pintype "input"))
      (node (ref "U8") (pin "44") (pinfunction "D7A_(MSB)_44") (pintype "unspecified"))
    )
    (net (code "27") (name "ADC1_D7B") (class "Default")
      (node (ref "U3") (pin "120") (pinfunction "(DQ1T),DIFFIO_T16n,IO_120") (pintype "input"))
      (node (ref "U8") (pin "17") (pinfunction "D7B_(MSB)_17") (pintype "unspecified"))
    )
    (net (code "28") (name "ADC1_ENCA") (class "Default")
      (node (ref "U3") (pin "88") (pinfunction "CLK7,DIFFCLK_3n_88") (pintype "input"))
      (node (ref "U8") (pin "47") (pinfunction "ENCA_47") (pintype "unspecified"))
    )
    (net (code "29") (name "ADC1_ENCB") (class "Default")
      (node (ref "U3") (pin "121") (pinfunction "DIFFIO_T16p,IO_121") (pintype "input"))
      (node (ref "U8") (pin "14") (pinfunction "ENCB_14") (pintype "unspecified"))
    )
    (net (code "30") (name "ADC1_OFFSET") (class "Default")
      (node (ref "R26") (pin "1") (pinfunction "1_1") (pintype "unspecified"))
      (node (ref "U3") (pin "87") (pinfunction "(DEV_CLRn),DIFFIO_R7p,IO_87") (pintype "input"))
    )
    (net (code "31") (name "ADC2_D0A") (class "Default")
      (node (ref "U3") (pin "72") (pinfunction "DIFFIO_B22p,IO_72") (pintype "input"))
      (node (ref "U7") (pin "37") (pinfunction "D0A_37") (pintype "unspecified"))
    )
    (net (code "32") (name "ADC2_D0B") (class "Default")
      (node (ref "U3") (pin "73") (pinfunction "IO_73") (pintype "input"))
      (node (ref "U7") (pin "24") (pinfunction "D0B_24") (pintype "unspecified"))
    )
    (net (code "33") (name "ADC2_D1A") (class "Default")
      (node (ref "U3") (pin "71") (pinfunction "DIFFIO_B21n,IO_71") (pintype "input"))
      (node (ref "U7") (pin "38") (pinfunction "D1A_38") (pintype "unspecified"))
    )
    (net (code "34") (name "ADC2_D1B") (class "Default")
      (node (ref "U3") (pin "74") (pinfunction "IO_74") (pintype "input"))
      (node (ref "U7") (pin "23") (pinfunction "D1B_23") (pintype "unspecified"))
    )
    (net (code "35") (name "ADC2_D2A") (class "Default")
      (node (ref "U3") (pin "70") (pinfunction "DIFFIO_B21p,IO_70") (pintype "input"))
      (node (ref "U7") (pin "39") (pinfunction "D2A_39") (pintype "unspecified"))
    )
    (net (code "36") (name "ADC2_D2B") (class "Default")
      (node (ref "U3") (pin "75") (pinfunction "IO_75") (pintype "input"))
      (node (ref "U7") (pin "22") (pinfunction "D2B_22") (pintype "unspecified"))
    )
    (net (code "37") (name "ADC2_D3A") (class "Default")
      (node (ref "U3") (pin "69") (pinfunction "IO_69") (pintype "input"))
      (node (ref "U7") (pin "40") (pinfunction "D3A_40") (pintype "unspecified"))
    )
    (net (code "38") (name "ADC2_D3B") (class "Default")
      (node (ref "U3") (pin "76") (pinfunction "RUP3,IO_76") (pintype "input"))
      (node (ref "U7") (pin "21") (pinfunction "D3B_21") (pintype "unspecified"))
    )
    (net (code "39") (name "ADC2_D4A") (class "Default")
      (node (ref "U3") (pin "68") (pinfunction "(DQS0B/CQ1B,DPCLK3),DIFFIO_B20n,IO_68") (pintype "input"))
      (node (ref "U7") (pin "41") (pinfunction "D4A_41") (pintype "unspecified"))
    )
    (net (code "40") (name "ADC2_D4B") (class "Default")
      (node (ref "U3") (pin "77") (pinfunction "RDN3,IO_77") (pintype "input"))
      (node (ref "U7") (pin "20") (pinfunction "D4B_20") (pintype "unspecified"))
    )
    (net (code "41") (name "ADC2_D5A") (class "Default")
      (node (ref "U3") (pin "67") (pinfunction "(DQ1B),RDN2,IO_67") (pintype "input"))
      (node (ref "U7") (pin "42") (pinfunction "D5A_42") (pintype "unspecified"))
    )
    (net (code "42") (name "ADC2_D5B") (class "Default")
      (node (ref "U3") (pin "80") (pinfunction "VREFB5N0,IO_80") (pintype "input"))
      (node (ref "U7") (pin "19") (pinfunction "D5B_19") (pintype "unspecified"))
    )
    (net (code "43") (name "ADC2_D6A") (class "Default")
      (node (ref "U3") (pin "66") (pinfunction "(DQ1B),RUP2,IO_66") (pintype "input"))
      (node (ref "U7") (pin "43") (pinfunction "D6A_43") (pintype "unspecified"))
    )
    (net (code "44") (name "ADC2_D6B") (class "Default")
      (node (ref "U3") (pin "83") (pinfunction "IO_83") (pintype "input"))
      (node (ref "U7") (pin "18") (pinfunction "D6B_18") (pintype "unspecified"))
    )
    (net (code "45") (name "ADC2_D7A") (class "Default")
      (node (ref "U3") (pin "65") (pinfunction "VREFB4N0,IO_65") (pintype "input"))
      (node (ref "U7") (pin "44") (pinfunction "D7A_(MSB)_44") (pintype "unspecified"))
    )
    (net (code "46") (name "ADC2_D7B") (class "Default")
      (node (ref "U3") (pin "84") (pinfunction "DIFFIO_R8n,IO_84") (pintype "input"))
      (node (ref "U7") (pin "17") (pinfunction "D7B_(MSB)_17") (pintype "unspecified"))
    )
    (net (code "47") (name "ADC2_ENCA") (class "Default")
      (node (ref "U3") (pin "64") (pinfunction "IO_64") (pintype "input"))
      (node (ref "U7") (pin "47") (pinfunction "ENCA_47") (pintype "unspecified"))
    )
    (net (code "48") (name "ADC2_ENCB") (class "Default")
      (node (ref "U3") (pin "85") (pinfunction "(DQS1R/CQ1R#,DPCLK4),DIFFIO_R8p,IO_85") (pintype "input"))
      (node (ref "U7") (pin "14") (pinfunction "ENCB_14") (pintype "unspecified"))
    )
    (net (code "49") (name "ADC2_OFFSET") (class "Default")
      (node (ref "R24") (pin "1") (pinfunction "1_1") (pintype "unspecified"))
      (node (ref "U3") (pin "86") (pinfunction "(DEV_OE),DIFFIO_R7n,IO_86") (pintype "input"))
    )
    (net (code "50") (name "ANALOG1_AC_DC") (class "Default")
      (node (ref "R19") (pin "1") (pinfunction "1_1") (pintype "unspecified"))
      (node (ref "U18") (pin "1") (pinfunction "A_1") (pintype "unspecified"))
    )
    (net (code "51") (name "ANALOG1_ADC_INPUT") (class "Default")
      (node (ref "C114") (pin "1") (pinfunction "1_1") (pintype "input"))
      (node (ref "K1") (pin "4") (pinfunction "4_4") (pintype "input"))
      (node (ref "K1") (pin "5") (pinfunction "5_5") (pintype "input"))
      (node (ref "R23") (pin "1") (pinfunction "1_1") (pintype "unspecified"))
      (node (ref "R69") (pin "2") (pinfunction "2_2") (pintype "unspecified"))
      (node (ref "U17") (pin "1") (pinfunction "OUT_1") (pintype "output"))
    )
    (net (code "52") (name "ANALOG1_RELAIS1") (class "Default")
      (node (ref "Q1") (pin "1") (pinfunction "B_1") (pintype "input"))
      (node (ref "R18") (pin "1") (pinfunction "1_1") (pintype "unspecified"))
    )
    (net (code "53") (name "ANALOG1_RELAIS2") (class "Default")
      (node (ref "Q2") (pin "1") (pinfunction "B_1") (pintype "input"))
      (node (ref "R17") (pin "1") (pinfunction "1_1") (pintype "unspecified"))
    )
    (net (code "54") (name "ANALOG1_RELAIS3") (class "Default")
      (node (ref "Q3") (pin "1") (pinfunction "B_1") (pintype "input"))
      (node (ref "R16") (pin "1") (pinfunction "1_1") (pintype "unspecified"))
    )
    (net (code "55") (name "ANALOG2_AC_DC") (class "Default")
      (node (ref "R20") (pin "1") (pinfunction "1_1") (pintype "unspecified"))
      (node (ref "U19") (pin "1") (pinfunction "A_1") (pintype "unspecified"))
    )
    (net (code "56") (name "ANALOG2_ADC_INPUT") (class "Default")
      (node (ref "C118") (pin "1") (pinfunction "1_1") (pintype "input"))
      (node (ref "K6") (pin "4") (pinfunction "4_4") (pintype "input"))
      (node (ref "K6") (pin "5") (pinfunction "5_5") (pintype "input"))
      (node (ref "R22") (pin "1") (pinfunction "1_1") (pintype "unspecified"))
      (node (ref "R73") (pin "2") (pinfunction "2_2") (pintype "unspecified"))
      (node (ref "U20") (pin "1") (pinfunction "OUT_1") (pintype "output"))
    )
    (net (code "57") (name "ANALOG2_RELAIS1") (class "Default")
      (node (ref "Q6") (pin "1") (pinfunction "B_1") (pintype "input"))
      (node (ref "R13") (pin "1") (pinfunction "1_1") (pintype "unspecified"))
    )
    (net (code "58") (name "ANALOG2_RELAIS2") (class "Default")
      (node (ref "Q5") (pin "1") (pinfunction "B_1") (pintype "input"))
      (node (ref "R14") (pin "1") (pinfunction "1_1") (pintype "unspecified"))
    )
    (net (code "59") (name "ANALOG2_RELAIS3") (class "Default")
      (node (ref "Q4") (pin "1") (pinfunction "B_1") (pintype "input"))
      (node (ref "R15") (pin "1") (pinfunction "1_1") (pintype "unspecified"))
    )
    (net (code "60") (name "Backlight V+") (class "Default")
      (node (ref "C97") (pin "1") (pinfunction "1_1") (pintype "input"))
      (node (ref "C98") (pin "1") (pinfunction "1_1") (pintype "input"))
      (node (ref "D10") (pin "2") (pinfunction "K_2") (pintype "unspecified"))
      (node (ref "P3") (pin "1") (pinfunction "1_1") (pintype "unspecified"))
      (node (ref "P3") (pin "2") (pinfunction "2_2") (pintype "unspecified"))
      (node (ref "U16") (pin "5") (pinfunction "OV_5") (pintype "unspecified"))
    )
    (net (code "61") (name "Backlight V-") (class "Default")
      (node (ref "P3") (pin "3") (pinfunction "3_3") (pintype "unspecified"))
      (node (ref "P3") (pin "4") (pinfunction "4_4") (pintype "unspecified"))
      (node (ref "R60") (pin "2") (pinfunction "2_2") (pintype "unspecified"))
      (node (ref "R61") (pin "2") (pinfunction "2_2") (pintype "unspecified"))
      (node (ref "U16") (pin "3") (pinfunction "FB_3") (pintype "unspecified"))
    )
    (net (code "62") (name "CH1_POS_A") (class "Default")
      (node (ref "C155") (pin "1") (pinfunction "1_1") (pintype "input"))
      (node (ref "R111") (pin "2") (pinfunction "2_2") (pintype "unspecified"))
      (node (ref "R112") (pin "1") (pinfunction "1_1") (pintype "unspecified"))
      (node (ref "U22") (pin "14") (pinfunction "PA4_14") (pintype "unspecified"))
    )
    (net (code "63") (name "CH1_POS_B") (class "Default")
      (node (ref "C154") (pin "1") (pinfunction "1_1") (pintype "input"))
      (node (ref "R108") (pin "2") (pinfunction "2_2") (pintype "unspecified"))
      (node (ref "R109") (pin "1") (pinfunction "1_1") (pintype "unspecified"))
      (node (ref "U22") (pin "15") (pinfunction "PA5_15") (pintype "unspecified"))
    )
    (net (code "64") (name "CH1_RNG_A") (class "Default")
      (node (ref "C167") (pin "1") (pinfunction "1_1") (pintype "input"))
      (node (ref "R147") (pin "2") (pinfunction "2_2") (pintype "unspecified"))
      (node (ref "R148") (pin "1") (pinfunction "1_1") (pintype "unspecified"))
      (node (ref "U22") (pin "13") (pinfunction "PA3_13") (pintype "unspecified"))
    )
    (net (code "65") (name "CH1_RNG_B") (class "Default")
      (node (ref "C166") (pin "1") (pinfunction "1_1") (pintype "input"))
      (node (ref "R144") (pin "2") (pinfunction "2_2") (pintype "unspecified"))
      (node (ref "R145") (pin "1") (pinfunction "1_1") (pintype "unspecified"))
      (node (ref "U22") (pin "16") (pinfunction "PA6_16") (pintype "unspecified"))
    )
    (net (code "66") (name "CH2_POS_A") (class "Default")
      (node (ref "C156") (pin "1") (pinfunction "1_1") (pintype "input"))
      (node (ref "R115") (pin "1") (pinfunction "1_1") (pintype "unspecified"))
      (node (ref "R116") (pin "2") (pinfunction "2_2") (pintype "unspecified"))
      (node (ref "U22") (pin "11") (pinfunction "PA1_11") (pintype "unspecified"))
    )
    (net (code "67") (name "CH2_POS_B") (class "Default")
      (node (ref "C157") (pin "1") (pinfunction "1_1") (pintype "input"))
      (node (ref "R118") (pin "1") (pinfunction "1_1") (pintype "unspecified"))
      (node (ref "R119") (pin "2") (pinfunction "2_2") (pintype "unspecified"))
      (node (ref "U22") (pin "10") (pinfunction "PA0_10") (pintype "unspecified"))
    )
    (net (code "68") (name "CH2_RNG_A") (class "Default")
      (node (ref "C164") (pin "1") (pinfunction "1_1") (pintype "input"))
      (node (ref "R139") (pin "1") (pinfunction "1_1") (pintype "unspecified"))
      (node (ref "R140") (pin "2") (pinfunction "2_2") (pintype "unspecified"))
      (node (ref "U22") (pin "6") (pinfunction "PF1-OSCOUT_6") (pintype "unspecified"))
    )
    (net (code "69") (name "CH2_RNG_B") (class "Default")
      (node (ref "C165") (pin "1") (pinfunction "1_1") (pintype "input"))
      (node (ref "R142") (pin "1") (pinfunction "1_1") (pintype "unspecified"))
      (node (ref "R143") (pin "2") (pinfunction "2_2") (pintype "unspecified"))
      (node (ref "U22") (pin "12") (pinfunction "PA2_12") (pintype "unspecified"))
    )
    (net (code "70") (name "CLOCK_SCL") (class "Default")
      (node (ref "R50") (pin "1") (pinfunction "1_1") (pintype "unspecified"))
      (node (ref "U1") (pin "65") (pinfunction "PA1/TPX2/DA_LRCK/UART1_CTS/SPI1_MOSI_65") (pintype "unspecified"))
      (node (ref "U13") (pin "4") (pinfunction "SCL_4") (pintype "unspecified"))
    )
    (net (code "71") (name "CLOCK_SDA") (class "Default")
      (node (ref "R49") (pin "1") (pinfunction "1_1") (pintype "unspecified"))
      (node (ref "U1") (pin "66") (pinfunction "PA0/TPX1/DA_BCLK/UART1_RTS/SPI1_CS_66") (pintype "unspecified"))
      (node (ref "U13") (pin "5") (pinfunction "SDA_5") (pintype "unspecified"))
    )
    (net (code "72") (name "CONTROL_RX") (class "Default")
      (node (ref "U1") (pin "64") (pinfunction "PA2/TPY1/PWM0/DA_IN/UART1_RX/SPI1_CLK_64") (pintype "unspecified"))
      (node (ref "U22") (pin "30") (pinfunction "PA9_30") (pintype "unspecified"))
    )
    (net (code "73") (name "CONTROL_TX") (class "Default")
      (node (ref "U1") (pin "63") (pinfunction "PA3/TPY2/IR_RX/DA_OUT/UART1_TX/SPI1_MISO_63") (pintype "unspecified"))
      (node (ref "U22") (pin "31") (pinfunction "PA10_31") (pintype "unspecified"))
    )
    (net (code "74") (name "DAC_D0") (class "Default")
      (node (ref "R34") (pin "2") (pinfunction "2_2") (pintype "unspecified"))
      (node (ref "U3") (pin "38") (pinfunction "DIFFIO_B1p,IO_38") (pintype "input"))
    )
    (net (code "75") (name "DAC_D1") (class "Default")
      (node (ref "R52") (pin "2") (pinfunction "2_2") (pintype "unspecified"))
      (node (ref "U3") (pin "39") (pinfunction "DIFFIO_B1n,IO_39") (pintype "input"))
    )
    (net (code "76") (name "DAC_D2") (class "Default")
      (node (ref "R55") (pin "2") (pinfunction "2_2") (pintype "unspecified"))
      (node (ref "U3") (pin "42") (pinfunction "(DQS1B/CQ1B#,DPCLK2),IO_42") (pintype "input"))
    )
    (net (code "77") (name "DAC_D3") (class "Default")
      (node (ref "R84") (pin "2") (pinfunction "2_2") (pintype "unspecified"))
      (node (ref "U3") (pin "43") (pinfunction "PLL1_CLKOUTp,IO_43") (pintype "input"))
    )
    (net (code "78") (name "DAC_D4") (class "Default")
      (node (ref "R86") (pin "2") (pinfunction "2_2") (pintype "unspecified"))
      (node (ref "U3") (pin "44") (pinfunction "PLL1_CLKOUTn,IO_44") (pintype "input"))
    )
    (net (code "79") (name "DAC_D5") (class "Default")
      (node (ref "R88") (pin "2") (pinfunction "2_2") (pintype "unspecified"))
      (node (ref "U3") (pin "46") (pinfunction "VREFB3N0,IO_46") (pintype "input"))
    )
    (net (code "80") (name "DAC_D6") (class "Default")
      (node (ref "R90") (pin "2") (pinfunction "2_2") (pintype "unspecified"))
      (node (ref "U3") (pin "49") (pinfunction "(DQ1B),DIFFIO_B9p,IO_49") (pintype "input"))
    )
    (net (code "81") (name "DAC_D7") (class "Default")
      (node (ref "R92") (pin "2") (pinfunction "2_2") (pintype "unspecified"))
      (node (ref "U3") (pin "50") (pinfunction "(DQ1B),DIFFIO_B9n,IO_50") (pintype "input"))
    )
    (net (code "82") (name "F1C100S_FPGA_CLK") (class "Default")
      (node (ref "U1") (pin "41") (pinfunction "PE8/CSI_D5/UART2_RX/SPI1_MOSI_41") (pintype "unspecified"))
      (node (ref "U3") (pin "1") (pinfunction "IO_1") (pintype "input"))
    )
    (net (code "83") (name "F1C100S_FPGA_DB0") (class "Default")
      (node (ref "U1") (pin "49") (pinfunction "PE0/CSI_HSYNC/LCD_D0/TWI2_SCK/UART0_RX_49") (pintype "unspecified"))
      (node (ref "U3") (pin "135") (pinfunction "(DQ1T),DIFFIO_T8n,IO_135") (pintype "input"))
    )
    (net (code "84") (name "F1C100S_FPGA_DB1") (class "Default")
      (node (ref "U1") (pin "48") (pinfunction "PE1/CSI_VSYNC/LCD_D1/TWI2_SDA/UART0_TX_48") (pintype "unspecified"))
      (node (ref "U3") (pin "136") (pinfunction "VREFB8N0,IO_136") (pintype "input"))
    )
    (net (code "85") (name "F1C100S_FPGA_DB2") (class "Default")
      (node (ref "U1") (pin "47") (pinfunction "PE2/CSI_PCLK/LCD_D8/CLK_OUT_47") (pintype "unspecified"))
      (node (ref "U3") (pin "137") (pinfunction "(DQ1T),(DATA5),IO_137") (pintype "input"))
    )
    (net (code "86") (name "F1C100S_FPGA_DB3") (class "Default")
      (node (ref "U1") (pin "46") (pinfunction "PE3/CSI_D0/LCD_D9/DA_BCLK_46") (pintype "unspecified"))
      (node (ref "U3") (pin "138") (pinfunction "(DATA6),IO_138") (pintype "input"))
    )
    (net (code "87") (name "F1C100S_FPGA_DB4") (class "Default")
      (node (ref "U1") (pin "45") (pinfunction "PE4/CSI_D1/LCD_D16/DA_LRCK_45") (pintype "unspecified"))
      (node (ref "U3") (pin "141") (pinfunction "DIFFIO_T5p,IO_141") (pintype "input"))
    )
    (net (code "88") (name "F1C100S_FPGA_DB5") (class "Default")
      (node (ref "U1") (pin "44") (pinfunction "PE5/CSI_D2/LCD_D17/DA_IN_44") (pintype "unspecified"))
      (node (ref "U3") (pin "142") (pinfunction "(DQS1T/CQ1T#,DPCLK7),DIFFIO_T2p,IO_142") (pintype "input"))
    )
    (net (code "89") (name "F1C100S_FPGA_DB6") (class "Default")
      (node (ref "U1") (pin "43") (pinfunction "PE6/CSI_D3/PWM1/DA_OUT/OWA_OUT_43") (pintype "unspecified"))
      (node (ref "U3") (pin "143") (pinfunction "(DQ1T),DIFFIO_T1n,IO_143") (pintype "input"))
    )
    (net (code "90") (name "F1C100S_FPGA_DB7") (class "Default")
      (node (ref "U1") (pin "42") (pinfunction "PE7/CSI_D4/UART2_TX/SPI1_CS_42") (pintype "unspecified"))
      (node (ref "U3") (pin "144") (pinfunction "(DM1T),DIFFIO_T1p,IO_144") (pintype "input"))
    )
    (net (code "91") (name "F1C100S_FPGA_DCS") (class "Default")
      (node (ref "U1") (pin "39") (pinfunction "PE10/CSI_D7/UART2_CTS/SPI1_MISO_39") (pintype "unspecified"))
      (node (ref "U3") (pin "3") (pinfunction "IO_3") (pintype "input"))
    )
    (net (code "92") (name "F1C100S_FPGA_RWS") (class "Default")
      (node (ref "U1") (pin "40") (pinfunction "PE9/CSI_D6/UART2_RTS/SPI1_CLK_40") (pintype "unspecified"))
      (node (ref "U3") (pin "2") (pinfunction "IO_2") (pintype "input"))
    )
    (net (code "93") (name "FPGA_BACKLIGHT_PWM") (class "Default")
      (node (ref "R59") (pin "2") (pinfunction "2_2") (pintype "unspecified"))
      (node (ref "U16") (pin "4") (pinfunction "EN_4") (pintype "unspecified"))
      (node (ref "U3") (pin "7") (pinfunction "VREFB1N0,IO_7") (pintype "input"))
    )
    (net (code "94") (name "FPGA_Conf_ASDO") (class "Default")
      (node (ref "J2") (pin "6") (pinfunction "6_6") (pintype "input"))
      (node (ref "U3") (pin "6") (pinfunction "(DATA1,ASDO),DIFFIO_L1n,IO_6") (pintype "input"))
      (node (ref "U4") (pin "5") (pinfunction "DI_5") (pintype "unspecified"))
    )
    (net (code "95") (name "FPGA_Conf_CLK") (class "Default")
      (node (ref "J2") (pin "5") (pinfunction "5_5") (pintype "input"))
      (node (ref "U3") (pin "12") (pinfunction "DCLK_12") (pintype "input"))
      (node (ref "U4") (pin "6") (pinfunction "CLK_6") (pintype "unspecified"))
    )
    (net (code "96") (name "FPGA_Conf_Data") (class "Default")
      (node (ref "J2") (pin "3") (pinfunction "3_3") (pintype "input"))
      (node (ref "R1") (pin "1") (pinfunction "1_1") (pintype "unspecified"))
      (node (ref "U3") (pin "13") (pinfunction "(DATA0),IO_13") (pintype "input"))
    )
    (net (code "97") (name "FPGA_Conf_nCE") (class "Default")
      (node (ref "J2") (pin "1") (pinfunction "1_1") (pintype "input"))
      (node (ref "U3") (pin "8") (pinfunction "(FLASH_nCE,nCSO),DIFFIO_L2p,IO_8") (pintype "input"))
      (node (ref "U4") (pin "1") (pinfunction "/CS_1") (pintype "unspecified"))
    )
    (net (code "98") (name "FPGA_SPECIAL_IC_SCL") (class "Default")
      (node (ref "J3") (pin "3") (pinfunction "3_3") (pintype "input"))
      (node (ref "R3") (pin "1") (pinfunction "1_1") (pintype "unspecified"))
      (node (ref "U3") (pin "34") (pinfunction "IO_34") (pintype "input"))
      (node (ref "U5") (pin "6") (pinfunction "SCL_6") (pintype "unspecified"))
    )
    (net (code "99") (name "FPGA_SPECIAL_IC_SDA") (class "Default")
      (node (ref "J3") (pin "4") (pinfunction "4_4") (pintype "input"))
      (node (ref "R2") (pin "1") (pinfunction "1_1") (pintype "unspecified"))
      (node (ref "U3") (pin "33") (pinfunction "RDN1,IO_33") (pintype "input"))
      (node (ref "U5") (pin "5") (pinfunction "SDA_5") (pintype "unspecified"))
    )
    (net (code "100") (name "GND") (class "Default")
      (node (ref "C1") (pin "2") (pinfunction "2_2") (pintype "input"))
      (node (ref "C10") (pin "2") (pinfunction "2_2") (pintype "input"))
      (node (ref "C100") (pin "1") (pinfunction "1_1") (pintype "input"))
      (node (ref "C101") (pin "1") (pinfunction "1_1") (pintype "input"))
      (node (ref "C106") (pin "1") (pinfunction "1_1") (pintype "input"))
      (node (ref "C11") (pin "2") (pinfunction "2_2") (pintype "input"))
      (node (ref "C111") (pin "1") (pinfunction "1_1") (pintype "input"))
      (node (ref "C112") (pin "1") (pinfunction "1_1") (pintype "input"))
      (node (ref "C113") (pin "1") (pinfunction "1_1") (pintype "input"))
      (node (ref "C115") (pin "1") (pinfunction "1_1") (pintype "input"))
      (node (ref "C116") (pin "2") (pinfunction "2_2") (pintype "input"))
      (node (ref "C117") (pin "1") (pinfunction "1_1") (pintype "input"))
      (node (ref "C119") (pin "1") (pinfunction "1_1") (pintype "input"))
      (node (ref "C12") (pin "2") (pinfunction "2_2") (pintype "input"))
      (node (ref "C120") (pin "2") (pinfunction "2_2") (pintype "input"))
      (node (ref "C121") (pin "1") (pinfunction "1_1") (pintype "input"))
      (node (ref "C126") (pin "1") (pinfunction "1_1") (pintype "input"))
      (node (ref "C13") (pin "2") (pinfunction "2_2") (pintype "input"))
      (node (ref "C131") (pin "2") (pinfunction "2_2") (pintype "input"))
      (node (ref "C132") (pin "2") (pinfunction "2_2") (pintype "input"))
      (node (ref "C135") (pin "2") (pinfunction "2_2") (pintype "input"))
      (node (ref "C136") (pin "2") (pinfunction "2_2") (pintype "input"))
      (node (ref "C137") (pin "2") (pinfunction "2_2") (pintype "input"))
      (node (ref "C138") (pin "2") (pinfunction "2_2") (pintype "input"))
      (node (ref "C139") (pin "2") (pinfunction "2_2") (pintype "input"))
      (node (ref "C14") (pin "2") (pinfunction "2_2") (pintype "input"))
      (node (ref "C140") (pin "2") (pinfunction "2_2") (pintype "input"))
      (node (ref "C141") (pin "2") (pinfunction "2_2") (pintype "input"))
      (node (ref "C142") (pin "2") (pinfunction "2_2") (pintype "input"))
      (node (ref "C143") (pin "2") (pinfunction "2_2") (pintype "input"))
      (node (ref "C144") (pin "2") (pinfunction "2_2") (pintype "input"))
      (node (ref "C145") (pin "2") (pinfunction "2_2") (pintype "input"))
      (node (ref "C146") (pin "2") (pinfunction "2_2") (pintype "input"))
      (node (ref "C147") (pin "2") (pinfunction "2_2") (pintype "input"))
      (node (ref "C148") (pin "2") (pinfunction "2_2") (pintype "input"))
      (node (ref "C15") (pin "2") (pinfunction "2_2") (pintype "input"))
      (node (ref "C150") (pin "2") (pinfunction "2_2") (pintype "input"))
      (node (ref "C151") (pin "2") (pinfunction "2_2") (pintype "input"))
      (node (ref "C152") (pin "2") (pinfunction "2_2") (pintype "input"))
      (node (ref "C153") (pin "2") (pinfunction "2_2") (pintype "input"))
      (node (ref "C154") (pin "2") (pinfunction "2_2") (pintype "input"))
      (node (ref "C155") (pin "2") (pinfunction "2_2") (pintype "input"))
      (node (ref "C156") (pin "2") (pinfunction "2_2") (pintype "input"))
      (node (ref "C157") (pin "2") (pinfunction "2_2") (pintype "input"))
      (node (ref "C158") (pin "2") (pinfunction "2_2") (pintype "input"))
      (node (ref "C159") (pin "2") (pinfunction "2_2") (pintype "input"))
      (node (ref "C16") (pin "2") (pinfunction "2_2") (pintype "input"))
      (node (ref "C160") (pin "2") (pinfunction "2_2") (pintype "input"))
      (node (ref "C161") (pin "2") (pinfunction "2_2") (pintype "input"))
      (node (ref "C162") (pin "2") (pinfunction "2_2") (pintype "input"))
      (node (ref "C163") (pin "2") (pinfunction "2_2") (pintype "input"))
      (node (ref "C164") (pin "2") (pinfunction "2_2") (pintype "input"))
      (node (ref "C165") (pin "2") (pinfunction "2_2") (pintype "input"))
      (node (ref "C166") (pin "2") (pinfunction "2_2") (pintype "input"))
      (node (ref "C167") (pin "2") (pinfunction "2_2") (pintype "input"))
      (node (ref "C17") (pin "2") (pinfunction "2_2") (pintype "input"))
      (node (ref "C18") (pin "2") (pinfunction "2_2") (pintype "input"))
      (node (ref "C19") (pin "2") (pinfunction "2_2") (pintype "input"))
      (node (ref "C20") (pin "2") (pinfunction "2_2") (pintype "input"))
      (node (ref "C21") (pin "2") (pinfunction "2_2") (pintype "input"))
      (node (ref "C22") (pin "2") (pinfunction "2_2") (pintype "input"))
      (node (ref "C23") (pin "2") (pinfunction "2_2") (pintype "input"))
      (node (ref "C24") (pin "2") (pinfunction "2_2") (pintype "input"))
      (node (ref "C25") (pin "2") (pinfunction "2_2") (pintype "input"))
      (node (ref "C26") (pin "2") (pinfunction "2_2") (pintype "input"))
      (node (ref "C27") (pin "2") (pinfunction "2_2") (pintype "input"))
      (node (ref "C28") (pin "2") (pinfunction "2_2") (pintype "input"))
      (node (ref "C29") (pin "2") (pinfunction "2_2") (pintype "input"))
      (node (ref "C30") (pin "2") (pinfunction "2_2") (pintype "input"))
      (node (ref "C31") (pin "2") (pinfunction "2_2") (pintype "input"))
      (node (ref "C32") (pin "2") (pinfunction "2_2") (pintype "input"))
      (node (ref "C33") (pin "2") (pinfunction "2_2") (pintype "input"))
      (node (ref "C34") (pin "2") (pinfunction "2_2") (pintype "input"))
      (node (ref "C35") (pin "2") (pinfunction "2_2") (pintype "input"))
      (node (ref "C36") (pin "2") (pinfunction "2_2") (pintype "input"))
      (node (ref "C37") (pin "2") (pinfunction "2_2") (pintype "input"))
      (node (ref "C38") (pin "2") (pinfunction "2_2") (pintype "input"))
      (node (ref "C39") (pin "2") (pinfunction "2_2") (pintype "input"))
      (node (ref "C4") (pin "2") (pinfunction "2_2") (pintype "input"))
      (node (ref "C40") (pin "2") (pinfunction "2_2") (pintype "input"))
      (node (ref "C41") (pin "2") (pinfunction "2_2") (pintype "input"))
      (node (ref "C42") (pin "2") (pinfunction "2_2") (pintype "input"))
      (node (ref "C43") (pin "2") (pinfunction "2_2") (pintype "input"))
      (node (ref "C44") (pin "2") (pinfunction "2_2") (pintype "input"))
      (node (ref "C45") (pin "2") (pinfunction "2_2") (pintype "input"))
      (node (ref "C46") (pin "2") (pinfunction "2_2") (pintype "input"))
      (node (ref "C47") (pin "2") (pinfunction "2_2") (pintype "input"))
      (node (ref "C48") (pin "2") (pinfunction "2_2") (pintype "input"))
      (node (ref "C49") (pin "2") (pinfunction "2_2") (pintype "input"))
      (node (ref "C50") (pin "2") (pinfunction "2_2") (pintype "input"))
      (node (ref "C51") (pin "2") (pinfunction "2_2") (pintype "input"))
      (node (ref "C52") (pin "2") (pinfunction "2_2") (pintype "input"))
      (node (ref "C53") (pin "2") (pinfunction "2_2") (pintype "input"))
      (node (ref "C54") (pin "2") (pinfunction "2_2") (pintype "input"))
      (node (ref "C55") (pin "2") (pinfunction "2_2") (pintype "input"))
      (node (ref "C56") (pin "2") (pinfunction "2_2") (pintype "input"))
      (node (ref "C57") (pin "2") (pinfunction "2_2") (pintype "input"))
      (node (ref "C58") (pin "2") (pinfunction "2_2") (pintype "input"))
      (node (ref "C59") (pin "2") (pinfunction "2_2") (pintype "input"))
      (node (ref "C60") (pin "2") (pinfunction "2_2") (pintype "input"))
      (node (ref "C61") (pin "2") (pinfunction "2_2") (pintype "input"))
      (node (ref "C62") (pin "2") (pinfunction "2_2") (pintype "input"))
      (node (ref "C63") (pin "2") (pinfunction "2_2") (pintype "input"))
      (node (ref "C64") (pin "2") (pinfunction "2_2") (pintype "input"))
      (node (ref "C65") (pin "2") (pinfunction "2_2") (pintype "input"))
      (node (ref "C66") (pin "2") (pinfunction "2_2") (pintype "input"))
      (node (ref "C67") (pin "2") (pinfunction "2_2") (pintype "input"))
      (node (ref "C68") (pin "2") (pinfunction "2_2") (pintype "input"))
      (node (ref "C69") (pin "2") (pinfunction "2_2") (pintype "input"))
      (node (ref "C7") (pin "2") (pinfunction "2_2") (pintype "input"))
      (node (ref "C70") (pin "2") (pinfunction "2_2") (pintype "input"))
      (node (ref "C71") (pin "2") (pinfunction "2_2") (pintype "input"))
      (node (ref "C72") (pin "2") (pinfunction "2_2") (pintype "input"))
      (node (ref "C73") (pin "1") (pinfunction "1_1") (pintype "input"))
      (node (ref "C74") (pin "2") (pinfunction "2_2") (pintype "input"))
      (node (ref "C75") (pin "2") (pinfunction "2_2") (pintype "input"))
      (node (ref "C76") (pin "2") (pinfunction "2_2") (pintype "input"))
      (node (ref "C77") (pin "2") (pinfunction "2_2") (pintype "input"))
      (node (ref "C78") (pin "2") (pinfunction "2_2") (pintype "input"))
      (node (ref "C79") (pin "2") (pinfunction "2_2") (pintype "input"))
      (node (ref "C8") (pin "2") (pinfunction "2_2") (pintype "input"))
      (node (ref "C80") (pin "2") (pinfunction "2_2") (pintype "input"))
      (node (ref "C81") (pin "2") (pinfunction "2_2") (pintype "input"))
      (node (ref "C82") (pin "2") (pinfunction "2_2") (pintype "input"))
      (node (ref "C83") (pin "2") (pinfunction "2_2") (pintype "input"))
      (node (ref "C85") (pin "2") (pinfunction "2_2") (pintype "input"))
      (node (ref "C86") (pin "2") (pinfunction "2_2") (pintype "input"))
      (node (ref "C87") (pin "2") (pinfunction "2_2") (pintype "input"))
      (node (ref "C88") (pin "2") (pinfunction "2_2") (pintype "input"))
      (node (ref "C9") (pin "2") (pinfunction "2_2") (pintype "input"))
      (node (ref "C90") (pin "2") (pinfunction "2_2") (pintype "input"))
      (node (ref "C91") (pin "2") (pinfunction "2_2") (pintype "input"))
      (node (ref "C92") (pin "2") (pinfunction "2_2") (pintype "input"))
      (node (ref "C93") (pin "2") (pinfunction "2_2") (pintype "input"))
      (node (ref "C94") (pin "2") (pinfunction "2_2") (pintype "input"))
      (node (ref "C95") (pin "2") (pinfunction "2_2") (pintype "input"))
      (node (ref "C96") (pin "2") (pinfunction "2_2") (pintype "input"))
      (node (ref "C97") (pin "2") (pinfunction "2_2") (pintype "input"))
      (node (ref "C98") (pin "2") (pinfunction "2_2") (pintype "input"))
      (node (ref "CON1") (pin "2") (pinfunction "2_2") (pintype "bidirectional"))
      (node (ref "D11") (pin "2") (pinfunction "2_2") (pintype "unspecified"))
      (node (ref "D15") (pin "2") (pinfunction "2_2") (pintype "unspecified"))
      (node (ref "D8") (pin "2") (pinfunction "K_2") (pintype "unspecified"))
      (node (ref "J1") (pin "2") (pinfunction "2_2") (pintype "input"))
      (node (ref "J2") (pin "2") (pinfunction "2_2") (pintype "input"))
      (node (ref "J3") (pin "1") (pinfunction "1_1") (pintype "input"))
      (node (ref "J5") (pin "10") (pinfunction "10_10") (pintype "unspecified"))
      (node (ref "J5") (pin "2") (pinfunction "2_2") (pintype "unspecified"))
      (node (ref "J6") (pin "2") (pinfunction "2_2") (pintype "input"))
      (node (ref "K1") (pin "8") (pinfunction "8_8") (pintype "input"))
      (node (ref "K2") (pin "8") (pinfunction "8_8") (pintype "input"))
      (node (ref "K3") (pin "8") (pinfunction "8_8") (pintype "input"))
      (node (ref "K4") (pin "8") (pinfunction "8_8") (pintype "input"))
      (node (ref "K5") (pin "8") (pinfunction "8_8") (pintype "input"))
      (node (ref "K6") (pin "8") (pinfunction "8_8") (pintype "input"))
      (node (ref "L2") (pin "1") (pinfunction "1_1") (pintype "unspecified"))
      (node (ref "L3") (pin "1") (pinfunction "1_1") (pintype "unspecified"))
      (node (ref "P2") (pin "10") (pinfunction "BODY_10") (pintype "unspecified"))
      (node (ref "P2") (pin "6") (pinfunction "GND_6") (pintype "unspecified"))
      (node (ref "P2") (pin "9") (pinfunction "CARD_DETECT_9") (pintype "unspecified"))
      (node (ref "P3") (pin "17") (pinfunction "17_17") (pintype "unspecified"))
      (node (ref "P3") (pin "18") (pinfunction "18_18") (pintype "unspecified"))
      (node (ref "P3") (pin "19") (pinfunction "19_19") (pintype "unspecified"))
      (node (ref "P3") (pin "26") (pinfunction "26_26") (pintype "unspecified"))
      (node (ref "P3") (pin "27") (pinfunction "27_27") (pintype "unspecified"))
      (node (ref "P3") (pin "33") (pinfunction "33_33") (pintype "unspecified"))
      (node (ref "P3") (pin "34") (pinfunction "34_34") (pintype "unspecified"))
      (node (ref "P3") (pin "35") (pinfunction "35_35") (pintype "unspecified"))
      (node (ref "P3") (pin "36") (pinfunction "36_36") (pintype "unspecified"))
      (node (ref "P3") (pin "38") (pinfunction "38_38") (pintype "unspecified"))
      (node (ref "P3") (pin "40") (pinfunction "40_40") (pintype "unspecified"))
      (node (ref "P3") (pin "47") (pinfunction "47_47") (pintype "unspecified"))
      (node (ref "P3") (pin "48") (pinfunction "48_48") (pintype "unspecified"))
      (node (ref "P3") (pin "49") (pinfunction "49_49") (pintype "unspecified"))
      (node (ref "P3") (pin "5") (pinfunction "5_5") (pintype "unspecified"))
      (node (ref "P3") (pin "50") (pinfunction "50_50") (pintype "unspecified"))
      (node (ref "P3") (pin "8") (pinfunction "8_8") (pintype "unspecified"))
      (node (ref "Q7") (pin "2") (pinfunction "E_2") (pintype "input"))
      (node (ref "R104") (pin "1") (pinfunction "1_1") (pintype "unspecified"))
      (node (ref "R107") (pin "1") (pinfunction "1_1") (pintype "unspecified"))
      (node (ref "R108") (pin "1") (pinfunction "1_1") (pintype "unspecified"))
      (node (ref "R111") (pin "1") (pinfunction "1_1") (pintype "unspecified"))
      (node (ref "R116") (pin "1") (pinfunction "1_1") (pintype "unspecified"))
      (node (ref "R119") (pin "1") (pinfunction "1_1") (pintype "unspecified"))
      (node (ref "R120") (pin "1") (pinfunction "1_1") (pintype "unspecified"))
      (node (ref "R123") (pin "1") (pinfunction "1_1") (pintype "unspecified"))
      (node (ref "R126") (pin "1") (pinfunction "1_1") (pintype "unspecified"))
      (node (ref "R129") (pin "1") (pinfunction "1_1") (pintype "unspecified"))
      (node (ref "R134") (pin "1") (pinfunction "1_1") (pintype "unspecified"))
      (node (ref "R137") (pin "1") (pinfunction "1_1") (pintype "unspecified"))
      (node (ref "R140") (pin "1") (pinfunction "1_1") (pintype "unspecified"))
      (node (ref "R143") (pin "1") (pinfunction "1_1") (pintype "unspecified"))
      (node (ref "R144") (pin "1") (pinfunction "1_1") (pintype "unspecified"))
      (node (ref "R147") (pin "1") (pinfunction "1_1") (pintype "unspecified"))
      (node (ref "R29") (pin "1") (pinfunction "1_1") (pintype "unspecified"))
      (node (ref "R31") (pin "1") (pinfunction "1_1") (pintype "unspecified"))
      (node (ref "R32") (pin "1") (pinfunction "1_1") (pintype "unspecified"))
      (node (ref "R45") (pin "1") (pinfunction "1_1") (pintype "unspecified"))
      (node (ref "R48") (pin "1") (pinfunction "1_1") (pintype "unspecified"))
      (node (ref "R57") (pin "1") (pinfunction "1_1") (pintype "unspecified"))
      (node (ref "R58") (pin "1") (pinfunction "1_1") (pintype "unspecified"))
      (node (ref "R59") (pin "1") (pinfunction "1_1") (pintype "unspecified"))
      (node (ref "R6") (pin "2") (pinfunction "2_2") (pintype "unspecified"))
      (node (ref "R60") (pin "1") (pinfunction "1_1") (pintype "unspecified"))
      (node (ref "R61") (pin "1") (pinfunction "1_1") (pintype "unspecified"))
      (node (ref "R7") (pin "2") (pinfunction "2_2") (pintype "unspecified"))
      (node (ref "R93") (pin "2") (pinfunction "2_2") (pintype "unspecified"))
      (node (ref "R94") (pin "2") (pinfunction "2_2") (pintype "unspecified"))
      (node (ref "S1") (pin "1") (pinfunction "1_1") (pintype "unspecified"))
      (node (ref "SW1") (pin "2") (pinfunction "C_2") (pintype "input"))
      (node (ref "SW2") (pin "2") (pinfunction "C_2") (pintype "input"))
      (node (ref "SW3") (pin "2") (pinfunction "C_2") (pintype "input"))
      (node (ref "SW4") (pin "2") (pinfunction "C_2") (pintype "input"))
      (node (ref "SW5") (pin "2") (pinfunction "C_2") (pintype "input"))
      (node (ref "SW6") (pin "2") (pinfunction "C_2") (pintype "input"))
      (node (ref "SW7") (pin "2") (pinfunction "C_2") (pintype "input"))
      (node (ref "SW8") (pin "2") (pinfunction "C_2") (pintype "input"))
      (node (ref "U1") (pin "74") (pinfunction "TVGND_74") (pintype "unspecified"))
      (node (ref "U1") (pin "82") (pinfunction "AGND_82") (pintype "unspecified"))
      (node (ref "U1") (pin "89") (pinfunction "GND_89") (pintype "unspecified"))
      (node (ref "U10") (pin "1") (pinfunction "ADJ/GND_1") (pintype "unspecified"))
      (node (ref "U11") (pin "2") (pinfunction "GND_2") (pintype "unspecified"))
      (node (ref "U12") (pin "1") (pinfunction "GND_1") (pintype "passive"))
      (node (ref "U13") (pin "8") (pinfunction "GND_8") (pintype "unspecified"))
      (node (ref "U14") (pin "2") (pinfunction "V-_2") (pintype "passive"))
      (node (ref "U15") (pin "2") (pinfunction "GND_2") (pintype "unspecified"))
      (node (ref "U16") (pin "2") (pinfunction "GND_2") (pintype "unspecified"))
      (node (ref "U17") (pin "2") (pinfunction "V-_2") (pintype "passive"))
      (node (ref "U18") (pin "2") (pinfunction "K_2") (pintype "unspecified"))
      (node (ref "U19") (pin "2") (pinfunction "K_2") (pintype "unspecified"))
      (node (ref "U2") (pin "4") (pinfunction "GND_4") (pintype "unspecified"))
      (node (ref "U20") (pin "2") (pinfunction "V-_2") (pintype "passive"))
      (node (ref "U21") (pin "3") (pinfunction "ANODE_3") (pintype "unspecified"))
      (node (ref "U22") (pin "23") (pinfunction "VSS_23") (pintype "unspecified"))
      (node (ref "U22") (pin "44") (pinfunction "BOOT0_44") (pintype "unspecified"))
      (node (ref "U22") (pin "47") (pinfunction "VSS_47") (pintype "unspecified"))
      (node (ref "U22") (pin "8") (pinfunction "VSSA_8") (pintype "unspecified"))
      (node (ref "U3") (pin "118") (pinfunction "GND_118") (pintype "input"))
      (node (ref "U3") (pin "123") (pinfunction "GND_123") (pintype "input"))
      (node (ref "U3") (pin "131") (pinfunction "GND_131") (pintype "input"))
      (node (ref "U3") (pin "140") (pinfunction "GND_140") (pintype "input"))
      (node (ref "U3") (pin "145") (pinfunction "GND_(PAD)_145") (pintype "input"))
      (node (ref "U3") (pin "19") (pinfunction "GND_19") (pintype "input"))
      (node (ref "U3") (pin "22") (pinfunction "GND_22") (pintype "input"))
      (node (ref "U3") (pin "27") (pinfunction "GND_27") (pintype "input"))
      (node (ref "U3") (pin "4") (pinfunction "GND_4") (pintype "input"))
      (node (ref "U3") (pin "41") (pinfunction "GND_41") (pintype "input"))
      (node (ref "U3") (pin "48") (pinfunction "GND_48") (pintype "input"))
      (node (ref "U3") (pin "57") (pinfunction "GND_57") (pintype "input"))
      (node (ref "U3") (pin "63") (pinfunction "GND_63") (pintype "input"))
      (node (ref "U3") (pin "79") (pinfunction "GND_79") (pintype "input"))
      (node (ref "U3") (pin "82") (pinfunction "GND_82") (pintype "input"))
      (node (ref "U3") (pin "94") (pinfunction "MSEL0_94") (pintype "input"))
      (node (ref "U3") (pin "95") (pinfunction "GND_95") (pintype "input"))
      (node (ref "U3") (pin "97") (pinfunction "MSEL2_97") (pintype "input"))
      (node (ref "U4") (pin "4") (pinfunction "GND_4") (pintype "unspecified"))
      (node (ref "U5") (pin "4") (pinfunction "VSS_4") (pintype "unspecified"))
      (node (ref "U6") (pin "1") (pinfunction "ADJ/GND_1") (pintype "unspecified"))
      (node (ref "U7") (pin "1") (pinfunction "GND_1") (pintype "passive"))
      (node (ref "U7") (pin "12") (pinfunction "GND_12") (pintype "passive"))
      (node (ref "U7") (pin "16") (pinfunction "GND_16") (pintype "passive"))
      (node (ref "U7") (pin "27") (pinfunction "GND_27") (pintype "passive"))
      (node (ref "U7") (pin "29") (pinfunction "GND_29") (pintype "passive"))
      (node (ref "U7") (pin "32") (pinfunction "GND_32") (pintype "passive"))
      (node (ref "U7") (pin "34") (pinfunction "GND_34") (pintype "passive"))
      (node (ref "U7") (pin "4") (pinfunction "DFS_4") (pintype "unspecified"))
      (node (ref "U7") (pin "45") (pinfunction "GND_45") (pintype "passive"))
      (node (ref "U8") (pin "1") (pinfunction "GND_1") (pintype "passive"))
      (node (ref "U8") (pin "12") (pinfunction "GND_12") (pintype "passive"))
      (node (ref "U8") (pin "16") (pinfunction "GND_16") (pintype "passive"))
      (node (ref "U8") (pin "27") (pinfunction "GND_27") (pintype "passive"))
      (node (ref "U8") (pin "29") (pinfunction "GND_29") (pintype "passive"))
      (node (ref "U8") (pin "32") (pinfunction "GND_32") (pintype "passive"))
      (node (ref "U8") (pin "34") (pinfunction "GND_34") (pintype "passive"))
      (node (ref "U8") (pin "4") (pinfunction "DFS_4") (pintype "unspecified"))
      (node (ref "U8") (pin "45") (pinfunction "GND_45") (pintype "passive"))
      (node (ref "U9") (pin "1") (pinfunction "GND_1") (pintype "unspecified"))
      (node (ref "USB1") (pin "4") (pinfunction "GND_4") (pintype "input"))
    )
    (net (code "101") (name "JTAG-TCK") (class "Default")
      (node (ref "J5") (pin "1") (pinfunction "1_1") (pintype "unspecified"))
    )
    (net (code "102") (name "JTAG-TDI") (class "Default")
      (node (ref "J5") (pin "9") (pinfunction "9_9") (pintype "unspecified"))
    )
    (net (code "103") (name "JTAG-TDO") (class "Default")
      (node (ref "J5") (pin "3") (pinfunction "3_3") (pintype "unspecified"))
    )
    (net (code "104") (name "JTAG-TMS") (class "Default")
      (node (ref "J5") (pin "5") (pinfunction "5_5") (pintype "unspecified"))
    )
    (net (code "105") (name "LCD_CLK") (class "Default")
      (node (ref "P3") (pin "37") (pinfunction "37_37") (pintype "unspecified"))
      (node (ref "U1") (pin "26") (pinfunction "PD18/LCD_CLK/SPI0_CS_26") (pintype "unspecified"))
    )
    (net (code "106") (name "LCD_D3") (class "Default")
      (node (ref "P3") (pin "16") (pinfunction "16_16") (pintype "unspecified"))
      (node (ref "U1") (pin "7") (pinfunction "PD1/LCD_D3/UART1_RTS_7") (pintype "unspecified"))
    )
    (net (code "107") (name "LCD_D4") (class "Default")
      (node (ref "P3") (pin "15") (pinfunction "15_15") (pintype "unspecified"))
      (node (ref "U1") (pin "8") (pinfunction "PD2/LCD_D4/UART1_CTS_8") (pintype "unspecified"))
    )
    (net (code "108") (name "LCD_D5") (class "Default")
      (node (ref "P3") (pin "14") (pinfunction "14_14") (pintype "unspecified"))
      (node (ref "U1") (pin "9") (pinfunction "PD3/LCD_D5/UART1_RX_9") (pintype "unspecified"))
    )
    (net (code "109") (name "LCD_D6") (class "Default")
      (node (ref "P3") (pin "13") (pinfunction "13_13") (pintype "unspecified"))
      (node (ref "U1") (pin "10") (pinfunction "PD4/LCD_D6/UART1_TX_10") (pintype "unspecified"))
    )
    (net (code "110") (name "LCD_D7") (class "Default")
      (node (ref "P3") (pin "12") (pinfunction "12_12") (pintype "unspecified"))
      (node (ref "U1") (pin "11") (pinfunction "PD5/LCD_D7/TWI1_SCK_11") (pintype "unspecified"))
    )
    (net (code "111") (name "LCD_D10") (class "Default")
      (node (ref "P3") (pin "25") (pinfunction "25_25") (pintype "unspecified"))
      (node (ref "U1") (pin "12") (pinfunction "PD6/LCD_D10/TWI1_SDA_12") (pintype "unspecified"))
    )
    (net (code "112") (name "LCD_D11") (class "Default")
      (node (ref "P3") (pin "24") (pinfunction "24_24") (pintype "unspecified"))
      (node (ref "U1") (pin "13") (pinfunction "PD7/LCD_D11/DA_MCLK_13") (pintype "unspecified"))
    )
    (net (code "113") (name "LCD_D12") (class "Default")
      (node (ref "P3") (pin "23") (pinfunction "23_23") (pintype "unspecified"))
      (node (ref "U1") (pin "14") (pinfunction "PD8/LCD_D12/DA_BCLK_14") (pintype "unspecified"))
    )
    (net (code "114") (name "LCD_D13") (class "Default")
      (node (ref "P3") (pin "22") (pinfunction "22_22") (pintype "unspecified"))
      (node (ref "U1") (pin "15") (pinfunction "PD9/LCD_D13/DA_LRCK_15") (pintype "unspecified"))
    )
    (net (code "115") (name "LCD_D14") (class "Default")
      (node (ref "P3") (pin "21") (pinfunction "21_21") (pintype "unspecified"))
      (node (ref "U1") (pin "16") (pinfunction "PD10/LCD_D14/DA_IN_16") (pintype "unspecified"))
    )
    (net (code "116") (name "LCD_D15") (class "Default")
      (node (ref "P3") (pin "20") (pinfunction "20_20") (pintype "unspecified"))
      (node (ref "U1") (pin "17") (pinfunction "PD11/LCD_D15/DA_OUT_17") (pintype "unspecified"))
    )
    (net (code "117") (name "LCD_D19") (class "Default")
      (node (ref "P3") (pin "32") (pinfunction "32_32") (pintype "unspecified"))
      (node (ref "U1") (pin "19") (pinfunction "PD13/LCD_D19/UART2_TX_19") (pintype "unspecified"))
    )
    (net (code "118") (name "LCD_D20") (class "Default")
      (node (ref "P3") (pin "31") (pinfunction "31_31") (pintype "unspecified"))
      (node (ref "U1") (pin "21") (pinfunction "PD14/LCD_D20/UART2_RX_21") (pintype "unspecified"))
    )
    (net (code "119") (name "LCD_D21") (class "Default")
      (node (ref "P3") (pin "30") (pinfunction "30_30") (pintype "unspecified"))
      (node (ref "U1") (pin "23") (pinfunction "PD15/LCD_D21/UART2_RST/TWI2_SCK_23") (pintype "unspecified"))
    )
    (net (code "120") (name "LCD_D22") (class "Default")
      (node (ref "P3") (pin "29") (pinfunction "29_29") (pintype "unspecified"))
      (node (ref "U1") (pin "24") (pinfunction "PD16/LCD_D22/UART2_CTS/TWI2_SDA_24") (pintype "unspecified"))
    )
    (net (code "121") (name "LCD_D23") (class "Default")
      (node (ref "P3") (pin "28") (pinfunction "28_28") (pintype "unspecified"))
      (node (ref "U1") (pin "25") (pinfunction "PD17/LCD_D23/OWA_OUT_25") (pintype "unspecified"))
    )
    (net (code "122") (name "LCD_DE") (class "Default")
      (node (ref "P3") (pin "9") (pinfunction "9_9") (pintype "unspecified"))
      (node (ref "U1") (pin "27") (pinfunction "PD19/LCD_DE/SPI0_MOSI_27") (pintype "unspecified"))
    )
    (net (code "123") (name "LCD_HSYNC") (class "Default")
      (node (ref "P3") (pin "11") (pinfunction "11_11") (pintype "unspecified"))
      (node (ref "R43") (pin "1") (pinfunction "1_1") (pintype "unspecified"))
      (node (ref "U1") (pin "28") (pinfunction "PD20/LCD_HSYNC/SPI0_CLK_28") (pintype "unspecified"))
    )
    (net (code "124") (name "LCD_VSYNC") (class "Default")
      (node (ref "P3") (pin "10") (pinfunction "10_10") (pintype "unspecified"))
      (node (ref "R42") (pin "1") (pinfunction "1_1") (pintype "unspecified"))
      (node (ref "U1") (pin "29") (pinfunction "PD21/LCD_VSYNC/SPI0_MISO_29") (pintype "unspecified"))
    )
    (net (code "125") (name "MATRIX_1A") (class "Default")
      (node (ref "R150") (pin "2") (pinfunction "2_2") (pintype "unspecified"))
      (node (ref "S2") (pin "1") (pinfunction "1_1") (pintype "unspecified"))
      (node (ref "S3") (pin "1") (pinfunction "1_1") (pintype "unspecified"))
      (node (ref "S4") (pin "1") (pinfunction "1_1") (pintype "unspecified"))
      (node (ref "S5") (pin "1") (pinfunction "1_1") (pintype "unspecified"))
      (node (ref "S6") (pin "1") (pinfunction "1_1") (pintype "unspecified"))
      (node (ref "S7") (pin "1") (pinfunction "1_1") (pintype "unspecified"))
      (node (ref "U22") (pin "43") (pinfunction "PB7_43") (pintype "unspecified"))
    )
    (net (code "126") (name "MATRIX_1B") (class "Default")
      (node (ref "R156") (pin "1") (pinfunction "1_1") (pintype "unspecified"))
      (node (ref "S13") (pin "2") (pinfunction "2_2") (pintype "unspecified"))
      (node (ref "S19") (pin "2") (pinfunction "2_2") (pintype "unspecified"))
      (node (ref "S2") (pin "2") (pinfunction "2_2") (pintype "unspecified"))
      (node (ref "S25") (pin "2") (pinfunction "2_2") (pintype "unspecified"))
      (node (ref "S31") (pin "2") (pinfunction "2_2") (pintype "unspecified"))
      (node (ref "U22") (pin "17") (pinfunction "PA7_17") (pintype "unspecified"))
    )
    (net (code "127") (name "MATRIX_2A") (class "Default")
      (node (ref "R151") (pin "2") (pinfunction "2_2") (pintype "unspecified"))
      (node (ref "S10") (pin "1") (pinfunction "1_1") (pintype "unspecified"))
      (node (ref "S11") (pin "1") (pinfunction "1_1") (pintype "unspecified"))
      (node (ref "S12") (pin "1") (pinfunction "1_1") (pintype "unspecified"))
      (node (ref "S13") (pin "1") (pinfunction "1_1") (pintype "unspecified"))
      (node (ref "S8") (pin "1") (pinfunction "1_1") (pintype "unspecified"))
      (node (ref "S9") (pin "1") (pinfunction "1_1") (pintype "unspecified"))
      (node (ref "U22") (pin "42") (pinfunction "PB6_42") (pintype "unspecified"))
    )
    (net (code "128") (name "MATRIX_2B") (class "Default")
      (node (ref "R157") (pin "1") (pinfunction "1_1") (pintype "unspecified"))
      (node (ref "S12") (pin "2") (pinfunction "2_2") (pintype "unspecified"))
      (node (ref "S18") (pin "2") (pinfunction "2_2") (pintype "unspecified"))
      (node (ref "S24") (pin "2") (pinfunction "2_2") (pintype "unspecified"))
      (node (ref "S3") (pin "2") (pinfunction "2_2") (pintype "unspecified"))
      (node (ref "S30") (pin "2") (pinfunction "2_2") (pintype "unspecified"))
      (node (ref "U22") (pin "18") (pinfunction "PB0_18") (pintype "unspecified"))
    )
    (net (code "129") (name "MATRIX_3A") (class "Default")
      (node (ref "R152") (pin "2") (pinfunction "2_2") (pintype "unspecified"))
      (node (ref "S14") (pin "1") (pinfunction "1_1") (pintype "unspecified"))
      (node (ref "S15") (pin "1") (pinfunction "1_1") (pintype "unspecified"))
      (node (ref "S16") (pin "1") (pinfunction "1_1") (pintype "unspecified"))
      (node (ref "S17") (pin "1") (pinfunction "1_1") (pintype "unspecified"))
      (node (ref "S18") (pin "1") (pinfunction "1_1") (pintype "unspecified"))
      (node (ref "S19") (pin "1") (pinfunction "1_1") (pintype "unspecified"))
      (node (ref "U22") (pin "41") (pinfunction "PB5_41") (pintype "unspecified"))
    )
    (net (code "130") (name "MATRIX_3B") (class "Default")
      (node (ref "R158") (pin "1") (pinfunction "1_1") (pintype "unspecified"))
      (node (ref "S11") (pin "2") (pinfunction "2_2") (pintype "unspecified"))
      (node (ref "S17") (pin "2") (pinfunction "2_2") (pintype "unspecified"))
      (node (ref "S23") (pin "2") (pinfunction "2_2") (pintype "unspecified"))
      (node (ref "S29") (pin "2") (pinfunction "2_2") (pintype "unspecified"))
      (node (ref "S35") (pin "2") (pinfunction "2_2") (pintype "unspecified"))
      (node (ref "S4") (pin "2") (pinfunction "2_2") (pintype "unspecified"))
      (node (ref "U22") (pin "19") (pinfunction "PB1_19") (pintype "unspecified"))
    )
    (net (code "131") (name "MATRIX_4A") (class "Default")
      (node (ref "R153") (pin "2") (pinfunction "2_2") (pintype "unspecified"))
      (node (ref "S20") (pin "1") (pinfunction "1_1") (pintype "unspecified"))
      (node (ref "S21") (pin "1") (pinfunction "1_1") (pintype "unspecified"))
      (node (ref "S22") (pin "1") (pinfunction "1_1") (pintype "unspecified"))
      (node (ref "S23") (pin "1") (pinfunction "1_1") (pintype "unspecified"))
      (node (ref "S24") (pin "1") (pinfunction "1_1") (pintype "unspecified"))
      (node (ref "S25") (pin "1") (pinfunction "1_1") (pintype "unspecified"))
      (node (ref "U22") (pin "40") (pinfunction "PB4_40") (pintype "unspecified"))
    )
    (net (code "132") (name "MATRIX_4B") (class "Default")
      (node (ref "R159") (pin "1") (pinfunction "1_1") (pintype "unspecified"))
      (node (ref "S10") (pin "2") (pinfunction "2_2") (pintype "unspecified"))
      (node (ref "S16") (pin "2") (pinfunction "2_2") (pintype "unspecified"))
      (node (ref "S22") (pin "2") (pinfunction "2_2") (pintype "unspecified"))
      (node (ref "S28") (pin "2") (pinfunction "2_2") (pintype "unspecified"))
      (node (ref "S34") (pin "2") (pinfunction "2_2") (pintype "unspecified"))
      (node (ref "S5") (pin "2") (pinfunction "2_2") (pintype "unspecified"))
      (node (ref "U22") (pin "20") (pinfunction "PB2_20") (pintype "unspecified"))
    )
    (net (code "133") (name "MATRIX_5A") (class "Default")
      (node (ref "R154") (pin "2") (pinfunction "2_2") (pintype "unspecified"))
      (node (ref "S26") (pin "1") (pinfunction "1_1") (pintype "unspecified"))
      (node (ref "S27") (pin "1") (pinfunction "1_1") (pintype "unspecified"))
      (node (ref "S28") (pin "1") (pinfunction "1_1") (pintype "unspecified"))
      (node (ref "S29") (pin "1") (pinfunction "1_1") (pintype "unspecified"))
      (node (ref "S30") (pin "1") (pinfunction "1_1") (pintype "unspecified"))
      (node (ref "S31") (pin "1") (pinfunction "1_1") (pintype "unspecified"))
      (node (ref "U22") (pin "39") (pinfunction "PB3_39") (pintype "unspecified"))
    )
    (net (code "134") (name "MATRIX_5B") (class "Default")
      (node (ref "R160") (pin "1") (pinfunction "1_1") (pintype "unspecified"))
      (node (ref "S15") (pin "2") (pinfunction "2_2") (pintype "unspecified"))
      (node (ref "S21") (pin "2") (pinfunction "2_2") (pintype "unspecified"))
      (node (ref "S27") (pin "2") (pinfunction "2_2") (pintype "unspecified"))
      (node (ref "S33") (pin "2") (pinfunction "2_2") (pintype "unspecified"))
      (node (ref "S6") (pin "2") (pinfunction "2_2") (pintype "unspecified"))
      (node (ref "S9") (pin "2") (pinfunction "2_2") (pintype "unspecified"))
      (node (ref "U22") (pin "21") (pinfunction "PB10_21") (pintype "unspecified"))
    )
    (net (code "135") (name "MATRIX_6A") (class "Default")
      (node (ref "R155") (pin "2") (pinfunction "2_2") (pintype "unspecified"))
      (node (ref "S32") (pin "1") (pinfunction "1_1") (pintype "unspecified"))
      (node (ref "S33") (pin "1") (pinfunction "1_1") (pintype "unspecified"))
      (node (ref "S34") (pin "1") (pinfunction "1_1") (pintype "unspecified"))
      (node (ref "S35") (pin "1") (pinfunction "1_1") (pintype "unspecified"))
      (node (ref "U22") (pin "38") (pinfunction "PA15_38") (pintype "unspecified"))
    )
    (net (code "136") (name "MATRIX_6B") (class "Default")
      (node (ref "R161") (pin "1") (pinfunction "1_1") (pintype "unspecified"))
      (node (ref "S14") (pin "2") (pinfunction "2_2") (pintype "unspecified"))
      (node (ref "S20") (pin "2") (pinfunction "2_2") (pintype "unspecified"))
      (node (ref "S26") (pin "2") (pinfunction "2_2") (pintype "unspecified"))
      (node (ref "S32") (pin "2") (pinfunction "2_2") (pintype "unspecified"))
      (node (ref "S7") (pin "2") (pinfunction "2_2") (pintype "unspecified"))
      (node (ref "S8") (pin "2") (pinfunction "2_2") (pintype "unspecified"))
      (node (ref "U22") (pin "22") (pinfunction "PB11_22") (pintype "unspecified"))
    )
    (net (code "137") (name "MCU_FLASH_CE") (class "Default")
      (node (ref "J1") (pin "1") (pinfunction "1_1") (pintype "input"))
      (node (ref "R33") (pin "1") (pinfunction "1_1") (pintype "unspecified"))
      (node (ref "U1") (pin "60") (pinfunction "PC1/SPI0_CS/SDC1_CMD_60") (pintype "unspecified"))
      (node (ref "U2") (pin "1") (pinfunction "/CS_1") (pintype "unspecified"))
    )
    (net (code "138") (name "MCU_FLASH_CLK") (class "Default")
      (node (ref "J1") (pin "5") (pinfunction "5_5") (pintype "input"))
      (node (ref "U1") (pin "59") (pinfunction "PC0/SPI0_CLK/SDC1_CLK_59") (pintype "unspecified"))
      (node (ref "U2") (pin "6") (pinfunction "CLK_6") (pintype "unspecified"))
    )
    (net (code "139") (name "MCU_FLASH_MISO") (class "Default")
      (node (ref "J1") (pin "3") (pinfunction "3_3") (pintype "input"))
      (node (ref "U1") (pin "61") (pinfunction "PC2/SPI0_MISO/SDC1_D0_61") (pintype "unspecified"))
      (node (ref "U2") (pin "2") (pinfunction "DO_2") (pintype "unspecified"))
    )
    (net (code "140") (name "MCU_FLASH_MOSI") (class "Default")
      (node (ref "J1") (pin "6") (pinfunction "6_6") (pintype "input"))
      (node (ref "U1") (pin "62") (pinfunction "PC3/SPI0_MOSI/UART0_TX_62") (pintype "unspecified"))
      (node (ref "U2") (pin "5") (pinfunction "DI_5") (pintype "unspecified"))
    )
    (net (code "141") (name "Net-(C25-Pad1)") (class "Default")
      (node (ref "C25") (pin "1") (pinfunction "1_1") (pintype "input"))
      (node (ref "R24") (pin "2") (pinfunction "2_2") (pintype "unspecified"))
      (node (ref "R25") (pin "1") (pinfunction "1_1") (pintype "unspecified"))
    )
    (net (code "142") (name "Net-(C26-Pad1)") (class "Default")
      (node (ref "C26") (pin "1") (pinfunction "1_1") (pintype "input"))
      (node (ref "C27") (pin "1") (pinfunction "1_1") (pintype "input"))
      (node (ref "R25") (pin "2") (pinfunction "2_2") (pintype "unspecified"))
      (node (ref "U7") (pin "10") (pinfunction "AINB_10") (pintype "unspecified"))
      (node (ref "U7") (pin "3") (pinfunction "AINA_3") (pintype "unspecified"))
    )
    (net (code "143") (name "Net-(C28-Pad1)") (class "Default")
      (node (ref "C28") (pin "1") (pinfunction "1_1") (pintype "input"))
      (node (ref "C29") (pin "1") (pinfunction "1_1") (pintype "input"))
      (node (ref "R27") (pin "2") (pinfunction "2_2") (pintype "unspecified"))
      (node (ref "U8") (pin "10") (pinfunction "AINB_10") (pintype "unspecified"))
      (node (ref "U8") (pin "3") (pinfunction "AINA_3") (pintype "unspecified"))
    )
    (net (code "144") (name "Net-(C30-Pad1)") (class "Default")
      (node (ref "C30") (pin "1") (pinfunction "1_1") (pintype "input"))
      (node (ref "R26") (pin "2") (pinfunction "2_2") (pintype "unspecified"))
      (node (ref "R27") (pin "1") (pinfunction "1_1") (pintype "unspecified"))
    )
    (net (code "145") (name "Net-(C59-Pad1)") (class "Default")
      (node (ref "C59") (pin "1") (pinfunction "1_1") (pintype "input"))
      (node (ref "P3") (pin "46") (pinfunction "46_46") (pintype "unspecified"))
      (node (ref "P3") (pin "6") (pinfunction "6_6") (pintype "unspecified"))
      (node (ref "R44") (pin "1") (pinfunction "1_1") (pintype "unspecified"))
      (node (ref "R45") (pin "2") (pinfunction "2_2") (pintype "unspecified"))
    )
    (net (code "146") (name "Net-(C84-Pad1)") (class "Default")
      (node (ref "C84") (pin "1") (pinfunction "1_1") (pintype "input"))
      (node (ref "C85") (pin "1") (pinfunction "1_1") (pintype "input"))
      (node (ref "R82") (pin "2") (pinfunction "2_2") (pintype "unspecified"))
      (node (ref "R97") (pin "1") (pinfunction "1_1") (pintype "unspecified"))
    )
    (net (code "147") (name "Net-(C102-Pad1)") (class "Default")
      (node (ref "C102") (pin "1") (pinfunction "1_1") (pintype "input"))
      (node (ref "C103") (pin "1") (pinfunction "1_1") (pintype "input"))
      (node (ref "C104") (pin "1") (pinfunction "1_1") (pintype "input"))
      (node (ref "C105") (pin "1") (pinfunction "1_1") (pintype "input"))
      (node (ref "R62") (pin "1") (pinfunction "1_1") (pintype "unspecified"))
      (node (ref "R63") (pin "2") (pinfunction "2_2") (pintype "unspecified"))
      (node (ref "R64") (pin "2") (pinfunction "2_2") (pintype "unspecified"))
      (node (ref "R65") (pin "2") (pinfunction "2_2") (pintype "unspecified"))
    )
    (net (code "148") (name "Net-(C102-Pad2)") (class "Default")
      (node (ref "C102") (pin "2") (pinfunction "2_2") (pintype "input"))
      (node (ref "C107") (pin "2") (pinfunction "2_2") (pintype "input"))
      (node (ref "C108") (pin "2") (pinfunction "2_2") (pintype "input"))
      (node (ref "K2") (pin "2") (pinfunction "2_2") (pintype "input"))
      (node (ref "K2") (pin "7") (pinfunction "7_7") (pintype "input"))
      (node (ref "R63") (pin "1") (pinfunction "1_1") (pintype "unspecified"))
      (node (ref "R66") (pin "1") (pinfunction "1_1") (pintype "unspecified"))
    )
    (net (code "149") (name "Net-(C103-Pad2)") (class "Default")
      (node (ref "C103") (pin "2") (pinfunction "2_2") (pintype "input"))
      (node (ref "C109") (pin "2") (pinfunction "2_2") (pintype "input"))
      (node (ref "C110") (pin "2") (pinfunction "2_2") (pintype "input"))
      (node (ref "K2") (pin "4") (pinfunction "4_4") (pintype "input"))
      (node (ref "K2") (pin "5") (pinfunction "5_5") (pintype "input"))
      (node (ref "R64") (pin "1") (pinfunction "1_1") (pintype "unspecified"))
      (node (ref "R67") (pin "1") (pinfunction "1_1") (pintype "unspecified"))
    )
    (net (code "150") (name "Net-(C104-Pad2)") (class "Default")
      (node (ref "C104") (pin "2") (pinfunction "2_2") (pintype "input"))
      (node (ref "C105") (pin "2") (pinfunction "2_2") (pintype "input"))
      (node (ref "K3") (pin "4") (pinfunction "4_4") (pintype "input"))
      (node (ref "K3") (pin "5") (pinfunction "5_5") (pintype "input"))
      (node (ref "R65") (pin "1") (pinfunction "1_1") (pintype "unspecified"))
      (node (ref "R68") (pin "2") (pinfunction "2_2") (pintype "unspecified"))
    )
    (net (code "151") (name "Net-(C116-Pad1)") (class "Default")
      (node (ref "C116") (pin "1") (pinfunction "1_1") (pintype "input"))
      (node (ref "C134") (pin "1") (pinfunction "1_1") (pintype "input"))
      (node (ref "R100") (pin "2") (pinfunction "2_2") (pintype "unspecified"))
      (node (ref "R71") (pin "1") (pinfunction "1_1") (pintype "unspecified"))
    )
    (net (code "152") (name "Net-(C122-Pad2)") (class "Default")
      (node (ref "C122") (pin "2") (pinfunction "2_2") (pintype "input"))
      (node (ref "C123") (pin "2") (pinfunction "2_2") (pintype "input"))
      (node (ref "C129") (pin "2") (pinfunction "2_2") (pintype "input"))
      (node (ref "K5") (pin "4") (pinfunction "4_4") (pintype "input"))
      (node (ref "K5") (pin "5") (pinfunction "5_5") (pintype "input"))
      (node (ref "R75") (pin "1") (pinfunction "1_1") (pintype "unspecified"))
      (node (ref "R78") (pin "1") (pinfunction "1_1") (pintype "unspecified"))
    )
    (net (code "153") (name "Net-(C124-Pad2)") (class "Default")
      (node (ref "C124") (pin "2") (pinfunction "2_2") (pintype "input"))
      (node (ref "C125") (pin "2") (pinfunction "2_2") (pintype "input"))
      (node (ref "C130") (pin "2") (pinfunction "2_2") (pintype "input"))
      (node (ref "K5") (pin "2") (pinfunction "2_2") (pintype "input"))
      (node (ref "K5") (pin "7") (pinfunction "7_7") (pintype "input"))
      (node (ref "R76") (pin "1") (pinfunction "1_1") (pintype "unspecified"))
      (node (ref "R79") (pin "1") (pinfunction "1_1") (pintype "unspecified"))
    )
    (net (code "154") (name "Net-(C127-Pad1)") (class "Default")
      (node (ref "C127") (pin "1") (pinfunction "1_1") (pintype "input"))
      (node (ref "C128") (pin "1") (pinfunction "1_1") (pintype "input"))
      (node (ref "C129") (pin "1") (pinfunction "1_1") (pintype "input"))
      (node (ref "C130") (pin "1") (pinfunction "1_1") (pintype "input"))
      (node (ref "R77") (pin "2") (pinfunction "2_2") (pintype "unspecified"))
      (node (ref "R78") (pin "2") (pinfunction "2_2") (pintype "unspecified"))
      (node (ref "R79") (pin "2") (pinfunction "2_2") (pintype "unspecified"))
      (node (ref "R80") (pin "1") (pinfunction "1_1") (pintype "unspecified"))
    )
    (net (code "155") (name "Net-(C127-Pad2)") (class "Default")
      (node (ref "C127") (pin "2") (pinfunction "2_2") (pintype "input"))
      (node (ref "C128") (pin "2") (pinfunction "2_2") (pintype "input"))
      (node (ref "K4") (pin "4") (pinfunction "4_4") (pintype "input"))
      (node (ref "K4") (pin "5") (pinfunction "5_5") (pintype "input"))
      (node (ref "R74") (pin "2") (pinfunction "2_2") (pintype "unspecified"))
      (node (ref "R77") (pin "1") (pinfunction "1_1") (pintype "unspecified"))
    )
    (net (code "156") (name "Net-(C149-Pad1)") (class "Default")
      (node (ref "C149") (pin "1") (pinfunction "1_1") (pintype "input"))
      (node (ref "C86") (pin "1") (pinfunction "1_1") (pintype "input"))
      (node (ref "R98") (pin "1") (pinfunction "1_1") (pintype "unspecified"))
      (node (ref "R99") (pin "2") (pinfunction "2_2") (pintype "unspecified"))
    )
    (net (code "157") (name "Net-(D4-Pad1)") (class "Default")
      (node (ref "D4") (pin "1") (pinfunction "1_1") (pintype "unspecified"))
      (node (ref "D5") (pin "1") (pinfunction "1_1") (pintype "unspecified"))
      (node (ref "S1") (pin "2") (pinfunction "2_2") (pintype "unspecified"))
    )
    (net (code "158") (name "Net-(D6-A)") (class "Default")
      (node (ref "C89") (pin "2") (pinfunction "2_2") (pintype "input"))
      (node (ref "D6") (pin "1") (pinfunction "A_1") (pintype "unspecified"))
      (node (ref "L5") (pin "2") (pinfunction "2_2") (pintype "unspecified"))
      (node (ref "U15") (pin "1") (pinfunction "SW_1") (pintype "unspecified"))
    )
    (net (code "159") (name "Net-(D7-A)") (class "Default")
      (node (ref "C92") (pin "1") (pinfunction "1_1") (pintype "input"))
      (node (ref "D7") (pin "1") (pinfunction "A_1") (pintype "unspecified"))
      (node (ref "D9") (pin "2") (pinfunction "A_2") (pintype "unspecified"))
    )
    (net (code "160") (name "Net-(D7-K)") (class "Default")
      (node (ref "C89") (pin "1") (pinfunction "1_1") (pintype "input"))
      (node (ref "D7") (pin "2") (pinfunction "K_2") (pintype "unspecified"))
      (node (ref "D8") (pin "1") (pinfunction "A_1") (pintype "unspecified"))
    )
    (net (code "161") (name "Net-(D10-A)") (class "Default")
      (node (ref "D10") (pin "1") (pinfunction "A_1") (pintype "unspecified"))
      (node (ref "L6") (pin "2") (pinfunction "2_2") (pintype "unspecified"))
      (node (ref "U16") (pin "1") (pinfunction "SW_1") (pintype "unspecified"))
    )
    (net (code "162") (name "Net-(D13-Pad2)") (class "Default")
      (node (ref "D13") (pin "2") (pinfunction "2_2") (pintype "unspecified"))
      (node (ref "D4") (pin "2") (pinfunction "2_2") (pintype "unspecified"))
      (node (ref "R46") (pin "2") (pinfunction "2_2") (pintype "unspecified"))
    )
    (net (code "163") (name "Net-(K1-Pad2)") (class "Default")
      (node (ref "K1") (pin "2") (pinfunction "2_2") (pintype "input"))
      (node (ref "K1") (pin "7") (pinfunction "7_7") (pintype "input"))
      (node (ref "R70") (pin "2") (pinfunction "2_2") (pintype "unspecified"))
    )
    (net (code "164") (name "Net-(K2-Pad3)") (class "Default")
      (node (ref "K2") (pin "3") (pinfunction "3_3") (pintype "input"))
      (node (ref "K2") (pin "6") (pinfunction "6_6") (pintype "input"))
      (node (ref "K3") (pin "2") (pinfunction "2_2") (pintype "input"))
      (node (ref "K3") (pin "7") (pinfunction "7_7") (pintype "input"))
    )
    (net (code "165") (name "Net-(K4-Pad2)") (class "Default")
      (node (ref "K4") (pin "2") (pinfunction "2_2") (pintype "input"))
      (node (ref "K4") (pin "7") (pinfunction "7_7") (pintype "input"))
      (node (ref "K5") (pin "3") (pinfunction "3_3") (pintype "input"))
      (node (ref "K5") (pin "6") (pinfunction "6_6") (pintype "input"))
    )
    (net (code "166") (name "Net-(K6-Pad2)") (class "Default")
      (node (ref "K6") (pin "2") (pinfunction "2_2") (pintype "input"))
      (node (ref "K6") (pin "7") (pinfunction "7_7") (pintype "input"))
      (node (ref "R72") (pin "2") (pinfunction "2_2") (pintype "unspecified"))
    )
    (net (code "167") (name "Net-(P2-CD{slash}DAT3)") (class "Default")
      (node (ref "P2") (pin "2") (pinfunction "CD/DAT3_2") (pintype "unspecified"))
      (node (ref "R37") (pin "1") (pinfunction "1_1") (pintype "unspecified"))
      (node (ref "U1") (pin "54") (pinfunction "PF4/SDC0_D3/UART0_TX_54") (pintype "unspecified"))
    )
    (net (code "168") (name "Net-(P2-CLK)") (class "Default")
      (node (ref "P2") (pin "5") (pinfunction "CLK_5") (pintype "unspecified"))
      (node (ref "R39") (pin "1") (pinfunction "1_1") (pintype "unspecified"))
      (node (ref "U1") (pin "56") (pinfunction "PF2/SDC0_CLK/UART0_RX_56") (pintype "unspecified"))
    )
    (net (code "169") (name "Net-(P2-CMD)") (class "Default")
      (node (ref "P2") (pin "3") (pinfunction "CMD_3") (pintype "unspecified"))
      (node (ref "R38") (pin "1") (pinfunction "1_1") (pintype "unspecified"))
      (node (ref "U1") (pin "55") (pinfunction "PF3/SDC0_CMD/DBG_DO_55") (pintype "unspecified"))
    )
    (net (code "170") (name "Net-(P2-DAT0)") (class "Default")
      (node (ref "P2") (pin "7") (pinfunction "DAT0_7") (pintype "unspecified"))
      (node (ref "R40") (pin "1") (pinfunction "1_1") (pintype "unspecified"))
      (node (ref "U1") (pin "57") (pinfunction "PF1/SDC0_D0/DBG_DI_57") (pintype "unspecified"))
    )
    (net (code "171") (name "Net-(P2-DAT1)") (class "Default")
      (node (ref "P2") (pin "8") (pinfunction "DAT1_8") (pintype "unspecified"))
      (node (ref "R41") (pin "1") (pinfunction "1_1") (pintype "unspecified"))
      (node (ref "U1") (pin "58") (pinfunction "PF0/SDC0_D1/DBG_MS/IR_RX_58") (pintype "unspecified"))
    )
    (net (code "172") (name "Net-(P2-DAT2)") (class "Default")
      (node (ref "P2") (pin "1") (pinfunction "DAT2_1") (pintype "unspecified"))
      (node (ref "R36") (pin "1") (pinfunction "1_1") (pintype "unspecified"))
      (node (ref "U1") (pin "53") (pinfunction "PF5/SDC0_D2/DBG_CK/PWM1_53") (pintype "unspecified"))
    )
    (net (code "173") (name "Net-(Q1-C)") (class "Default")
      (node (ref "K1") (pin "1") (pinfunction "1_1") (pintype "input"))
      (node (ref "Q1") (pin "3") (pinfunction "C_3") (pintype "input"))
    )
    (net (code "174") (name "Net-(Q2-C)") (class "Default")
      (node (ref "K2") (pin "1") (pinfunction "1_1") (pintype "input"))
      (node (ref "Q2") (pin "3") (pinfunction "C_3") (pintype "input"))
    )
    (net (code "175") (name "Net-(Q3-C)") (class "Default")
      (node (ref "K3") (pin "1") (pinfunction "1_1") (pintype "input"))
      (node (ref "Q3") (pin "3") (pinfunction "C_3") (pintype "input"))
    )
    (net (code "176") (name "Net-(Q4-C)") (class "Default")
      (node (ref "K4") (pin "1") (pinfunction "1_1") (pintype "input"))
      (node (ref "Q4") (pin "3") (pinfunction "C_3") (pintype "input"))
    )
    (net (code "177") (name "Net-(Q5-C)") (class "Default")
      (node (ref "K5") (pin "1") (pinfunction "1_1") (pintype "input"))
      (node (ref "Q5") (pin "3") (pinfunction "C_3") (pintype "input"))
    )
    (net (code "178") (name "Net-(Q6-C)") (class "Default")
      (node (ref "K6") (pin "1") (pinfunction "1_1") (pintype "input"))
      (node (ref "Q6") (pin "3") (pinfunction "C_3") (pintype "input"))
    )
    (net (code "179") (name "Net-(Q7-B)") (class "Default")
      (node (ref "Q7") (pin "1") (pinfunction "B_1") (pintype "input"))
      (node (ref "R47") (pin "1") (pinfunction "1_1") (pintype "unspecified"))
    )
    (net (code "180") (name "Net-(Q7-C)") (class "Default")
      (node (ref "D13") (pin "1") (pinfunction "1_1") (pintype "unspecified"))
      (node (ref "Q7") (pin "3") (pinfunction "C_3") (pintype "input"))
    )
    (net (code "181") (name "Net-(Q8-G)") (class "Default")
      (node (ref "Q8") (pin "1") (pinfunction "G_1") (pintype "unspecified"))
      (node (ref "R46") (pin "1") (pinfunction "1_1") (pintype "unspecified"))
      (node (ref "R53") (pin "1") (pinfunction "1_1") (pintype "unspecified"))
    )
    (net (code "182") (name "Net-(R14-Pad2)") (class "Default")
      (node (ref "R14") (pin "2") (pinfunction "2_2") (pintype "unspecified"))
      (node (ref "U3") (pin "125") (pinfunction "IO_125") (pintype "input"))
    )
    (net (code "183") (name "Net-(R22-Pad2)") (class "Default")
      (node (ref "R22") (pin "2") (pinfunction "2_2") (pintype "unspecified"))
      (node (ref "U7") (pin "11") (pinfunction "AINB_11") (pintype "unspecified"))
      (node (ref "U7") (pin "2") (pinfunction "AINA_2") (pintype "unspecified"))
    )
    (net (code "184") (name "Net-(R23-Pad2)") (class "Default")
      (node (ref "R23") (pin "2") (pinfunction "2_2") (pintype "unspecified"))
      (node (ref "U8") (pin "11") (pinfunction "AINB_11") (pintype "unspecified"))
      (node (ref "U8") (pin "2") (pinfunction "AINA_2") (pintype "unspecified"))
    )
    (net (code "185") (name "Net-(R35-Pad2)") (class "Default")
      (node (ref "R35") (pin "2") (pinfunction "2_2") (pintype "unspecified"))
      (node (ref "R52") (pin "1") (pinfunction "1_1") (pintype "unspecified"))
      (node (ref "R54") (pin "1") (pinfunction "1_1") (pintype "unspecified"))
    )
    (net (code "186") (name "Net-(R54-Pad2)") (class "Default")
      (node (ref "R54") (pin "2") (pinfunction "2_2") (pintype "unspecified"))
      (node (ref "R55") (pin "1") (pinfunction "1_1") (pintype "unspecified"))
      (node (ref "R83") (pin "1") (pinfunction "1_1") (pintype "unspecified"))
    )
    (net (code "187") (name "Net-(R82-Pad1)") (class "Default")
      (node (ref "R82") (pin "1") (pinfunction "1_1") (pintype "unspecified"))
      (node (ref "RF3") (pin "1") (pinfunction "1_1") (pintype "unspecified"))
      (node (ref "RF3") (pin "2") (pinfunction "2_2") (pintype "unspecified"))
      (node (ref "RF3") (pin "3") (pinfunction "3_3") (pintype "unspecified"))
      (node (ref "RF3") (pin "4") (pinfunction "4_4") (pintype "unspecified"))
    )
    (net (code "188") (name "Net-(R83-Pad2)") (class "Default")
      (node (ref "R83") (pin "2") (pinfunction "2_2") (pintype "unspecified"))
      (node (ref "R84") (pin "1") (pinfunction "1_1") (pintype "unspecified"))
      (node (ref "R85") (pin "1") (pinfunction "1_1") (pintype "unspecified"))
    )
    (net (code "189") (name "Net-(R85-Pad2)") (class "Default")
      (node (ref "R85") (pin "2") (pinfunction "2_2") (pintype "unspecified"))
      (node (ref "R86") (pin "1") (pinfunction "1_1") (pintype "unspecified"))
      (node (ref "R87") (pin "1") (pinfunction "1_1") (pintype "unspecified"))
    )
    (net (code "190") (name "Net-(R87-Pad2)") (class "Default")
      (node (ref "R87") (pin "2") (pinfunction "2_2") (pintype "unspecified"))
      (node (ref "R88") (pin "1") (pinfunction "1_1") (pintype "unspecified"))
      (node (ref "R89") (pin "1") (pinfunction "1_1") (pintype "unspecified"))
    )
    (net (code "191") (name "Net-(R89-Pad2)") (class "Default")
      (node (ref "R89") (pin "2") (pinfunction "2_2") (pintype "unspecified"))
      (node (ref "R90") (pin "1") (pinfunction "1_1") (pintype "unspecified"))
      (node (ref "R91") (pin "1") (pinfunction "1_1") (pintype "unspecified"))
    )
    (net (code "192") (name "Net-(R91-Pad2)") (class "Default")
      (node (ref "R91") (pin "2") (pinfunction "2_2") (pintype "unspecified"))
      (node (ref "R92") (pin "1") (pinfunction "1_1") (pintype "unspecified"))
      (node (ref "R93") (pin "1") (pinfunction "1_1") (pintype "unspecified"))
    )
    (net (code "193") (name "Net-(R96-Pad1)") (class "Default")
      (node (ref "R96") (pin "1") (pinfunction "1_1") (pintype "unspecified"))
      (node (ref "RF3") (pin "5") (pinfunction "5_5") (pintype "unspecified"))
    )
    (net (code "194") (name "Net-(R99-Pad1)") (class "Default")
      (node (ref "R99") (pin "1") (pinfunction "1_1") (pintype "unspecified"))
      (node (ref "RF2") (pin "1") (pinfunction "1_1") (pintype "unspecified"))
      (node (ref "RF2") (pin "2") (pinfunction "2_2") (pintype "unspecified"))
      (node (ref "RF2") (pin "3") (pinfunction "3_3") (pintype "unspecified"))
      (node (ref "RF2") (pin "4") (pinfunction "4_4") (pintype "unspecified"))
    )
    (net (code "195") (name "Net-(R100-Pad1)") (class "Default")
      (node (ref "R100") (pin "1") (pinfunction "1_1") (pintype "unspecified"))
      (node (ref "RF1") (pin "1") (pinfunction "1_1") (pintype "unspecified"))
      (node (ref "RF1") (pin "2") (pinfunction "2_2") (pintype "unspecified"))
      (node (ref "RF1") (pin "3") (pinfunction "3_3") (pintype "unspecified"))
      (node (ref "RF1") (pin "4") (pinfunction "4_4") (pintype "unspecified"))
    )
    (net (code "196") (name "Net-(SW1-A)") (class "Default")
      (node (ref "R102") (pin "1") (pinfunction "1_1") (pintype "unspecified"))
      (node (ref "R103") (pin "2") (pinfunction "2_2") (pintype "unspecified"))
      (node (ref "SW1") (pin "1") (pinfunction "A_1") (pintype "input"))
    )
    (net (code "197") (name "Net-(SW1-B)") (class "Default")
      (node (ref "R105") (pin "1") (pinfunction "1_1") (pintype "unspecified"))
      (node (ref "R106") (pin "2") (pinfunction "2_2") (pintype "unspecified"))
      (node (ref "SW1") (pin "3") (pinfunction "B_3") (pintype "input"))
    )
    (net (code "198") (name "Net-(SW2-A)") (class "Default")
      (node (ref "R112") (pin "2") (pinfunction "2_2") (pintype "unspecified"))
      (node (ref "R113") (pin "1") (pinfunction "1_1") (pintype "unspecified"))
      (node (ref "SW2") (pin "1") (pinfunction "A_1") (pintype "input"))
    )
    (net (code "199") (name "Net-(SW2-B)") (class "Default")
      (node (ref "R109") (pin "2") (pinfunction "2_2") (pintype "unspecified"))
      (node (ref "R110") (pin "1") (pinfunction "1_1") (pintype "unspecified"))
      (node (ref "SW2") (pin "3") (pinfunction "B_3") (pintype "input"))
    )
    (net (code "200") (name "Net-(SW3-A)") (class "Default")
      (node (ref "R114") (pin "1") (pinfunction "1_1") (pintype "unspecified"))
      (node (ref "R115") (pin "2") (pinfunction "2_2") (pintype "unspecified"))
      (node (ref "SW3") (pin "1") (pinfunction "A_1") (pintype "input"))
    )
    (net (code "201") (name "Net-(SW3-B)") (class "Default")
      (node (ref "R117") (pin "1") (pinfunction "1_1") (pintype "unspecified"))
      (node (ref "R118") (pin "2") (pinfunction "2_2") (pintype "unspecified"))
      (node (ref "SW3") (pin "3") (pinfunction "B_3") (pintype "input"))
    )
    (net (code "202") (name "Net-(SW4-A)") (class "Default")
      (node (ref "R124") (pin "2") (pinfunction "2_2") (pintype "unspecified"))
      (node (ref "R125") (pin "1") (pinfunction "1_1") (pintype "unspecified"))
      (node (ref "SW4") (pin "1") (pinfunction "A_1") (pintype "input"))
    )
    (net (code "203") (name "Net-(SW4-B)") (class "Default")
      (node (ref "R121") (pin "2") (pinfunction "2_2") (pintype "unspecified"))
      (node (ref "R122") (pin "1") (pinfunction "1_1") (pintype "unspecified"))
      (node (ref "SW4") (pin "3") (pinfunction "B_3") (pintype "input"))
    )
    (net (code "204") (name "Net-(SW5-A)") (class "Default")
      (node (ref "R130") (pin "2") (pinfunction "2_2") (pintype "unspecified"))
      (node (ref "R131") (pin "1") (pinfunction "1_1") (pintype "unspecified"))
      (node (ref "SW5") (pin "1") (pinfunction "A_1") (pintype "input"))
    )
    (net (code "205") (name "Net-(SW5-B)") (class "Default")
      (node (ref "R127") (pin "2") (pinfunction "2_2") (pintype "unspecified"))
      (node (ref "R128") (pin "1") (pinfunction "1_1") (pintype "unspecified"))
      (node (ref "SW5") (pin "3") (pinfunction "B_3") (pintype "input"))
    )
    (net (code "206") (name "Net-(SW6-A)") (class "Default")
      (node (ref "R132") (pin "1") (pinfunction "1_1") (pintype "unspecified"))
      (node (ref "R133") (pin "2") (pinfunction "2_2") (pintype "unspecified"))
      (node (ref "SW6") (pin "1") (pinfunction "A_1") (pintype "input"))
    )
    (net (code "207") (name "Net-(SW6-B)") (class "Default")
      (node (ref "R135") (pin "1") (pinfunction "1_1") (pintype "unspecified"))
      (node (ref "R136") (pin "2") (pinfunction "2_2") (pintype "unspecified"))
      (node (ref "SW6") (pin "3") (pinfunction "B_3") (pintype "input"))
    )
    (net (code "208") (name "Net-(SW7-A)") (class "Default")
      (node (ref "R138") (pin "1") (pinfunction "1_1") (pintype "unspecified"))
      (node (ref "R139") (pin "2") (pinfunction "2_2") (pintype "unspecified"))
      (node (ref "SW7") (pin "1") (pinfunction "A_1") (pintype "input"))
    )
    (net (code "209") (name "Net-(SW7-B)") (class "Default")
      (node (ref "R141") (pin "1") (pinfunction "1_1") (pintype "unspecified"))
      (node (ref "R142") (pin "2") (pinfunction "2_2") (pintype "unspecified"))
      (node (ref "SW7") (pin "3") (pinfunction "B_3") (pintype "input"))
    )
    (net (code "210") (name "Net-(SW8-A)") (class "Default")
      (node (ref "R148") (pin "2") (pinfunction "2_2") (pintype "unspecified"))
      (node (ref "R149") (pin "1") (pinfunction "1_1") (pintype "unspecified"))
      (node (ref "SW8") (pin "1") (pinfunction "A_1") (pintype "input"))
    )
    (net (code "211") (name "Net-(SW8-B)") (class "Default")
      (node (ref "R145") (pin "2") (pinfunction "2_2") (pintype "unspecified"))
      (node (ref "R146") (pin "1") (pinfunction "1_1") (pintype "unspecified"))
      (node (ref "SW8") (pin "3") (pinfunction "B_3") (pintype "input"))
    )
    (net (code "212") (name "Net-(U1-HOSCI)") (class "Default")
      (node (ref "C32") (pin "1") (pinfunction "1_1") (pintype "input"))
      (node (ref "U1") (pin "51") (pinfunction "HOSCI_51") (pintype "unspecified"))
      (node (ref "X1") (pin "2") (pinfunction "OSC2_2") (pintype "input"))
    )
    (net (code "213") (name "Net-(U1-HOSCO)") (class "Default")
      (node (ref "C31") (pin "1") (pinfunction "1_1") (pintype "input"))
      (node (ref "U1") (pin "52") (pinfunction "HOSCO_52") (pintype "unspecified"))
      (node (ref "X1") (pin "1") (pinfunction "OSC1_1") (pintype "input"))
    )
    (net (code "214") (name "Net-(U1-RESET)") (class "Default")
      (node (ref "J4") (pin "1") (pinfunction "1_1") (pintype "input"))
      (node (ref "R30") (pin "1") (pinfunction "1_1") (pintype "unspecified"))
      (node (ref "U1") (pin "70") (pinfunction "RESET_70") (pintype "unspecified"))
    )
    (net (code "215") (name "Net-(U1-SVREF)") (class "Default")
      (node (ref "C46") (pin "1") (pinfunction "1_1") (pintype "input"))
      (node (ref "R28") (pin "1") (pinfunction "1_1") (pintype "unspecified"))
      (node (ref "R29") (pin "2") (pinfunction "2_2") (pintype "unspecified"))
      (node (ref "U1") (pin "33") (pinfunction "SVREF_33") (pintype "unspecified"))
    )
    (net (code "216") (name "Net-(U1-VRA1)") (class "Default")
      (node (ref "C55") (pin "1") (pinfunction "1_1") (pintype "input"))
      (node (ref "R31") (pin "2") (pinfunction "2_2") (pintype "unspecified"))
      (node (ref "U1") (pin "81") (pinfunction "VRA1_81") (pintype "unspecified"))
    )
    (net (code "217") (name "Net-(U1-VRA2)") (class "Default")
      (node (ref "C56") (pin "1") (pinfunction "1_1") (pintype "input"))
      (node (ref "R32") (pin "2") (pinfunction "2_2") (pintype "unspecified"))
      (node (ref "U1") (pin "83") (pinfunction "VRA2_83") (pintype "unspecified"))
    )
    (net (code "218") (name "Net-(U2-VCC)") (class "Default")
      (node (ref "C136") (pin "1") (pinfunction "1_1") (pintype "input"))
      (node (ref "C57") (pin "1") (pinfunction "1_1") (pintype "input"))
      (node (ref "D3") (pin "1") (pinfunction "1_1") (pintype "unspecified"))
      (node (ref "J1") (pin "4") (pinfunction "4_4") (pintype "input"))
      (node (ref "R33") (pin "2") (pinfunction "2_2") (pintype "unspecified"))
      (node (ref "U2") (pin "3") (pinfunction "/WP_3") (pintype "unspecified"))
      (node (ref "U2") (pin "7") (pinfunction "/HOLD_7") (pintype "unspecified"))
      (node (ref "U2") (pin "8") (pinfunction "VCC_8") (pintype "unspecified"))
    )
    (net (code "219") (name "Net-(U3-(DQ1T),(DATA2),DIFFIO_T10n,IO)") (class "Default")
      (node (ref "R19") (pin "2") (pinfunction "2_2") (pintype "unspecified"))
      (node (ref "U3") (pin "132") (pinfunction "(DQ1T),(DATA2),DIFFIO_T10n,IO_132") (pintype "input"))
    )
    (net (code "220") (name "Net-(U3-(DQ1T),(DATA3),DIFFIO_T10p,IO)") (class "Default")
      (node (ref "R20") (pin "2") (pinfunction "2_2") (pintype "unspecified"))
      (node (ref "U3") (pin "133") (pinfunction "(DQ1T),(DATA3),DIFFIO_T10p,IO_133") (pintype "input"))
    )
    (net (code "221") (name "Net-(U3-CLK1,DIFFCLK_0n)") (class "Default")
      (node (ref "R4") (pin "1") (pinfunction "1_1") (pintype "unspecified"))
      (node (ref "U3") (pin "23") (pinfunction "CLK1,DIFFCLK_0n_23") (pintype "input"))
    )
    (net (code "222") (name "Net-(U3-CLK2,DIFFCLK_1p)") (class "Default")
      (node (ref "R21") (pin "1") (pinfunction "1_1") (pintype "unspecified"))
      (node (ref "U3") (pin "24") (pinfunction "CLK2,DIFFCLK_1p_24") (pintype "input"))
    )
    (net (code "223") (name "Net-(U3-CLK3,DIFFCLK_1n)") (class "Default")
      (node (ref "C13") (pin "1") (pinfunction "1_1") (pintype "input"))
      (node (ref "R5") (pin "1") (pinfunction "1_1") (pintype "unspecified"))
      (node (ref "U3") (pin "25") (pinfunction "CLK3,DIFFCLK_1n_25") (pintype "input"))
    )
    (net (code "224") (name "Net-(U3-CONF_DONE)") (class "Default")
      (node (ref "R12") (pin "2") (pinfunction "2_2") (pintype "unspecified"))
      (node (ref "U3") (pin "92") (pinfunction "CONF_DONE_92") (pintype "input"))
    )
    (net (code "225") (name "Net-(U3-DIFFIO_T11n,IO)") (class "Default")
      (node (ref "R17") (pin "2") (pinfunction "2_2") (pintype "unspecified"))
      (node (ref "U3") (pin "128") (pinfunction "DIFFIO_T11n,IO_128") (pintype "input"))
    )
    (net (code "226") (name "Net-(U3-DIFFIO_T11p,IO)") (class "Default")
      (node (ref "R18") (pin "2") (pinfunction "2_2") (pintype "unspecified"))
      (node (ref "U3") (pin "129") (pinfunction "DIFFIO_T11p,IO_129") (pintype "input"))
    )
    (net (code "227") (name "Net-(U3-DIFFIO_T12n,IO)") (class "Default")
      (node (ref "R15") (pin "2") (pinfunction "2_2") (pintype "unspecified"))
      (node (ref "U3") (pin "126") (pinfunction "DIFFIO_T12n,IO_126") (pintype "input"))
    )
    (net (code "228") (name "Net-(U3-DIFFIO_T12p,IO)") (class "Default")
      (node (ref "R16") (pin "2") (pinfunction "2_2") (pintype "unspecified"))
      (node (ref "U3") (pin "127") (pinfunction "DIFFIO_T12p,IO_127") (pintype "input"))
    )
    (net (code "229") (name "Net-(U3-DIFFIO_T13p,IO)") (class "Default")
      (node (ref "R13") (pin "2") (pinfunction "2_2") (pintype "unspecified"))
      (node (ref "U3") (pin "124") (pinfunction "DIFFIO_T13p,IO_124") (pintype "input"))
    )
    (net (code "230") (name "Net-(U3-GNDA1)") (class "Default")
      (node (ref "C2") (pin "2") (pinfunction "2_2") (pintype "input"))
      (node (ref "C5") (pin "2") (pinfunction "2_2") (pintype "input"))
      (node (ref "L2") (pin "2") (pinfunction "2_2") (pintype "unspecified"))
      (node (ref "U3") (pin "36") (pinfunction "GNDA1_36") (pintype "input"))
    )
    (net (code "231") (name "Net-(U3-GNDA2)") (class "Default")
      (node (ref "C3") (pin "2") (pinfunction "2_2") (pintype "input"))
      (node (ref "C6") (pin "1") (pinfunction "1_1") (pintype "input"))
      (node (ref "L3") (pin "2") (pinfunction "2_2") (pintype "unspecified"))
      (node (ref "U3") (pin "108") (pinfunction "GNDA2_108") (pintype "input"))
    )
    (net (code "232") (name "Net-(U3-TCK)") (class "Default")
      (node (ref "R7") (pin "1") (pinfunction "1_1") (pintype "unspecified"))
      (node (ref "U3") (pin "16") (pinfunction "TCK_16") (pintype "input"))
    )
    (net (code "233") (name "Net-(U3-TDI)") (class "Default")
      (node (ref "R9") (pin "2") (pinfunction "2_2") (pintype "unspecified"))
      (node (ref "U3") (pin "15") (pinfunction "TDI_15") (pintype "input"))
    )
    (net (code "234") (name "Net-(U3-TMS)") (class "Default")
      (node (ref "R10") (pin "2") (pinfunction "2_2") (pintype "unspecified"))
      (node (ref "U3") (pin "18") (pinfunction "TMS_18") (pintype "input"))
    )
    (net (code "235") (name "Net-(U3-VCCD_PLL1)") (class "Default")
      (node (ref "C2") (pin "1") (pinfunction "1_1") (pintype "input"))
      (node (ref "L1") (pin "2") (pinfunction "2_2") (pintype "unspecified"))
      (node (ref "U3") (pin "37") (pinfunction "VCCD_PLL1_37") (pintype "input"))
    )
    (net (code "236") (name "Net-(U3-VCCD_PLL2)") (class "Default")
      (node (ref "C3") (pin "1") (pinfunction "1_1") (pintype "input"))
      (node (ref "L4") (pin "2") (pinfunction "2_2") (pintype "unspecified"))
      (node (ref "U3") (pin "109") (pinfunction "VCCD_PLL2_109") (pintype "input"))
    )
    (net (code "237") (name "Net-(U3-nCE)") (class "Default")
      (node (ref "R6") (pin "1") (pinfunction "1_1") (pintype "unspecified"))
      (node (ref "U3") (pin "21") (pinfunction "nCE_21") (pintype "input"))
    )
    (net (code "238") (name "Net-(U3-nCONFIG)") (class "Default")
      (node (ref "R11") (pin "2") (pinfunction "2_2") (pintype "unspecified"))
      (node (ref "U3") (pin "14") (pinfunction "nCONFIG_14") (pintype "input"))
    )
    (net (code "239") (name "Net-(U3-nSTATUS)") (class "Default")
      (node (ref "R8") (pin "2") (pinfunction "2_2") (pintype "unspecified"))
      (node (ref "U3") (pin "9") (pinfunction "nSTATUS_9") (pintype "input"))
    )
    (net (code "240") (name "Net-(U4-DO)") (class "Default")
      (node (ref "R1") (pin "2") (pinfunction "2_2") (pintype "unspecified"))
      (node (ref "U4") (pin "2") (pinfunction "DO_2") (pintype "unspecified"))
    )
    (net (code "241") (name "Net-(U4-VCC)") (class "Default")
      (node (ref "C51") (pin "1") (pinfunction "1_1") (pintype "input"))
      (node (ref "C52") (pin "1") (pinfunction "1_1") (pintype "input"))
      (node (ref "D1") (pin "1") (pinfunction "1_1") (pintype "unspecified"))
      (node (ref "J2") (pin "4") (pinfunction "4_4") (pintype "input"))
      (node (ref "U4") (pin "3") (pinfunction "/WP_3") (pintype "unspecified"))
      (node (ref "U4") (pin "7") (pinfunction "/HOLD_7") (pintype "unspecified"))
      (node (ref "U4") (pin "8") (pinfunction "VCC_8") (pintype "unspecified"))
    )
    (net (code "242") (name "Net-(U5-VCC)") (class "Default")
      (node (ref "C41") (pin "1") (pinfunction "1_1") (pintype "input"))
      (node (ref "C45") (pin "1") (pinfunction "1_1") (pintype "input"))
      (node (ref "D2") (pin "1") (pinfunction "1_1") (pintype "unspecified"))
      (node (ref "J3") (pin "2") (pinfunction "2_2") (pintype "input"))
      (node (ref "R2") (pin "2") (pinfunction "2_2") (pintype "unspecified"))
      (node (ref "R3") (pin "2") (pinfunction "2_2") (pintype "unspecified"))
      (node (ref "U5") (pin "8") (pinfunction "VCC_8") (pintype "unspecified"))
    )
    (net (code "243") (name "Net-(U7-REFINA)") (class "Default")
      (node (ref "C23") (pin "1") (pinfunction "1_1") (pintype "input"))
      (node (ref "U7") (pin "5") (pinfunction "REFINA_5") (pintype "unspecified"))
      (node (ref "U7") (pin "6") (pinfunction "REFOUT_6") (pintype "output"))
      (node (ref "U7") (pin "7") (pinfunction "REFINB_7") (pintype "unspecified"))
    )
    (net (code "244") (name "Net-(U8-REFINA)") (class "Default")
      (node (ref "C24") (pin "1") (pinfunction "1_1") (pintype "input"))
      (node (ref "U8") (pin "5") (pinfunction "REFINA_5") (pintype "unspecified"))
      (node (ref "U8") (pin "6") (pinfunction "REFOUT_6") (pintype "output"))
      (node (ref "U8") (pin "7") (pinfunction "REFINB_7") (pintype "unspecified"))
    )
    (net (code "245") (name "Net-(U13-CLK0)") (class "Default")
      (node (ref "R4") (pin "2") (pinfunction "2_2") (pintype "unspecified"))
      (node (ref "U13") (pin "10") (pinfunction "CLK0_10") (pintype "unspecified"))
    )
    (net (code "246") (name "Net-(U13-CLK1)") (class "Default")
      (node (ref "R21") (pin "2") (pinfunction "2_2") (pintype "unspecified"))
      (node (ref "U13") (pin "9") (pinfunction "CLK1_9") (pintype "unspecified"))
    )
    (net (code "247") (name "Net-(U13-XA)") (class "Default")
      (node (ref "U13") (pin "2") (pinfunction "XA_2") (pintype "unspecified"))
      (node (ref "X2") (pin "2") (pinfunction "OSC2_2") (pintype "input"))
    )
    (net (code "248") (name "Net-(U13-XB)") (class "Default")
      (node (ref "U13") (pin "3") (pinfunction "XB_3") (pintype "unspecified"))
      (node (ref "X2") (pin "1") (pinfunction "OSC1_1") (pintype "input"))
    )
    (net (code "249") (name "Net-(U14-+IN)") (class "Default")
      (node (ref "C81") (pin "1") (pinfunction "1_1") (pintype "input"))
      (node (ref "R34") (pin "1") (pinfunction "1_1") (pintype "unspecified"))
      (node (ref "R35") (pin "1") (pinfunction "1_1") (pintype "unspecified"))
      (node (ref "R94") (pin "1") (pinfunction "1_1") (pintype "unspecified"))
      (node (ref "U14") (pin "3") (pinfunction "+IN_3") (pintype "unspecified"))
    )
    (net (code "250") (name "Net-(U14--IN)") (class "Default")
      (node (ref "D14") (pin "2") (pinfunction "2_2") (pintype "unspecified"))
      (node (ref "D15") (pin "1") (pinfunction "1_1") (pintype "unspecified"))
      (node (ref "R95") (pin "2") (pinfunction "2_2") (pintype "unspecified"))
      (node (ref "R96") (pin "2") (pinfunction "2_2") (pintype "unspecified"))
      (node (ref "U14") (pin "4") (pinfunction "-IN_4") (pintype "unspecified"))
    )
    (net (code "251") (name "Net-(U14-OUT)") (class "Default")
      (node (ref "R95") (pin "1") (pinfunction "1_1") (pintype "unspecified"))
      (node (ref "U14") (pin "1") (pinfunction "OUT_1") (pintype "output"))
    )
    (net (code "252") (name "Net-(U15-FB)") (class "Default")
      (node (ref "R56") (pin "1") (pinfunction "1_1") (pintype "unspecified"))
      (node (ref "R57") (pin "2") (pinfunction "2_2") (pintype "unspecified"))
      (node (ref "U15") (pin "3") (pinfunction "FB_3") (pintype "unspecified"))
    )
    (net (code "253") (name "Net-(U17-+IN)") (class "Default")
      (node (ref "K3") (pin "3") (pinfunction "3_3") (pintype "input"))
      (node (ref "K3") (pin "6") (pinfunction "6_6") (pintype "input"))
      (node (ref "U17") (pin "3") (pinfunction "+IN_3") (pintype "unspecified"))
    )
    (net (code "254") (name "Net-(U17--IN)") (class "Default")
      (node (ref "C114") (pin "2") (pinfunction "2_2") (pintype "input"))
      (node (ref "K1") (pin "3") (pinfunction "3_3") (pintype "input"))
      (node (ref "K1") (pin "6") (pinfunction "6_6") (pintype "input"))
      (node (ref "R69") (pin "1") (pinfunction "1_1") (pintype "unspecified"))
      (node (ref "U17") (pin "4") (pinfunction "-IN_4") (pintype "unspecified"))
    )
    (net (code "255") (name "Net-(U18-S)") (class "Default")
      (node (ref "C99") (pin "2") (pinfunction "2_2") (pintype "input"))
      (node (ref "R62") (pin "2") (pinfunction "2_2") (pintype "unspecified"))
      (node (ref "U18") (pin "4") (pinfunction "S_4") (pintype "unspecified"))
    )
    (net (code "256") (name "Net-(U18-S1)") (class "Default")
      (node (ref "C99") (pin "1") (pinfunction "1_1") (pintype "input"))
      (node (ref "RF1") (pin "5") (pinfunction "5_5") (pintype "unspecified"))
      (node (ref "U18") (pin "3") (pinfunction "S1_3") (pintype "unspecified"))
    )
    (net (code "257") (name "Net-(U19-S)") (class "Default")
      (node (ref "C133") (pin "2") (pinfunction "2_2") (pintype "input"))
      (node (ref "R80") (pin "2") (pinfunction "2_2") (pintype "unspecified"))
      (node (ref "U19") (pin "4") (pinfunction "S_4") (pintype "unspecified"))
    )
    (net (code "258") (name "Net-(U19-S1)") (class "Default")
      (node (ref "C133") (pin "1") (pinfunction "1_1") (pintype "input"))
      (node (ref "RF2") (pin "5") (pinfunction "5_5") (pintype "unspecified"))
      (node (ref "U19") (pin "3") (pinfunction "S1_3") (pintype "unspecified"))
    )
    (net (code "259") (name "Net-(U20-+IN)") (class "Default")
      (node (ref "K4") (pin "3") (pinfunction "3_3") (pintype "input"))
      (node (ref "K4") (pin "6") (pinfunction "6_6") (pintype "input"))
      (node (ref "U20") (pin "3") (pinfunction "+IN_3") (pintype "unspecified"))
    )
    (net (code "260") (name "Net-(U20--IN)") (class "Default")
      (node (ref "C118") (pin "2") (pinfunction "2_2") (pintype "input"))
      (node (ref "K6") (pin "3") (pinfunction "3_3") (pintype "input"))
      (node (ref "K6") (pin "6") (pinfunction "6_6") (pintype "input"))
      (node (ref "R73") (pin "1") (pinfunction "1_1") (pintype "unspecified"))
      (node (ref "U20") (pin "4") (pinfunction "-IN_4") (pintype "unspecified"))
    )
    (net (code "261") (name "Net-(U22-NRST)") (class "Default")
      (node (ref "R101") (pin "1") (pinfunction "1_1") (pintype "unspecified"))
      (node (ref "U22") (pin "7") (pinfunction "NRST_7") (pintype "unspecified"))
    )
    (net (code "262") (name "POWER_HOLD") (class "Default")
      (node (ref "R47") (pin "2") (pinfunction "2_2") (pintype "unspecified"))
      (node (ref "R48") (pin "2") (pinfunction "2_2") (pintype "unspecified"))
      (node (ref "U22") (pin "33") (pinfunction "PA12_33") (pintype "unspecified"))
    )
    (net (code "263") (name "POWER_ON{slash}OFF") (class "Default")
      (node (ref "D5") (pin "2") (pinfunction "2_2") (pintype "unspecified"))
      (node (ref "R51") (pin "2") (pinfunction "2_2") (pintype "unspecified"))
      (node (ref "U22") (pin "32") (pinfunction "PA11_32") (pintype "unspecified"))
    )
    (net (code "264") (name "SELECT_A") (class "Default")
      (node (ref "C152") (pin "1") (pinfunction "1_1") (pintype "input"))
      (node (ref "R103") (pin "1") (pinfunction "1_1") (pintype "unspecified"))
      (node (ref "R104") (pin "2") (pinfunction "2_2") (pintype "unspecified"))
      (node (ref "U22") (pin "26") (pinfunction "PB13_26") (pintype "unspecified"))
    )
    (net (code "265") (name "SELECT_B") (class "Default")
      (node (ref "C153") (pin "1") (pinfunction "1_1") (pintype "input"))
      (node (ref "R106") (pin "1") (pinfunction "1_1") (pintype "unspecified"))
      (node (ref "R107") (pin "2") (pinfunction "2_2") (pintype "unspecified"))
      (node (ref "U22") (pin "25") (pinfunction "PB12_25") (pintype "unspecified"))
    )
    (net (code "266") (name "SWCLK") (class "Default")
      (node (ref "J6") (pin "4") (pinfunction "4_4") (pintype "input"))
      (node (ref "U22") (pin "37") (pinfunction "PA14_37") (pintype "unspecified"))
    )
    (net (code "267") (name "SWDIO") (class "Default")
      (node (ref "J6") (pin "3") (pinfunction "3_3") (pintype "input"))
      (node (ref "U22") (pin "34") (pinfunction "PA13_34") (pintype "unspecified"))
    )
    (net (code "268") (name "TRG_LVL_A") (class "Default")
      (node (ref "C161") (pin "1") (pinfunction "1_1") (pintype "input"))
      (node (ref "R129") (pin "2") (pinfunction "2_2") (pintype "unspecified"))
      (node (ref "R130") (pin "1") (pinfunction "1_1") (pintype "unspecified"))
      (node (ref "U22") (pin "3") (pinfunction "PC14-OSC32IN_3") (pintype "unspecified"))
    )
    (net (code "269") (name "TRG_LVL_B") (class "Default")
      (node (ref "C160") (pin "1") (pinfunction "1_1") (pintype "input"))
      (node (ref "R126") (pin "2") (pinfunction "2_2") (pintype "unspecified"))
      (node (ref "R127") (pin "1") (pinfunction "1_1") (pintype "unspecified"))
      (node (ref "U22") (pin "2") (pinfunction "PC13_2") (pintype "unspecified"))
    )
    (net (code "270") (name "TRG_POS_A") (class "Default")
      (node (ref "C159") (pin "1") (pinfunction "1_1") (pintype "input"))
      (node (ref "R123") (pin "2") (pinfunction "2_2") (pintype "unspecified"))
      (node (ref "R124") (pin "1") (pinfunction "1_1") (pintype "unspecified"))
      (node (ref "U22") (pin "46") (pinfunction "PB9_46") (pintype "unspecified"))
    )
    (net (code "271") (name "TRG_POS_B") (class "Default")
      (node (ref "C158") (pin "1") (pinfunction "1_1") (pintype "input"))
      (node (ref "R120") (pin "2") (pinfunction "2_2") (pintype "unspecified"))
      (node (ref "R121") (pin "1") (pinfunction "1_1") (pintype "unspecified"))
      (node (ref "U22") (pin "45") (pinfunction "PB8_45") (pintype "unspecified"))
    )
    (net (code "272") (name "TRG_RNG\\_A") (class "Default")
      (node (ref "C162") (pin "1") (pinfunction "1_1") (pintype "input"))
      (node (ref "R133") (pin "1") (pinfunction "1_1") (pintype "unspecified"))
      (node (ref "R134") (pin "2") (pinfunction "2_2") (pintype "unspecified"))
      (node (ref "U22") (pin "4") (pinfunction "PC15-OSC32OUT_4") (pintype "unspecified"))
    )
    (net (code "273") (name "TRG_RNG_B") (class "Default")
      (node (ref "C163") (pin "1") (pinfunction "1_1") (pintype "input"))
      (node (ref "R136") (pin "1") (pinfunction "1_1") (pintype "unspecified"))
      (node (ref "R137") (pin "2") (pinfunction "2_2") (pintype "unspecified"))
      (node (ref "U22") (pin "5") (pinfunction "PF0-OSCIN_5") (pintype "unspecified"))
    )
    (net (code "274") (name "USB-DM") (class "Default")
      (node (ref "U1") (pin "68") (pinfunction "USB-DM_68") (pintype "unspecified"))
      (node (ref "USB1") (pin "2") (pinfunction "D-_2") (pintype "input"))
    )
    (net (code "275") (name "USB-DP") (class "Default")
      (node (ref "U1") (pin "69") (pinfunction "USB-DP_69") (pintype "unspecified"))
      (node (ref "USB1") (pin "3") (pinfunction "D+_3") (pintype "input"))
    )
    (net (code "276") (name "VRF1") (class "Default")
      (node (ref "C100") (pin "2") (pinfunction "2_2") (pintype "input"))
      (node (ref "C101") (pin "2") (pinfunction "2_2") (pintype "input"))
      (node (ref "C106") (pin "2") (pinfunction "2_2") (pintype "input"))
      (node (ref "C107") (pin "1") (pinfunction "1_1") (pintype "input"))
      (node (ref "C108") (pin "1") (pinfunction "1_1") (pintype "input"))
      (node (ref "C109") (pin "1") (pinfunction "1_1") (pintype "input"))
      (node (ref "C110") (pin "1") (pinfunction "1_1") (pintype "input"))
      (node (ref "C111") (pin "2") (pinfunction "2_2") (pintype "input"))
      (node (ref "C112") (pin "2") (pinfunction "2_2") (pintype "input"))
      (node (ref "C115") (pin "2") (pinfunction "2_2") (pintype "input"))
      (node (ref "C117") (pin "2") (pinfunction "2_2") (pintype "input"))
      (node (ref "C121") (pin "2") (pinfunction "2_2") (pintype "input"))
      (node (ref "C122") (pin "1") (pinfunction "1_1") (pintype "input"))
      (node (ref "C123") (pin "1") (pinfunction "1_1") (pintype "input"))
      (node (ref "C124") (pin "1") (pinfunction "1_1") (pintype "input"))
      (node (ref "C125") (pin "1") (pinfunction "1_1") (pintype "input"))
      (node (ref "C126") (pin "2") (pinfunction "2_2") (pintype "input"))
      (node (ref "C134") (pin "2") (pinfunction "2_2") (pintype "input"))
      (node (ref "C135") (pin "1") (pinfunction "1_1") (pintype "input"))
      (node (ref "C149") (pin "2") (pinfunction "2_2") (pintype "input"))
      (node (ref "C150") (pin "1") (pinfunction "1_1") (pintype "input"))
      (node (ref "C83") (pin "1") (pinfunction "1_1") (pintype "input"))
      (node (ref "C84") (pin "2") (pinfunction "2_2") (pintype "input"))
      (node (ref "D11") (pin "1") (pinfunction "1_1") (pintype "unspecified"))
      (node (ref "D12") (pin "2") (pinfunction "2_2") (pintype "unspecified"))
      (node (ref "R66") (pin "2") (pinfunction "2_2") (pintype "unspecified"))
      (node (ref "R67") (pin "2") (pinfunction "2_2") (pintype "unspecified"))
      (node (ref "R68") (pin "1") (pinfunction "1_1") (pintype "unspecified"))
      (node (ref "R70") (pin "1") (pinfunction "1_1") (pintype "unspecified"))
      (node (ref "R71") (pin "2") (pinfunction "2_2") (pintype "unspecified"))
      (node (ref "R72") (pin "1") (pinfunction "1_1") (pintype "unspecified"))
      (node (ref "R74") (pin "1") (pinfunction "1_1") (pintype "unspecified"))
      (node (ref "R75") (pin "2") (pinfunction "2_2") (pintype "unspecified"))
      (node (ref "R76") (pin "2") (pinfunction "2_2") (pintype "unspecified"))
      (node (ref "R81") (pin "2") (pinfunction "2_2") (pintype "unspecified"))
      (node (ref "R97") (pin "2") (pinfunction "2_2") (pintype "unspecified"))
      (node (ref "R98") (pin "2") (pinfunction "2_2") (pintype "unspecified"))
      (node (ref "U21") (pin "1") (pinfunction "CATHODE_1") (pintype "unspecified"))
      (node (ref "U21") (pin "2") (pinfunction "REF_2") (pintype "unspecified"))
    )
    (net (code "277") (name "unconnected-(J5-Pad6)") (class "Default")
      (node (ref "J5") (pin "6") (pinfunction "6_6") (pintype "unspecified"))
    )
    (net (code "278") (name "unconnected-(J5-Pad7)") (class "Default")
      (node (ref "J5") (pin "7") (pinfunction "7_7") (pintype "unspecified"))
    )
    (net (code "279") (name "unconnected-(J5-Pad8)") (class "Default")
      (node (ref "J5") (pin "8") (pinfunction "8_8") (pintype "unspecified"))
    )
    (net (code "280") (name "unconnected-(J6-Pad1)") (class "Default")
      (node (ref "J6") (pin "1") (pinfunction "1_1") (pintype "input"))
    )
    (net (code "281") (name "unconnected-(P3-Pad45)") (class "Default")
      (node (ref "P3") (pin "45") (pinfunction "45_45") (pintype "unspecified"))
    )
    (net (code "282") (name "unconnected-(U1-FMINL-Pad84)") (class "Default")
      (node (ref "U1") (pin "84") (pinfunction "FMINL_84") (pintype "unspecified"))
    )
    (net (code "283") (name "unconnected-(U1-FMINR-Pad85)") (class "Default")
      (node (ref "U1") (pin "85") (pinfunction "FMINR_85") (pintype "unspecified"))
    )
    (net (code "284") (name "unconnected-(U1-HPCOM-Pad3)") (class "Default")
      (node (ref "U1") (pin "3") (pinfunction "HPCOM_3") (pintype "unspecified"))
    )
    (net (code "285") (name "unconnected-(U1-HPCOMFB-Pad2)") (class "Default")
      (node (ref "U1") (pin "2") (pinfunction "HPCOMFB_2") (pintype "unspecified"))
    )
    (net (code "286") (name "unconnected-(U1-HPL-Pad1)") (class "Default")
      (node (ref "U1") (pin "1") (pinfunction "HPL_1") (pintype "unspecified"))
    )
    (net (code "287") (name "unconnected-(U1-HPR-Pad88)") (class "Default")
      (node (ref "U1") (pin "88") (pinfunction "HPR_88") (pintype "unspecified"))
    )
    (net (code "288") (name "unconnected-(U1-HPVCC-Pad4)") (class "Default")
      (node (ref "U1") (pin "4") (pinfunction "HPVCC_4") (pintype "unspecified"))
    )
    (net (code "289") (name "unconnected-(U1-LINEIN-Pad86)") (class "Default")
      (node (ref "U1") (pin "86") (pinfunction "LINEIN_86") (pintype "unspecified"))
    )
    (net (code "290") (name "unconnected-(U1-LRADC0-Pad79)") (class "Default")
      (node (ref "U1") (pin "79") (pinfunction "LRADC0_79") (pintype "unspecified"))
    )
    (net (code "291") (name "unconnected-(U1-MICIN-Pad87)") (class "Default")
      (node (ref "U1") (pin "87") (pinfunction "MICIN_87") (pintype "unspecified"))
    )
    (net (code "292") (name "unconnected-(U1-PD0{slash}LCD_D2{slash}TWI0_SDA-Pad6)") (class "Default")
      (node (ref "U1") (pin "6") (pinfunction "PD0/LCD_D2/TWI0_SDA_6") (pintype "unspecified"))
    )
    (net (code "293") (name "unconnected-(U1-PD12{slash}LCD_D18{slash}TWI0_SCK-Pad18)") (class "Default")
      (node (ref "U1") (pin "18") (pinfunction "PD12/LCD_D18/TWI0_SCK_18") (pintype "unspecified"))
    )
    (net (code "294") (name "unconnected-(U1-PE11{slash}CLK_OUT{slash}TWI0_SCK{slash}IR_RX-Pad38)") (class "Default")
      (node (ref "U1") (pin "38") (pinfunction "PE11/CLK_OUT/TWI0_SCK/IR_RX_38") (pintype "unspecified"))
    )
    (net (code "295") (name "unconnected-(U1-PE12{slash}DA_MCLK{slash}TWI0_SDA{slash}PWM0-Pad37)") (class "Default")
      (node (ref "U1") (pin "37") (pinfunction "PE12/DA_MCLK/TWI0_SDA/PWM0_37") (pintype "unspecified"))
    )
    (net (code "296") (name "unconnected-(U1-TVIN0-Pad78)") (class "Default")
      (node (ref "U1") (pin "78") (pinfunction "TVIN0_78") (pintype "unspecified"))
    )
    (net (code "297") (name "unconnected-(U1-TVIN1-Pad77)") (class "Default")
      (node (ref "U1") (pin "77") (pinfunction "TVIN1_77") (pintype "unspecified"))
    )
    (net (code "298") (name "unconnected-(U1-TVOUT-Pad72)") (class "Default")
      (node (ref "U1") (pin "72") (pinfunction "TVOUT_72") (pintype "unspecified"))
    )
    (net (code "299") (name "unconnected-(U1-TV_VCC-Pad73)") (class "Default")
      (node (ref "U1") (pin "73") (pinfunction "TV_VCC_73") (pintype "unspecified"))
    )
    (net (code "300") (name "unconnected-(U1-TV_VRN-Pad75)") (class "Default")
      (node (ref "U1") (pin "75") (pinfunction "TV_VRN_75") (pintype "unspecified"))
    )
    (net (code "301") (name "unconnected-(U1-TV_VRP-Pad76)") (class "Default")
      (node (ref "U1") (pin "76") (pinfunction "TV_VRP_76") (pintype "unspecified"))
    )
    (net (code "302") (name "unconnected-(U3-(DQ1B),DIFFIO_B10p,IO-Pad51)") (class "Default")
      (node (ref "U3") (pin "51") (pinfunction "(DQ1B),DIFFIO_B10p,IO_51") (pintype "input"))
    )
    (net (code "303") (name "unconnected-(U3-(DQ1B),DIFFIO_B15p,IO-Pad58)") (class "Default")
      (node (ref "U3") (pin "58") (pinfunction "(DQ1B),DIFFIO_B15p,IO_58") (pintype "input"))
    )
    (net (code "304") (name "unconnected-(U3-(DQ1B),DIFFIO_B16n,IO-Pad60)") (class "Default")
      (node (ref "U3") (pin "60") (pinfunction "(DQ1B),DIFFIO_B16n,IO_60") (pintype "input"))
    )
    (net (code "305") (name "unconnected-(U3-(DQ1B),DIFFIO_B16p,IO-Pad59)") (class "Default")
      (node (ref "U3") (pin "59") (pinfunction "(DQ1B),DIFFIO_B16p,IO_59") (pintype "input"))
    )
    (net (code "306") (name "unconnected-(U3-(DQS0L{slash}CQ1L,DPCLK0),DIFFIO_L4p,IO-Pad10)") (class "Default")
      (node (ref "U3") (pin "10") (pinfunction "(DQS0L/CQ1L,DPCLK0),DIFFIO_L4p,IO_10") (pintype "input"))
    )
    (net (code "307") (name "unconnected-(U3-(DQS0R{slash}CQ1R,DPCLK5),IO-Pad104)") (class "Default")
      (node (ref "U3") (pin "104") (pinfunction "(DQS0R/CQ1R,DPCLK5),IO_104") (pintype "input"))
    )
    (net (code "308") (name "unconnected-(U3-(DQS1L{slash}CQ1L#,DPCLK1),DIFFIO_L8p,IO-Pad30)") (class "Default")
      (node (ref "U3") (pin "30") (pinfunction "(DQS1L/CQ1L#,DPCLK1),DIFFIO_L8p,IO_30") (pintype "input"))
    )
    (net (code "309") (name "unconnected-(U3-DIFFIO_B11n,IO-Pad53)") (class "Default")
      (node (ref "U3") (pin "53") (pinfunction "DIFFIO_B11n,IO_53") (pintype "input"))
    )
    (net (code "310") (name "unconnected-(U3-DIFFIO_B11p,IO-Pad52)") (class "Default")
      (node (ref "U3") (pin "52") (pinfunction "DIFFIO_B11p,IO_52") (pintype "input"))
    )
    (net (code "311") (name "unconnected-(U3-DIFFIO_B12n,IO-Pad55)") (class "Default")
      (node (ref "U3") (pin "55") (pinfunction "DIFFIO_B12n,IO_55") (pintype "input"))
    )
    (net (code "312") (name "unconnected-(U3-DIFFIO_B12p,IO-Pad54)") (class "Default")
      (node (ref "U3") (pin "54") (pinfunction "DIFFIO_B12p,IO_54") (pintype "input"))
    )
    (net (code "313") (name "unconnected-(U3-DIFFIO_L4n,IO-Pad11)") (class "Default")
      (node (ref "U3") (pin "11") (pinfunction "DIFFIO_L4n,IO_11") (pintype "input"))
    )
    (net (code "314") (name "unconnected-(U3-DIFFIO_L6n,IO-Pad28)") (class "Default")
      (node (ref "U3") (pin "28") (pinfunction "DIFFIO_L6n,IO_28") (pintype "input"))
    )
    (net (code "315") (name "unconnected-(U3-DIFFIO_R1n,IO-Pad106)") (class "Default")
      (node (ref "U3") (pin "106") (pinfunction "DIFFIO_R1n,IO_106") (pintype "input"))
    )
    (net (code "316") (name "unconnected-(U3-RUP1,IO-Pad32)") (class "Default")
      (node (ref "U3") (pin "32") (pinfunction "RUP1,IO_32") (pintype "input"))
    )
    (net (code "317") (name "unconnected-(U3-TDO-Pad20)") (class "Default")
      (node (ref "U3") (pin "20") (pinfunction "TDO_20") (pintype "input"))
    )
    (net (code "318") (name "unconnected-(U3-VERFB6N0,IO-Pad105)") (class "Default")
      (node (ref "U3") (pin "105") (pinfunction "VERFB6N0,IO_105") (pintype "input"))
    )
    (net (code "319") (name "unconnected-(U3-VREFB2N0,IO-Pad31)") (class "Default")
      (node (ref "U3") (pin "31") (pinfunction "VREFB2N0,IO_31") (pintype "input"))
    )
    (net (code "320") (name "unconnected-(U5-A0-Pad1)") (class "Default")
      (node (ref "U5") (pin "1") (pinfunction "A0_1") (pintype "unspecified"))
    )
    (net (code "321") (name "unconnected-(U5-A1-Pad2)") (class "Default")
      (node (ref "U5") (pin "2") (pinfunction "A1_2") (pintype "unspecified"))
    )
    (net (code "322") (name "unconnected-(U5-A2-Pad3)") (class "Default")
      (node (ref "U5") (pin "3") (pinfunction "A2_3") (pintype "unspecified"))
    )
    (net (code "323") (name "unconnected-(U5-WP-Pad7)") (class "Default")
      (node (ref "U5") (pin "7") (pinfunction "WP_7") (pintype "unspecified"))
    )
    (net (code "324") (name "unconnected-(U7-NC-Pad25)") (class "Default")
      (node (ref "U7") (pin "25") (pinfunction "NC_25") (pintype "unspecified"))
    )
    (net (code "325") (name "unconnected-(U7-NC-Pad26)") (class "Default")
      (node (ref "U7") (pin "26") (pinfunction "NC_26") (pintype "unspecified"))
    )
    (net (code "326") (name "unconnected-(U7-NC-Pad35)") (class "Default")
      (node (ref "U7") (pin "35") (pinfunction "NC_35") (pintype "unspecified"))
    )
    (net (code "327") (name "unconnected-(U7-NC-Pad36)") (class "Default")
      (node (ref "U7") (pin "36") (pinfunction "NC_36") (pintype "unspecified"))
    )
    (net (code "328") (name "unconnected-(U8-NC-Pad25)") (class "Default")
      (node (ref "U8") (pin "25") (pinfunction "NC_25") (pintype "unspecified"))
    )
    (net (code "329") (name "unconnected-(U8-NC-Pad26)") (class "Default")
      (node (ref "U8") (pin "26") (pinfunction "NC_26") (pintype "unspecified"))
    )
    (net (code "330") (name "unconnected-(U8-NC-Pad35)") (class "Default")
      (node (ref "U8") (pin "35") (pinfunction "NC_35") (pintype "unspecified"))
    )
    (net (code "331") (name "unconnected-(U8-NC-Pad36)") (class "Default")
      (node (ref "U8") (pin "36") (pinfunction "NC_36") (pintype "unspecified"))
    )
    (net (code "332") (name "unconnected-(U11-N{slash}C-Pad4)") (class "Default")
      (node (ref "U11") (pin "4") (pinfunction "N/C_4") (pintype "unspecified"))
    )
    (net (code "333") (name "unconnected-(U13-CLK2-Pad6)") (class "Default")
      (node (ref "U13") (pin "6") (pinfunction "CLK2_6") (pintype "unspecified"))
    )
    (net (code "334") (name "unconnected-(U13-VDDO-Pad7)") (class "Default")
      (node (ref "U13") (pin "7") (pinfunction "VDDO_7") (pintype "unspecified"))
    )
    (net (code "335") (name "unconnected-(U22-PA8-Pad29)") (class "Default")
      (node (ref "U22") (pin "29") (pinfunction "PA8_29") (pintype "unspecified"))
    )
    (net (code "336") (name "unconnected-(U22-PB14-Pad27)") (class "Default")
      (node (ref "U22") (pin "27") (pinfunction "PB14_27") (pintype "unspecified"))
    )
    (net (code "337") (name "unconnected-(U22-PB15-Pad28)") (class "Default")
      (node (ref "U22") (pin "28") (pinfunction "PB15_28") (pintype "unspecified"))
    )
    (net (code "338") (name "unconnected-(U22-PF6-Pad35)") (class "Default")
      (node (ref "U22") (pin "35") (pinfunction "PF6_35") (pintype "unspecified"))
    )
    (net (code "339") (name "unconnected-(U22-PF7-Pad36)") (class "Default")
      (node (ref "U22") (pin "36") (pinfunction "PF7_36") (pintype "unspecified"))
    )
    (net (code "340") (name "unconnected-(USB1-Pad5)") (class "Default")
      (node (ref "USB1") (pin "5") (pinfunction "5_5") (pintype "unspecified"))
    )
    (net (code "341") (name "unconnected-(USB1-Pad6)") (class "Default")
      (node (ref "USB1") (pin "6") (pinfunction "6_6") (pintype "unspecified"))
    )
    (net (code "342") (name "unconnected-(USB1-VCC-Pad1)") (class "Default")
      (node (ref "USB1") (pin "1") (pinfunction "VCC_1") (pintype "input"))
    )
  )
)
